# SCH_New-Device-Whole-Board_2024-05-06.net
KiCad netlist of a schematic drawn in EasyEDA
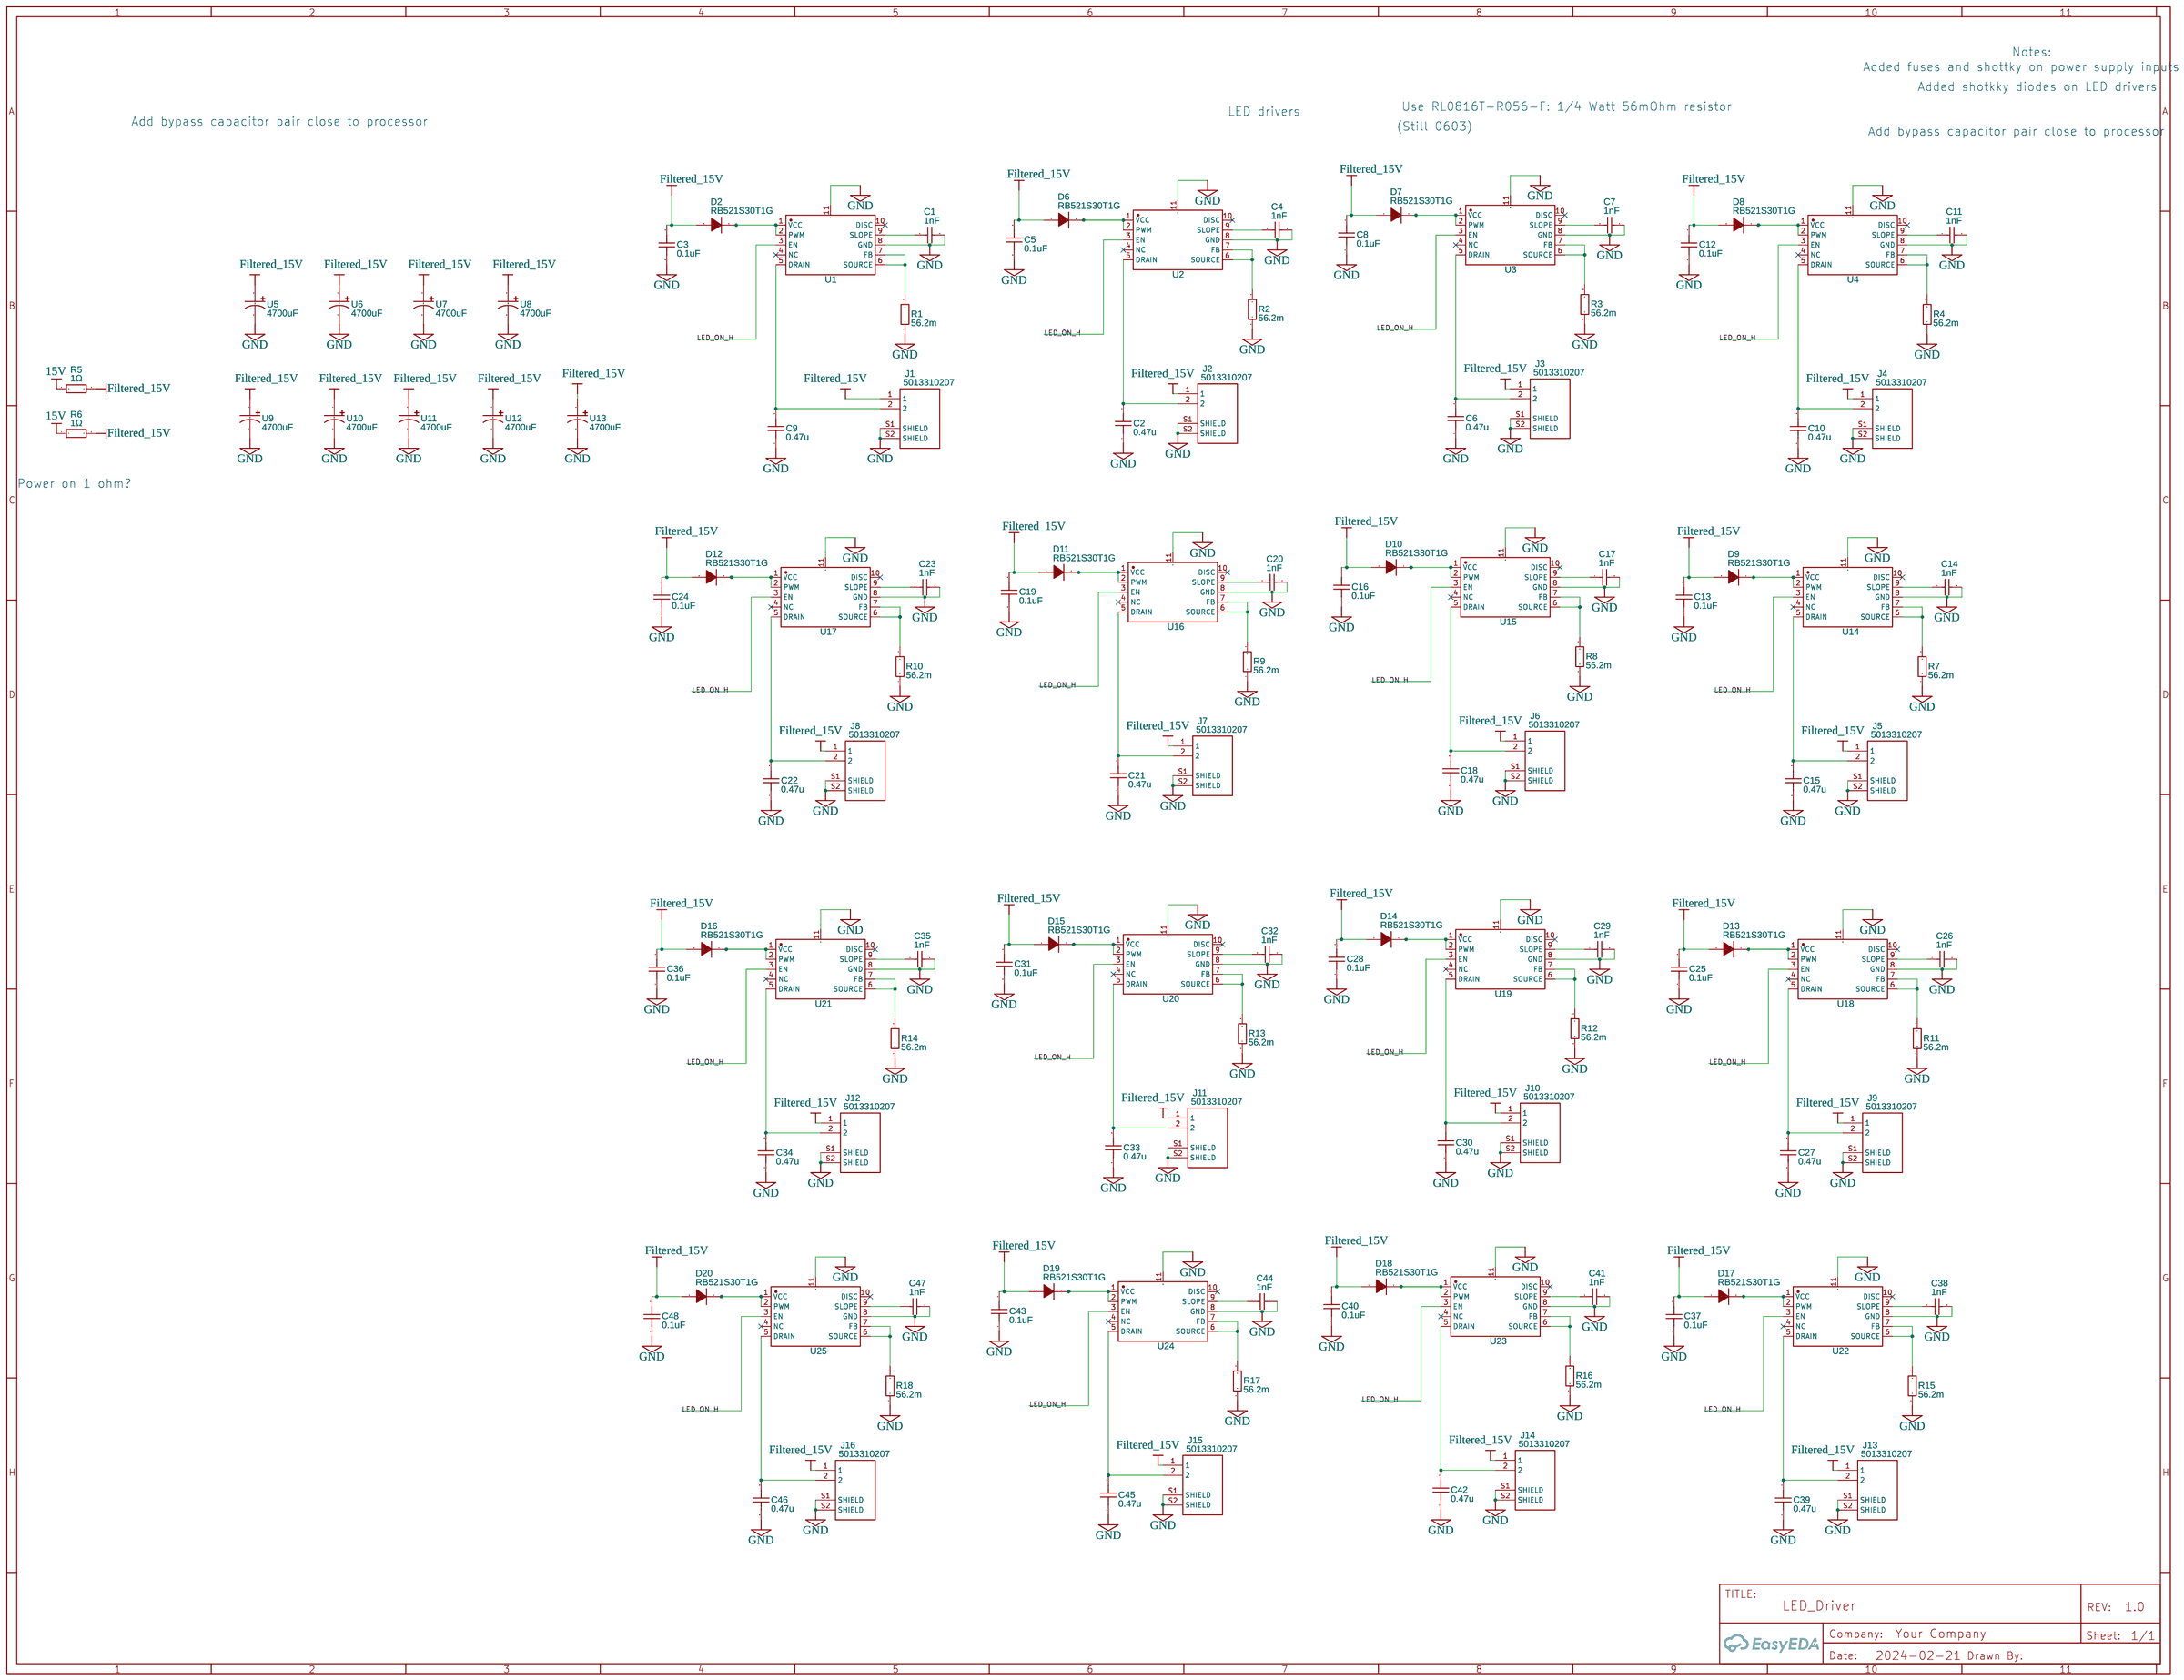
[diagram p0: LED_Driver copy copy]
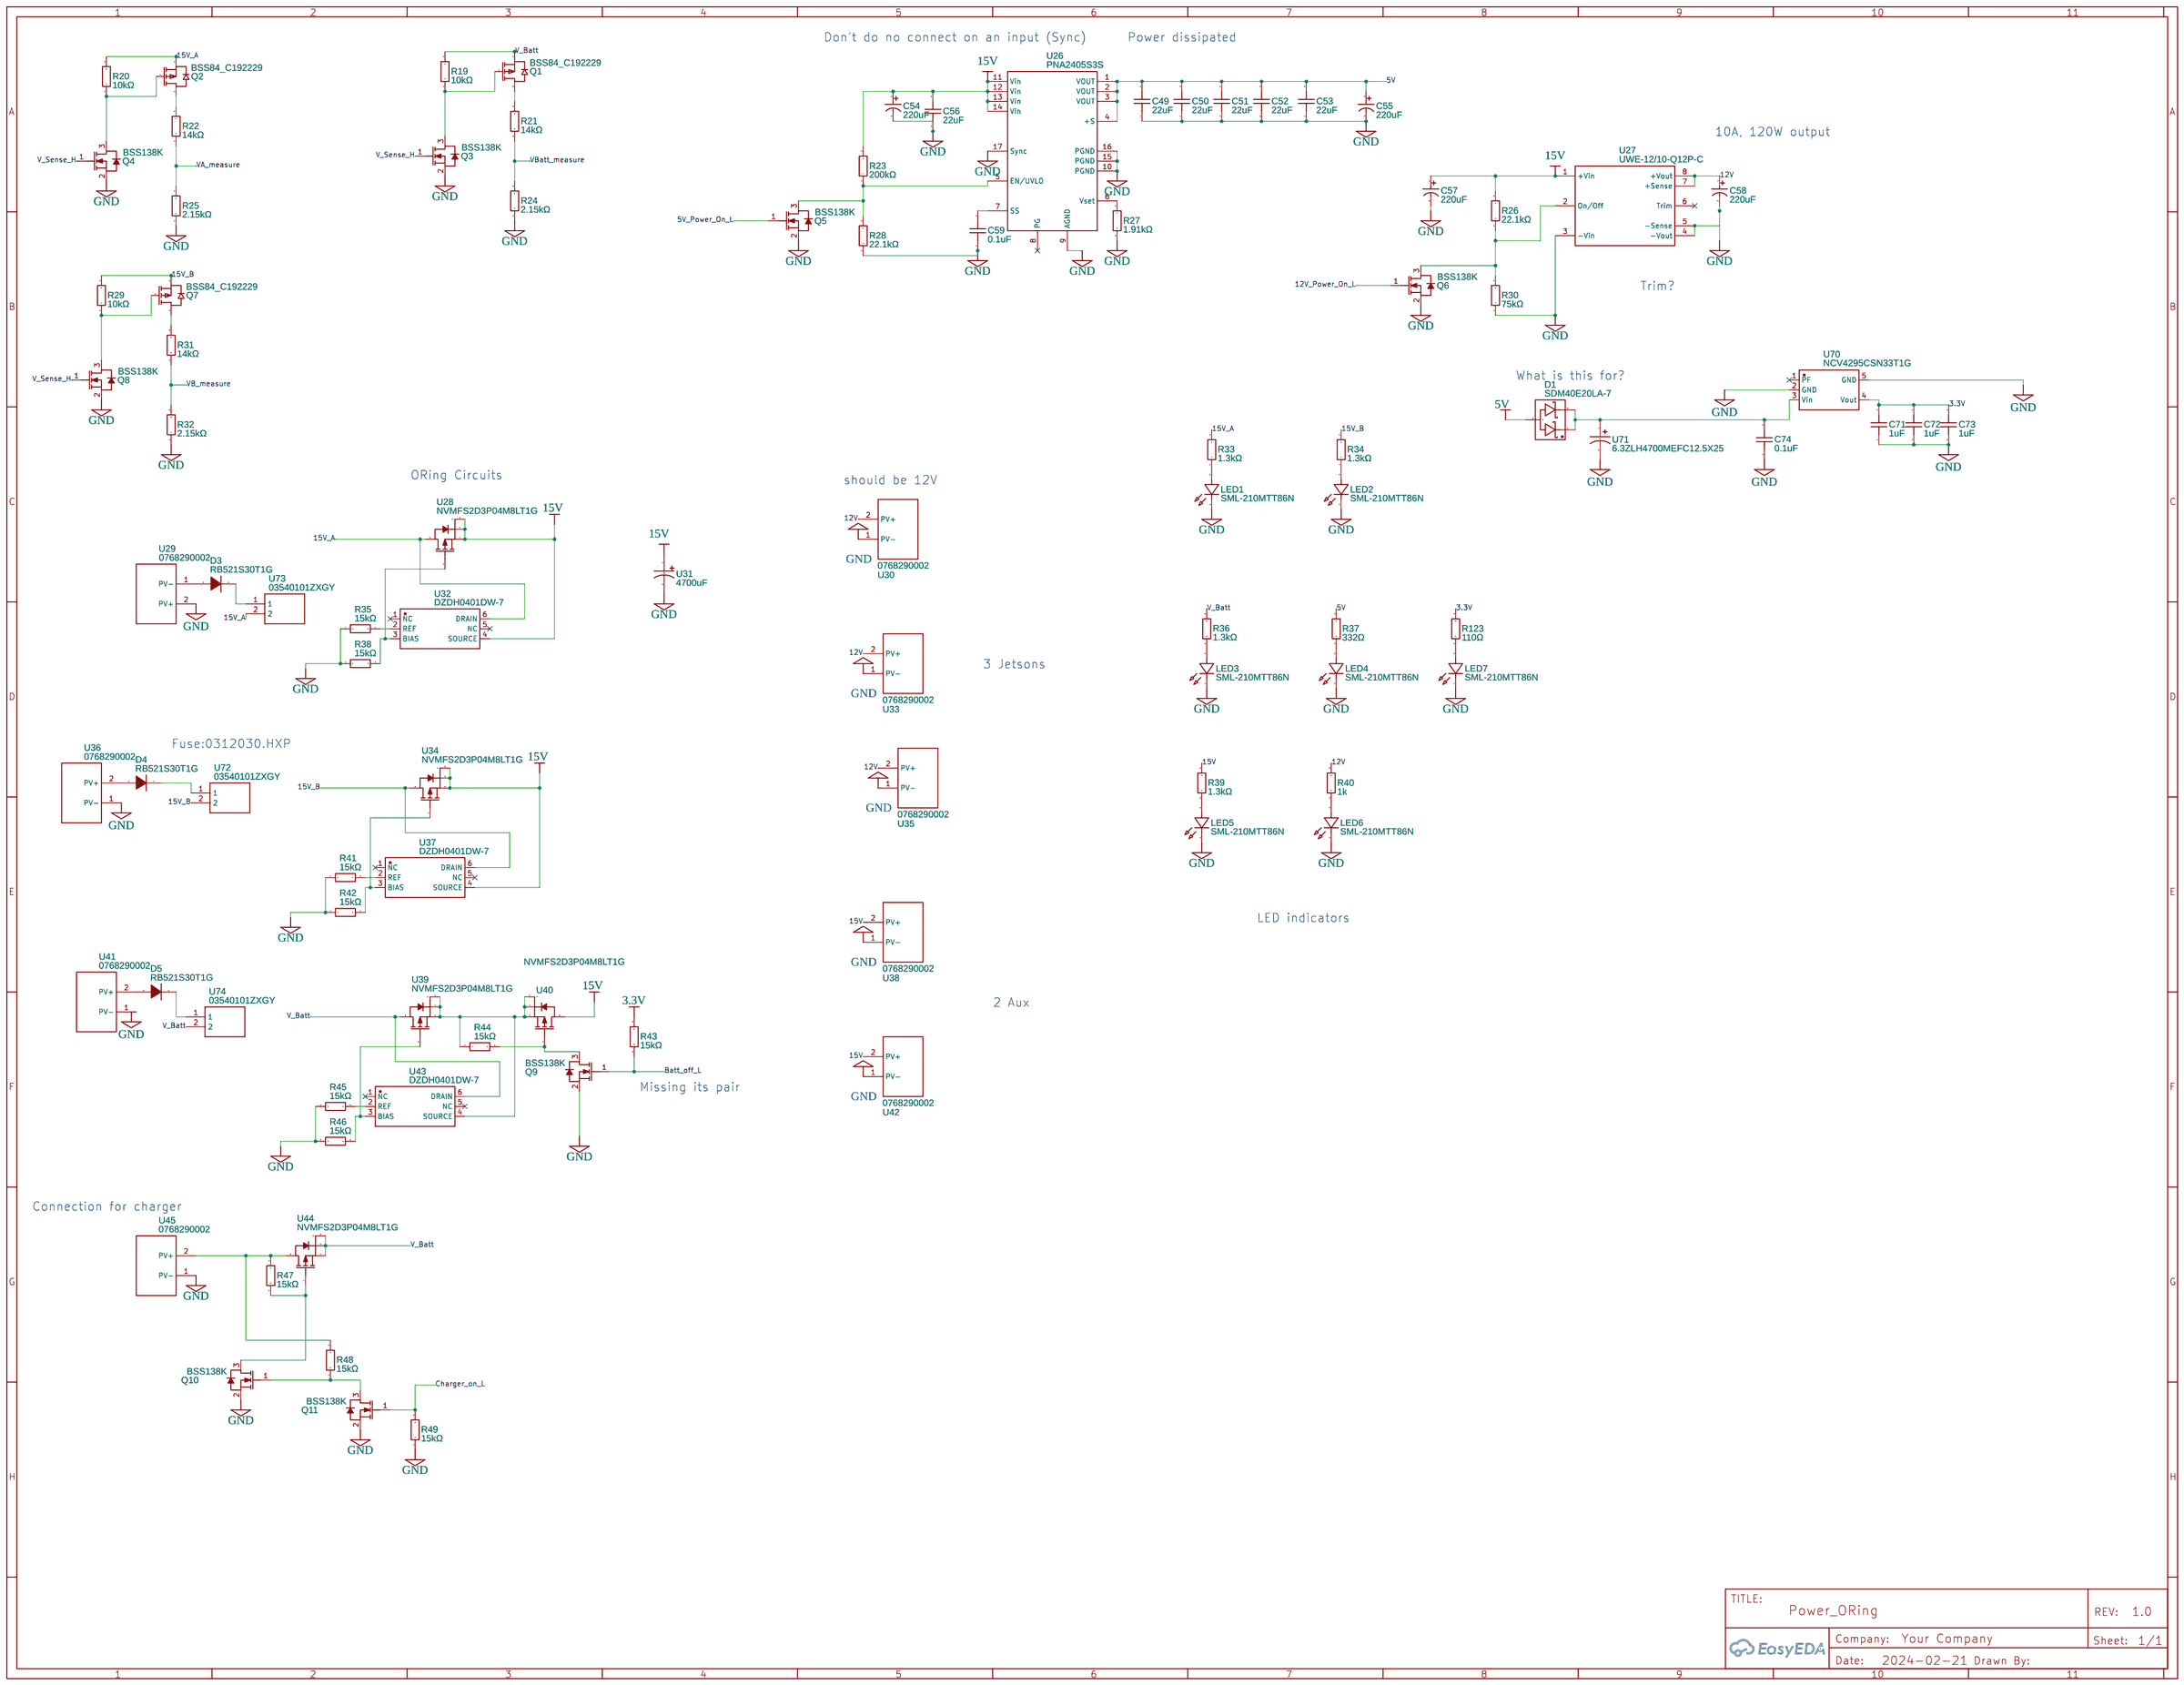
[diagram p1: Power_ORing copy copy]
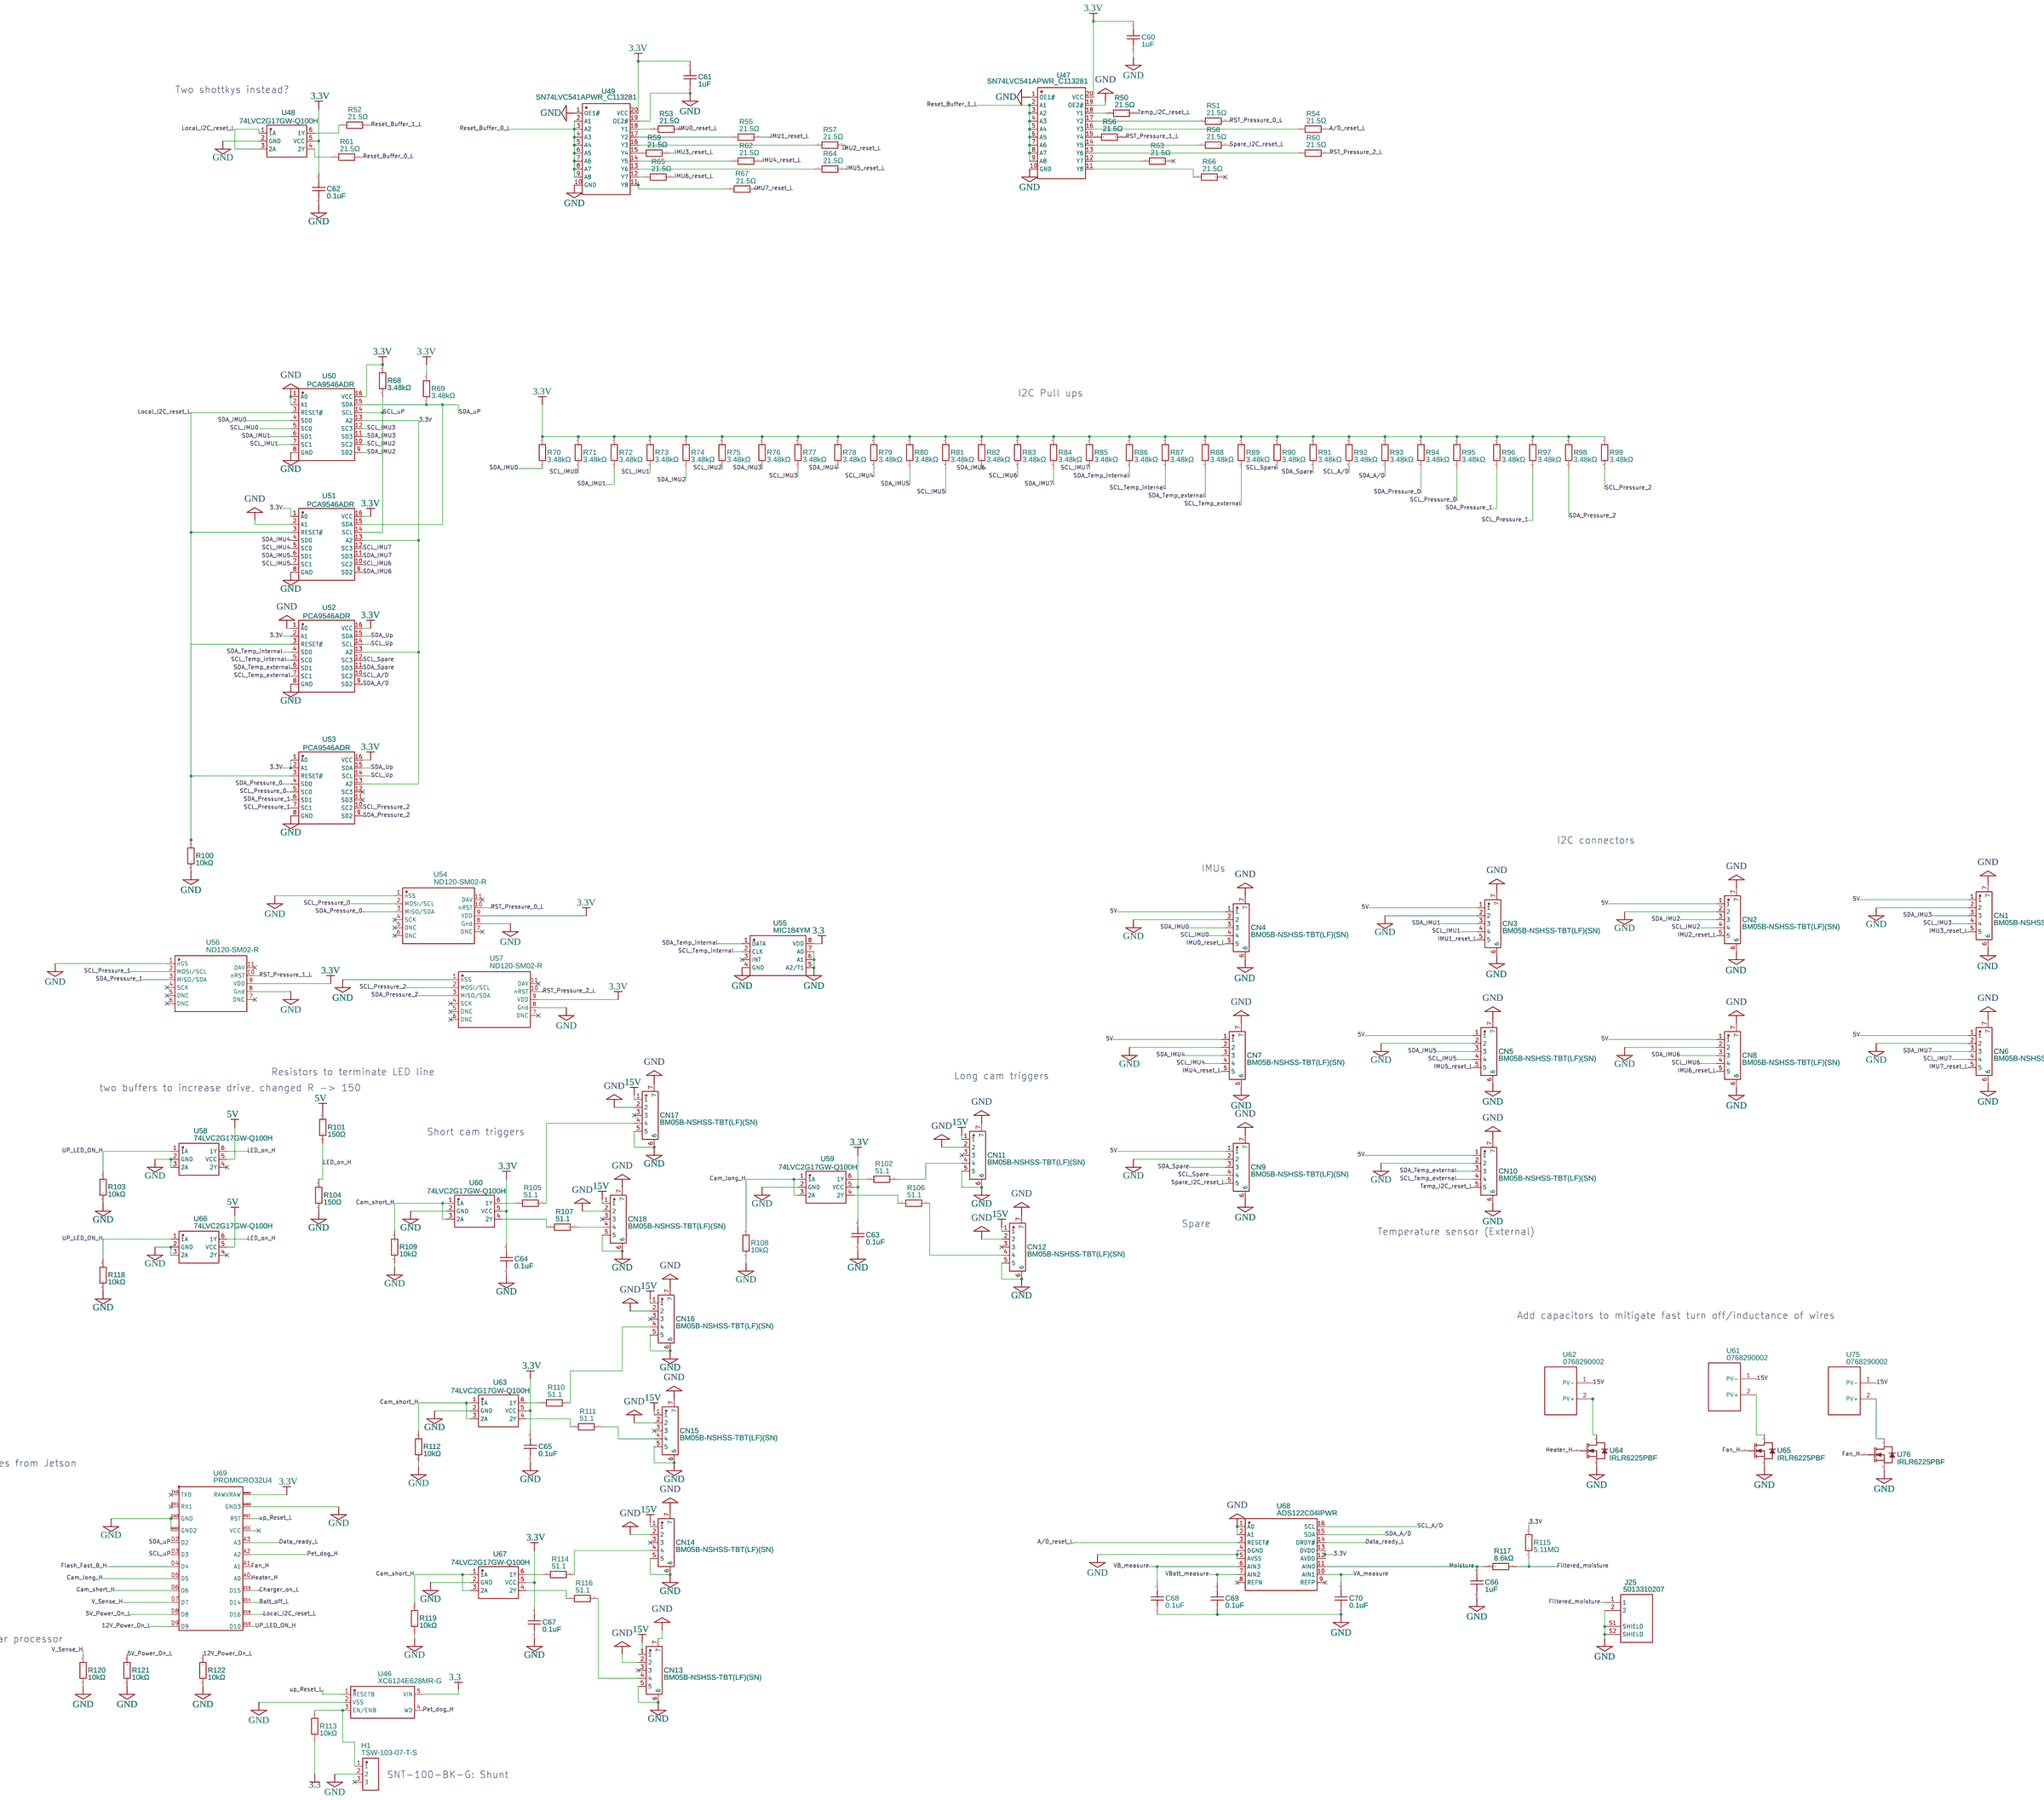
[diagram p2: Control copy copy]

(export (version "E")
  (design (tool "Eeschema 10.0.6"))
  (components
    (comp (ref "C1")
      (value "1nF")
      (fields
        (field (name "Manufacturer Part") "CC0603KRX7R9BB102")
        (field (name "Manufacturer") "YAGEO(国巨)")
      )
      (libsource (lib "") (part "CC0603KRX7R9BB102"))
    )
    (comp (ref "C2")
      (value "0.47u")
      (fields (field (name "Manufacturer Part") "0603CG0R1C500NT") (field (name "Manufacturer") "FH(风华)"))
      (libsource (lib "") (part "0603CG0R1C500NT"))
    )
    (comp (ref "C3")
      (value "0.1uF")
      (fields (field (name "Manufacturer Part") "0603CG0R1C500NT") (field (name "Manufacturer") "FH(风华)"))
      (libsource (lib "") (part "0603CG0R1C500NT"))
    )
    (comp (ref "C4")
      (value "1nF")
      (fields
        (field (name "Manufacturer Part") "CC0603KRX7R9BB102")
        (field (name "Manufacturer") "YAGEO(国巨)")
      )
      (libsource (lib "") (part "CC0603KRX7R9BB102"))
    )
    (comp (ref "C5")
      (value "0.1uF")
      (fields (field (name "Manufacturer Part") "0603CG0R1C500NT") (field (name "Manufacturer") "FH(风华)"))
      (libsource (lib "") (part "0603CG0R1C500NT"))
    )
    (comp (ref "C6")
      (value "0.47u")
      (fields (field (name "Manufacturer Part") "0603CG0R1C500NT") (field (name "Manufacturer") "FH(风华)"))
      (libsource (lib "") (part "0603CG0R1C500NT"))
    )
    (comp (ref "C7")
      (value "1nF")
      (fields
        (field (name "Manufacturer Part") "CC0603KRX7R9BB102")
        (field (name "Manufacturer") "YAGEO(国巨)")
      )
      (libsource (lib "") (part "CC0603KRX7R9BB102"))
    )
    (comp (ref "C8")
      (value "0.1uF")
      (fields (field (name "Manufacturer Part") "0603CG0R1C500NT") (field (name "Manufacturer") "FH(风华)"))
      (libsource (lib "") (part "0603CG0R1C500NT"))
    )
    (comp (ref "C9")
      (value "0.47u")
      (fields (field (name "Manufacturer Part") "0603CG0R1C500NT") (field (name "Manufacturer") "FH(风华)"))
      (libsource (lib "") (part "0603CG0R1C500NT"))
    )
    (comp (ref "C10")
      (value "0.47u")
      (fields (field (name "Manufacturer Part") "0603CG0R1C500NT") (field (name "Manufacturer") "FH(风华)"))
      (libsource (lib "") (part "0603CG0R1C500NT"))
    )
    (comp (ref "C11")
      (value "1nF")
      (fields
        (field (name "Manufacturer Part") "CC0603KRX7R9BB102")
        (field (name "Manufacturer") "YAGEO(国巨)")
      )
      (libsource (lib "") (part "CC0603KRX7R9BB102"))
    )
    (comp (ref "C12")
      (value "0.1uF")
      (fields (field (name "Manufacturer Part") "0603CG0R1C500NT") (field (name "Manufacturer") "FH(风华)"))
      (libsource (lib "") (part "0603CG0R1C500NT"))
    )
    (comp (ref "C13")
      (value "0.1uF")
      (fields (field (name "Manufacturer Part") "0603CG0R1C500NT") (field (name "Manufacturer") "FH(风华)"))
      (libsource (lib "") (part "0603CG0R1C500NT"))
    )
    (comp (ref "C14")
      (value "1nF")
      (fields
        (field (name "Manufacturer Part") "CC0603KRX7R9BB102")
        (field (name "Manufacturer") "YAGEO(国巨)")
      )
      (libsource (lib "") (part "CC0603KRX7R9BB102"))
    )
    (comp (ref "C15")
      (value "0.47u")
      (fields (field (name "Manufacturer Part") "0603CG0R1C500NT") (field (name "Manufacturer") "FH(风华)"))
      (libsource (lib "") (part "0603CG0R1C500NT"))
    )
    (comp (ref "C16")
      (value "0.1uF")
      (fields (field (name "Manufacturer Part") "0603CG0R1C500NT") (field (name "Manufacturer") "FH(风华)"))
      (libsource (lib "") (part "0603CG0R1C500NT"))
    )
    (comp (ref "C17")
      (value "1nF")
      (fields
        (field (name "Manufacturer Part") "CC0603KRX7R9BB102")
        (field (name "Manufacturer") "YAGEO(国巨)")
      )
      (libsource (lib "") (part "CC0603KRX7R9BB102"))
    )
    (comp (ref "C18")
      (value "0.47u")
      (fields (field (name "Manufacturer Part") "0603CG0R1C500NT") (field (name "Manufacturer") "FH(风华)"))
      (libsource (lib "") (part "0603CG0R1C500NT"))
    )
    (comp (ref "C19")
      (value "0.1uF")
      (fields (field (name "Manufacturer Part") "0603CG0R1C500NT") (field (name "Manufacturer") "FH(风华)"))
      (libsource (lib "") (part "0603CG0R1C500NT"))
    )
    (comp (ref "C20")
      (value "1nF")
      (fields
        (field (name "Manufacturer Part") "CC0603KRX7R9BB102")
        (field (name "Manufacturer") "YAGEO(国巨)")
      )
      (libsource (lib "") (part "CC0603KRX7R9BB102"))
    )
    (comp (ref "C21")
      (value "0.47u")
      (fields (field (name "Manufacturer Part") "0603CG0R1C500NT") (field (name "Manufacturer") "FH(风华)"))
      (libsource (lib "") (part "0603CG0R1C500NT"))
    )
    (comp (ref "C22")
      (value "0.47u")
      (fields (field (name "Manufacturer Part") "0603CG0R1C500NT") (field (name "Manufacturer") "FH(风华)"))
      (libsource (lib "") (part "0603CG0R1C500NT"))
    )
    (comp (ref "C23")
      (value "1nF")
      (fields
        (field (name "Manufacturer Part") "CC0603KRX7R9BB102")
        (field (name "Manufacturer") "YAGEO(国巨)")
      )
      (libsource (lib "") (part "CC0603KRX7R9BB102"))
    )
    (comp (ref "C24")
      (value "0.1uF")
      (fields (field (name "Manufacturer Part") "0603CG0R1C500NT") (field (name "Manufacturer") "FH(风华)"))
      (libsource (lib "") (part "0603CG0R1C500NT"))
    )
    (comp (ref "C25")
      (value "0.1uF")
      (fields (field (name "Manufacturer Part") "0603CG0R1C500NT") (field (name "Manufacturer") "FH(风华)"))
      (libsource (lib "") (part "0603CG0R1C500NT"))
    )
    (comp (ref "C26")
      (value "1nF")
      (fields
        (field (name "Manufacturer Part") "CC0603KRX7R9BB102")
        (field (name "Manufacturer") "YAGEO(国巨)")
      )
      (libsource (lib "") (part "CC0603KRX7R9BB102"))
    )
    (comp (ref "C27")
      (value "0.47u")
      (fields (field (name "Manufacturer Part") "0603CG0R1C500NT") (field (name "Manufacturer") "FH(风华)"))
      (libsource (lib "") (part "0603CG0R1C500NT"))
    )
    (comp (ref "C28")
      (value "0.1uF")
      (fields (field (name "Manufacturer Part") "0603CG0R1C500NT") (field (name "Manufacturer") "FH(风华)"))
      (libsource (lib "") (part "0603CG0R1C500NT"))
    )
    (comp (ref "C29")
      (value "1nF")
      (fields
        (field (name "Manufacturer Part") "CC0603KRX7R9BB102")
        (field (name "Manufacturer") "YAGEO(国巨)")
      )
      (libsource (lib "") (part "CC0603KRX7R9BB102"))
    )
    (comp (ref "C30")
      (value "0.47u")
      (fields (field (name "Manufacturer Part") "0603CG0R1C500NT") (field (name "Manufacturer") "FH(风华)"))
      (libsource (lib "") (part "0603CG0R1C500NT"))
    )
    (comp (ref "C31")
      (value "0.1uF")
      (fields (field (name "Manufacturer Part") "0603CG0R1C500NT") (field (name "Manufacturer") "FH(风华)"))
      (libsource (lib "") (part "0603CG0R1C500NT"))
    )
    (comp (ref "C32")
      (value "1nF")
      (fields
        (field (name "Manufacturer Part") "CC0603KRX7R9BB102")
        (field (name "Manufacturer") "YAGEO(国巨)")
      )
      (libsource (lib "") (part "CC0603KRX7R9BB102"))
    )
    (comp (ref "C33")
      (value "0.47u")
      (fields (field (name "Manufacturer Part") "0603CG0R1C500NT") (field (name "Manufacturer") "FH(风华)"))
      (libsource (lib "") (part "0603CG0R1C500NT"))
    )
    (comp (ref "C34")
      (value "0.47u")
      (fields (field (name "Manufacturer Part") "0603CG0R1C500NT") (field (name "Manufacturer") "FH(风华)"))
      (libsource (lib "") (part "0603CG0R1C500NT"))
    )
    (comp (ref "C35")
      (value "1nF")
      (fields
        (field (name "Manufacturer Part") "CC0603KRX7R9BB102")
        (field (name "Manufacturer") "YAGEO(国巨)")
      )
      (libsource (lib "") (part "CC0603KRX7R9BB102"))
    )
    (comp (ref "C36")
      (value "0.1uF")
      (fields (field (name "Manufacturer Part") "0603CG0R1C500NT") (field (name "Manufacturer") "FH(风华)"))
      (libsource (lib "") (part "0603CG0R1C500NT"))
    )
    (comp (ref "C37")
      (value "0.1uF")
      (fields (field (name "Manufacturer Part") "0603CG0R1C500NT") (field (name "Manufacturer") "FH(风华)"))
      (libsource (lib "") (part "0603CG0R1C500NT"))
    )
    (comp (ref "C38")
      (value "1nF")
      (fields
        (field (name "Manufacturer Part") "CC0603KRX7R9BB102")
        (field (name "Manufacturer") "YAGEO(国巨)")
      )
      (libsource (lib "") (part "CC0603KRX7R9BB102"))
    )
    (comp (ref "C39")
      (value "0.47u")
      (fields (field (name "Manufacturer Part") "0603CG0R1C500NT") (field (name "Manufacturer") "FH(风华)"))
      (libsource (lib "") (part "0603CG0R1C500NT"))
    )
    (comp (ref "C40")
      (value "0.1uF")
      (fields (field (name "Manufacturer Part") "0603CG0R1C500NT") (field (name "Manufacturer") "FH(风华)"))
      (libsource (lib "") (part "0603CG0R1C500NT"))
    )
    (comp (ref "C41")
      (value "1nF")
      (fields
        (field (name "Manufacturer Part") "CC0603KRX7R9BB102")
        (field (name "Manufacturer") "YAGEO(国巨)")
      )
      (libsource (lib "") (part "CC0603KRX7R9BB102"))
    )
    (comp (ref "C42")
      (value "0.47u")
      (fields (field (name "Manufacturer Part") "0603CG0R1C500NT") (field (name "Manufacturer") "FH(风华)"))
      (libsource (lib "") (part "0603CG0R1C500NT"))
    )
    (comp (ref "C43")
      (value "0.1uF")
      (fields (field (name "Manufacturer Part") "0603CG0R1C500NT") (field (name "Manufacturer") "FH(风华)"))
      (libsource (lib "") (part "0603CG0R1C500NT"))
    )
    (comp (ref "C44")
      (value "1nF")
      (fields
        (field (name "Manufacturer Part") "CC0603KRX7R9BB102")
        (field (name "Manufacturer") "YAGEO(国巨)")
      )
      (libsource (lib "") (part "CC0603KRX7R9BB102"))
    )
    (comp (ref "C45")
      (value "0.47u")
      (fields (field (name "Manufacturer Part") "0603CG0R1C500NT") (field (name "Manufacturer") "FH(风华)"))
      (libsource (lib "") (part "0603CG0R1C500NT"))
    )
    (comp (ref "C46")
      (value "0.47u")
      (fields (field (name "Manufacturer Part") "0603CG0R1C500NT") (field (name "Manufacturer") "FH(风华)"))
      (libsource (lib "") (part "0603CG0R1C500NT"))
    )
    (comp (ref "C47")
      (value "1nF")
      (fields
        (field (name "Manufacturer Part") "CC0603KRX7R9BB102")
        (field (name "Manufacturer") "YAGEO(国巨)")
      )
      (libsource (lib "") (part "CC0603KRX7R9BB102"))
    )
    (comp (ref "C48")
      (value "0.1uF")
      (fields (field (name "Manufacturer Part") "0603CG0R1C500NT") (field (name "Manufacturer") "FH(风华)"))
      (libsource (lib "") (part "0603CG0R1C500NT"))
    )
    (comp (ref "D2")
      (value "RB521S30T1G")
      (fields (field (name "Manufacturer") "onsemi(安森美)"))
      (libsource (lib "") (part "RB521S30T1G"))
    )
    (comp (ref "D6")
      (value "RB521S30T1G")
      (fields (field (name "Manufacturer") "onsemi(安森美)"))
      (libsource (lib "") (part "RB521S30T1G"))
    )
    (comp (ref "D7")
      (value "RB521S30T1G")
      (fields (field (name "Manufacturer") "onsemi(安森美)"))
      (libsource (lib "") (part "RB521S30T1G"))
    )
    (comp (ref "D8")
      (value "RB521S30T1G")
      (fields (field (name "Manufacturer") "onsemi(安森美)"))
      (libsource (lib "") (part "RB521S30T1G"))
    )
    (comp (ref "D9")
      (value "RB521S30T1G")
      (fields (field (name "Manufacturer") "onsemi(安森美)"))
      (libsource (lib "") (part "RB521S30T1G"))
    )
    (comp (ref "D10")
      (value "RB521S30T1G")
      (fields (field (name "Manufacturer") "onsemi(安森美)"))
      (libsource (lib "") (part "RB521S30T1G"))
    )
    (comp (ref "D11")
      (value "RB521S30T1G")
      (fields (field (name "Manufacturer") "onsemi(安森美)"))
      (libsource (lib "") (part "RB521S30T1G"))
    )
    (comp (ref "D12")
      (value "RB521S30T1G")
      (fields (field (name "Manufacturer") "onsemi(安森美)"))
      (libsource (lib "") (part "RB521S30T1G"))
    )
    (comp (ref "D13")
      (value "RB521S30T1G")
      (fields (field (name "Manufacturer") "onsemi(安森美)"))
      (libsource (lib "") (part "RB521S30T1G"))
    )
    (comp (ref "D14")
      (value "RB521S30T1G")
      (fields (field (name "Manufacturer") "onsemi(安森美)"))
      (libsource (lib "") (part "RB521S30T1G"))
    )
    (comp (ref "D15")
      (value "RB521S30T1G")
      (fields (field (name "Manufacturer") "onsemi(安森美)"))
      (libsource (lib "") (part "RB521S30T1G"))
    )
    (comp (ref "D16")
      (value "RB521S30T1G")
      (fields (field (name "Manufacturer") "onsemi(安森美)"))
      (libsource (lib "") (part "RB521S30T1G"))
    )
    (comp (ref "D17")
      (value "RB521S30T1G")
      (fields (field (name "Manufacturer") "onsemi(安森美)"))
      (libsource (lib "") (part "RB521S30T1G"))
    )
    (comp (ref "D18")
      (value "RB521S30T1G")
      (fields (field (name "Manufacturer") "onsemi(安森美)"))
      (libsource (lib "") (part "RB521S30T1G"))
    )
    (comp (ref "D19")
      (value "RB521S30T1G")
      (fields (field (name "Manufacturer") "onsemi(安森美)"))
      (libsource (lib "") (part "RB521S30T1G"))
    )
    (comp (ref "D20")
      (value "RB521S30T1G")
      (fields (field (name "Manufacturer") "onsemi(安森美)"))
      (libsource (lib "") (part "RB521S30T1G"))
    )
    (comp (ref "J1")
      (value "5013310207")
      (fields (field (name "Manufacturer") "Molex"))
      (libsource (lib "") (part "5013310207"))
    )
    (comp (ref "J2")
      (value "5013310207")
      (fields (field (name "Manufacturer") "Molex"))
      (libsource (lib "") (part "5013310207"))
    )
    (comp (ref "J3")
      (value "5013310207")
      (fields (field (name "Manufacturer") "Molex"))
      (libsource (lib "") (part "5013310207"))
    )
    (comp (ref "J4")
      (value "5013310207")
      (fields (field (name "Manufacturer") "Molex"))
      (libsource (lib "") (part "5013310207"))
    )
    (comp (ref "J5")
      (value "5013310207")
      (fields (field (name "Manufacturer") "Molex"))
      (libsource (lib "") (part "5013310207"))
    )
    (comp (ref "J6")
      (value "5013310207")
      (fields (field (name "Manufacturer") "Molex"))
      (libsource (lib "") (part "5013310207"))
    )
    (comp (ref "J7")
      (value "5013310207")
      (fields (field (name "Manufacturer") "Molex"))
      (libsource (lib "") (part "5013310207"))
    )
    (comp (ref "J8")
      (value "5013310207")
      (fields (field (name "Manufacturer") "Molex"))
      (libsource (lib "") (part "5013310207"))
    )
    (comp (ref "J9")
      (value "5013310207")
      (fields (field (name "Manufacturer") "Molex"))
      (libsource (lib "") (part "5013310207"))
    )
    (comp (ref "J10")
      (value "5013310207")
      (fields (field (name "Manufacturer") "Molex"))
      (libsource (lib "") (part "5013310207"))
    )
    (comp (ref "J11")
      (value "5013310207")
      (fields (field (name "Manufacturer") "Molex"))
      (libsource (lib "") (part "5013310207"))
    )
    (comp (ref "J12")
      (value "5013310207")
      (fields (field (name "Manufacturer") "Molex"))
      (libsource (lib "") (part "5013310207"))
    )
    (comp (ref "J13")
      (value "5013310207")
      (fields (field (name "Manufacturer") "Molex"))
      (libsource (lib "") (part "5013310207"))
    )
    (comp (ref "J14")
      (value "5013310207")
      (fields (field (name "Manufacturer") "Molex"))
      (libsource (lib "") (part "5013310207"))
    )
    (comp (ref "J15")
      (value "5013310207")
      (fields (field (name "Manufacturer") "Molex"))
      (libsource (lib "") (part "5013310207"))
    )
    (comp (ref "J16")
      (value "5013310207")
      (fields (field (name "Manufacturer") "Molex"))
      (libsource (lib "") (part "5013310207"))
    )
    (comp (ref "R1")
      (value "56.2m")
      (fields
        (field (name "Manufacturer Part") "0603WAJ0101T5E")
        (field (name "Manufacturer") "UNI-ROYAL(厚声)")
      )
      (libsource (lib "") (part "0603WAJ0101T5E"))
    )
    (comp (ref "R2")
      (value "56.2m")
      (fields
        (field (name "Manufacturer Part") "0603WAJ0101T5E")
        (field (name "Manufacturer") "UNI-ROYAL(厚声)")
      )
      (libsource (lib "") (part "0603WAJ0101T5E"))
    )
    (comp (ref "R3")
      (value "56.2m")
      (fields
        (field (name "Manufacturer Part") "0603WAJ0101T5E")
        (field (name "Manufacturer") "UNI-ROYAL(厚声)")
      )
      (libsource (lib "") (part "0603WAJ0101T5E"))
    )
    (comp (ref "R4")
      (value "56.2m")
      (fields
        (field (name "Manufacturer Part") "0603WAJ0101T5E")
        (field (name "Manufacturer") "UNI-ROYAL(厚声)")
      )
      (libsource (lib "") (part "0603WAJ0101T5E"))
    )
    (comp (ref "R5")
      (value "1Ω")
      (fields
        (field (name "Manufacturer Part") "25121WF100KT4E")
        (field (name "Manufacturer") "UNI-ROYAL(厚声)")
      )
      (libsource (lib "") (part "25121WF100KT4E"))
    )
    (comp (ref "R6")
      (value "1Ω")
      (fields
        (field (name "Manufacturer Part") "25121WF100KT4E")
        (field (name "Manufacturer") "UNI-ROYAL(厚声)")
      )
      (libsource (lib "") (part "25121WF100KT4E"))
    )
    (comp (ref "R7")
      (value "56.2m")
      (fields
        (field (name "Manufacturer Part") "0603WAJ0101T5E")
        (field (name "Manufacturer") "UNI-ROYAL(厚声)")
      )
      (libsource (lib "") (part "0603WAJ0101T5E"))
    )
    (comp (ref "R8")
      (value "56.2m")
      (fields
        (field (name "Manufacturer Part") "0603WAJ0101T5E")
        (field (name "Manufacturer") "UNI-ROYAL(厚声)")
      )
      (libsource (lib "") (part "0603WAJ0101T5E"))
    )
    (comp (ref "R9")
      (value "56.2m")
      (fields
        (field (name "Manufacturer Part") "0603WAJ0101T5E")
        (field (name "Manufacturer") "UNI-ROYAL(厚声)")
      )
      (libsource (lib "") (part "0603WAJ0101T5E"))
    )
    (comp (ref "R10")
      (value "56.2m")
      (fields
        (field (name "Manufacturer Part") "0603WAJ0101T5E")
        (field (name "Manufacturer") "UNI-ROYAL(厚声)")
      )
      (libsource (lib "") (part "0603WAJ0101T5E"))
    )
    (comp (ref "R11")
      (value "56.2m")
      (fields
        (field (name "Manufacturer Part") "0603WAJ0101T5E")
        (field (name "Manufacturer") "UNI-ROYAL(厚声)")
      )
      (libsource (lib "") (part "0603WAJ0101T5E"))
    )
    (comp (ref "R12")
      (value "56.2m")
      (fields
        (field (name "Manufacturer Part") "0603WAJ0101T5E")
        (field (name "Manufacturer") "UNI-ROYAL(厚声)")
      )
      (libsource (lib "") (part "0603WAJ0101T5E"))
    )
    (comp (ref "R13")
      (value "56.2m")
      (fields
        (field (name "Manufacturer Part") "0603WAJ0101T5E")
        (field (name "Manufacturer") "UNI-ROYAL(厚声)")
      )
      (libsource (lib "") (part "0603WAJ0101T5E"))
    )
    (comp (ref "R14")
      (value "56.2m")
      (fields
        (field (name "Manufacturer Part") "0603WAJ0101T5E")
        (field (name "Manufacturer") "UNI-ROYAL(厚声)")
      )
      (libsource (lib "") (part "0603WAJ0101T5E"))
    )
    (comp (ref "R15")
      (value "56.2m")
      (fields
        (field (name "Manufacturer Part") "0603WAJ0101T5E")
        (field (name "Manufacturer") "UNI-ROYAL(厚声)")
      )
      (libsource (lib "") (part "0603WAJ0101T5E"))
    )
    (comp (ref "R16")
      (value "56.2m")
      (fields
        (field (name "Manufacturer Part") "0603WAJ0101T5E")
        (field (name "Manufacturer") "UNI-ROYAL(厚声)")
      )
      (libsource (lib "") (part "0603WAJ0101T5E"))
    )
    (comp (ref "R17")
      (value "56.2m")
      (fields
        (field (name "Manufacturer Part") "0603WAJ0101T5E")
        (field (name "Manufacturer") "UNI-ROYAL(厚声)")
      )
      (libsource (lib "") (part "0603WAJ0101T5E"))
    )
    (comp (ref "R18")
      (value "56.2m")
      (fields
        (field (name "Manufacturer Part") "0603WAJ0101T5E")
        (field (name "Manufacturer") "UNI-ROYAL(厚声)")
      )
      (libsource (lib "") (part "0603WAJ0101T5E"))
    )
    (comp (ref "U1")
      (value "-")
      (fields (field (name "Manufacturer Part") "STCS2ASPR") (field (name "Manufacturer") "ST(意法半导体)"))
      (libsource (lib "") (part "STCS2ASPR"))
    )
    (comp (ref "U2")
      (value "-")
      (fields (field (name "Manufacturer Part") "STCS2ASPR") (field (name "Manufacturer") "ST(意法半导体)"))
      (libsource (lib "") (part "STCS2ASPR"))
    )
    (comp (ref "U3")
      (value "-")
      (fields (field (name "Manufacturer Part") "STCS2ASPR") (field (name "Manufacturer") "ST(意法半导体)"))
      (libsource (lib "") (part "STCS2ASPR"))
    )
    (comp (ref "U4")
      (value "-")
      (fields (field (name "Manufacturer Part") "STCS2ASPR") (field (name "Manufacturer") "ST(意法半导体)"))
      (libsource (lib "") (part "STCS2ASPR"))
    )
    (comp (ref "U5")
      (value "4700uF")
      (fields (field (name "Manufacturer Part") "B41858C7478M000") (field (name "Manufacturer") "TDK"))
      (libsource (lib "") (part "B41858C7478M000_1"))
    )
    (comp (ref "U6")
      (value "4700uF")
      (fields (field (name "Manufacturer Part") "B41858C7478M000") (field (name "Manufacturer") "TDK"))
      (libsource (lib "") (part "B41858C7478M000"))
    )
    (comp (ref "U7")
      (value "4700uF")
      (fields (field (name "Manufacturer Part") "B41858C7478M000") (field (name "Manufacturer") "TDK"))
      (libsource (lib "") (part "B41858C7478M000"))
    )
    (comp (ref "U8")
      (value "4700uF")
      (fields (field (name "Manufacturer Part") "B41858C7478M000") (field (name "Manufacturer") "TDK"))
      (libsource (lib "") (part "B41858C7478M000"))
    )
    (comp (ref "U9")
      (value "4700uF")
      (fields (field (name "Manufacturer Part") "B41858C7478M000") (field (name "Manufacturer") "TDK"))
      (libsource (lib "") (part "B41858C7478M000_1"))
    )
    (comp (ref "U10")
      (value "4700uF")
      (fields (field (name "Manufacturer Part") "B41858C7478M000") (field (name "Manufacturer") "TDK"))
      (libsource (lib "") (part "B41858C7478M000"))
    )
    (comp (ref "U11")
      (value "4700uF")
      (fields (field (name "Manufacturer Part") "B41858C7478M000") (field (name "Manufacturer") "TDK"))
      (libsource (lib "") (part "B41858C7478M000"))
    )
    (comp (ref "U12")
      (value "4700uF")
      (fields (field (name "Manufacturer Part") "B41858C7478M000") (field (name "Manufacturer") "TDK"))
      (libsource (lib "") (part "B41858C7478M000"))
    )
    (comp (ref "U13")
      (value "4700uF")
      (fields (field (name "Manufacturer Part") "B41858C7478M000") (field (name "Manufacturer") "TDK"))
      (libsource (lib "") (part "B41858C7478M000"))
    )
    (comp (ref "U14")
      (value "-")
      (fields (field (name "Manufacturer Part") "STCS2ASPR") (field (name "Manufacturer") "ST(意法半导体)"))
      (libsource (lib "") (part "STCS2ASPR"))
    )
    (comp (ref "U15")
      (value "-")
      (fields (field (name "Manufacturer Part") "STCS2ASPR") (field (name "Manufacturer") "ST(意法半导体)"))
      (libsource (lib "") (part "STCS2ASPR"))
    )
    (comp (ref "U16")
      (value "-")
      (fields (field (name "Manufacturer Part") "STCS2ASPR") (field (name "Manufacturer") "ST(意法半导体)"))
      (libsource (lib "") (part "STCS2ASPR"))
    )
    (comp (ref "U17")
      (value "-")
      (fields (field (name "Manufacturer Part") "STCS2ASPR") (field (name "Manufacturer") "ST(意法半导体)"))
      (libsource (lib "") (part "STCS2ASPR"))
    )
    (comp (ref "U18")
      (value "-")
      (fields (field (name "Manufacturer Part") "STCS2ASPR") (field (name "Manufacturer") "ST(意法半导体)"))
      (libsource (lib "") (part "STCS2ASPR"))
    )
    (comp (ref "U19")
      (value "-")
      (fields (field (name "Manufacturer Part") "STCS2ASPR") (field (name "Manufacturer") "ST(意法半导体)"))
      (libsource (lib "") (part "STCS2ASPR"))
    )
    (comp (ref "U20")
      (value "-")
      (fields (field (name "Manufacturer Part") "STCS2ASPR") (field (name "Manufacturer") "ST(意法半导体)"))
      (libsource (lib "") (part "STCS2ASPR"))
    )
    (comp (ref "U21")
      (value "-")
      (fields (field (name "Manufacturer Part") "STCS2ASPR") (field (name "Manufacturer") "ST(意法半导体)"))
      (libsource (lib "") (part "STCS2ASPR"))
    )
    (comp (ref "U22")
      (value "-")
      (fields (field (name "Manufacturer Part") "STCS2ASPR") (field (name "Manufacturer") "ST(意法半导体)"))
      (libsource (lib "") (part "STCS2ASPR"))
    )
    (comp (ref "U23")
      (value "-")
      (fields (field (name "Manufacturer Part") "STCS2ASPR") (field (name "Manufacturer") "ST(意法半导体)"))
      (libsource (lib "") (part "STCS2ASPR"))
    )
    (comp (ref "U24")
      (value "-")
      (fields (field (name "Manufacturer Part") "STCS2ASPR") (field (name "Manufacturer") "ST(意法半导体)"))
      (libsource (lib "") (part "STCS2ASPR"))
    )
    (comp (ref "U25")
      (value "-")
      (fields (field (name "Manufacturer Part") "STCS2ASPR") (field (name "Manufacturer") "ST(意法半导体)"))
      (libsource (lib "") (part "STCS2ASPR"))
    )
    (comp (ref "C49")
      (value "22uF")
      (fields
        (field (name "Manufacturer Part") "CL32B226KAJNNNE")
        (field (name "Manufacturer") "SAMSUNG(三星)")
      )
      (libsource (lib "") (part "CL32B226KAJNNNE"))
    )
    (comp (ref "C50")
      (value "22uF")
      (fields
        (field (name "Manufacturer Part") "CL32B226KAJNNNE")
        (field (name "Manufacturer") "SAMSUNG(三星)")
      )
      (libsource (lib "") (part "CL32B226KAJNNNE"))
    )
    (comp (ref "C51")
      (value "22uF")
      (fields
        (field (name "Manufacturer Part") "CL32B226KAJNNNE")
        (field (name "Manufacturer") "SAMSUNG(三星)")
      )
      (libsource (lib "") (part "CL32B226KAJNNNE"))
    )
    (comp (ref "C52")
      (value "22uF")
      (fields
        (field (name "Manufacturer Part") "CL32B226KAJNNNE")
        (field (name "Manufacturer") "SAMSUNG(三星)")
      )
      (libsource (lib "") (part "CL32B226KAJNNNE"))
    )
    (comp (ref "C53")
      (value "22uF")
      (fields
        (field (name "Manufacturer Part") "CL32B226KAJNNNE")
        (field (name "Manufacturer") "SAMSUNG(三星)")
      )
      (libsource (lib "") (part "CL32B226KAJNNNE"))
    )
    (comp (ref "C54")
      (value "220uF")
      (fields
        (field (name "Manufacturer Part") "25YXJ220M6.3X11")
        (field (name "Manufacturer") "rubycon(红宝石)")
      )
      (libsource (lib "") (part "25YXJ220M6.3X11"))
    )
    (comp (ref "C55")
      (value "220uF")
      (fields
        (field (name "Manufacturer Part") "25YXJ220M6.3X11")
        (field (name "Manufacturer") "rubycon(红宝石)")
      )
      (libsource (lib "") (part "25YXJ220M6.3X11"))
    )
    (comp (ref "C56")
      (value "22uF")
      (fields
        (field (name "Manufacturer Part") "CL32B226KAJNNNE")
        (field (name "Manufacturer") "SAMSUNG(三星)")
      )
      (libsource (lib "") (part "CL32B226KAJNNNE"))
    )
    (comp (ref "C57")
      (value "220uF")
      (fields
        (field (name "Manufacturer Part") "25YXJ220M6.3X11")
        (field (name "Manufacturer") "rubycon(红宝石)")
      )
      (libsource (lib "") (part "25YXJ220M6.3X11"))
    )
    (comp (ref "C58")
      (value "220uF")
      (fields
        (field (name "Manufacturer Part") "25YXJ220M6.3X11")
        (field (name "Manufacturer") "rubycon(红宝石)")
      )
      (libsource (lib "") (part "25YXJ220M6.3X11"))
    )
    (comp (ref "C59")
      (value "0.1uF")
      (fields (field (name "Manufacturer Part") "0603CG0R1C500NT") (field (name "Manufacturer") "FH(风华)"))
      (libsource (lib "") (part "0603CG0R1C500NT"))
    )
    (comp (ref "C71")
      (value "1uF")
      (fields (field (name "Manufacturer Part") "0603CG0R1C500NT") (field (name "Manufacturer") "FH(风华)"))
      (libsource (lib "") (part "0603CG0R1C500NT"))
    )
    (comp (ref "C72")
      (value "1uF")
      (fields (field (name "Manufacturer Part") "0603CG0R1C500NT") (field (name "Manufacturer") "FH(风华)"))
      (libsource (lib "") (part "0603CG0R1C500NT"))
    )
    (comp (ref "C73")
      (value "1uF")
      (fields (field (name "Manufacturer Part") "0603CG0R1C500NT") (field (name "Manufacturer") "FH(风华)"))
      (libsource (lib "") (part "0603CG0R1C500NT"))
    )
    (comp (ref "C74")
      (value "0.1uF")
      (fields (field (name "Manufacturer Part") "0603CG0R1C500NT") (field (name "Manufacturer") "FH(风华)"))
      (libsource (lib "") (part "0603CG0R1C500NT"))
    )
    (comp (ref "D1")
      (value "SDM40E20LA-7")
      (fields (field (name "Manufacturer") "DIODES(美台)"))
      (libsource (lib "") (part "SDM40E20LA-7"))
    )
    (comp (ref "D3")
      (value "RB521S30T1G")
      (fields (field (name "Manufacturer") "onsemi(安森美)"))
      (libsource (lib "") (part "RB521S30T1G"))
    )
    (comp (ref "D4")
      (value "RB521S30T1G")
      (fields (field (name "Manufacturer") "onsemi(安森美)"))
      (libsource (lib "") (part "RB521S30T1G"))
    )
    (comp (ref "D5")
      (value "RB521S30T1G")
      (fields (field (name "Manufacturer") "onsemi(安森美)"))
      (libsource (lib "") (part "RB521S30T1G"))
    )
    (comp (ref "LED1")
      (value "SML-210MTT86N")
      (fields (field (name "Manufacturer") "ROHM(罗姆)"))
      (libsource (lib "") (part "SML-210MTT86N"))
    )
    (comp (ref "LED2")
      (value "SML-210MTT86N")
      (fields (field (name "Manufacturer") "ROHM(罗姆)"))
      (libsource (lib "") (part "SML-210MTT86N"))
    )
    (comp (ref "LED3")
      (value "SML-210MTT86N")
      (fields (field (name "Manufacturer") "ROHM(罗姆)"))
      (libsource (lib "") (part "SML-210MTT86N"))
    )
    (comp (ref "LED4")
      (value "SML-210MTT86N")
      (fields (field (name "Manufacturer") "ROHM(罗姆)"))
      (libsource (lib "") (part "SML-210MTT86N"))
    )
    (comp (ref "LED5")
      (value "SML-210MTT86N")
      (fields (field (name "Manufacturer") "ROHM(罗姆)"))
      (libsource (lib "") (part "SML-210MTT86N"))
    )
    (comp (ref "LED6")
      (value "SML-210MTT86N")
      (fields (field (name "Manufacturer") "ROHM(罗姆)"))
      (libsource (lib "") (part "SML-210MTT86N"))
    )
    (comp (ref "LED7")
      (value "SML-210MTT86N")
      (fields (field (name "Manufacturer") "ROHM(罗姆)"))
      (libsource (lib "") (part "SML-210MTT86N"))
    )
    (comp (ref "Q1")
      (value "BSS84_C192229")
      (fields (field (name "Manufacturer Part") "BSS84") (field (name "Manufacturer") "FMS(美丽微)"))
      (libsource (lib "") (part "BSS84_C192229"))
    )
    (comp (ref "Q2")
      (value "BSS84_C192229")
      (fields (field (name "Manufacturer Part") "BSS84") (field (name "Manufacturer") "FMS(美丽微)"))
      (libsource (lib "") (part "BSS84_C192229"))
    )
    (comp (ref "Q3")
      (value "BSS138K")
      (fields (field (name "Manufacturer") "onsemi(安森美)"))
      (libsource (lib "") (part "BSS138K"))
    )
    (comp (ref "Q4")
      (value "BSS138K")
      (fields (field (name "Manufacturer") "onsemi(安森美)"))
      (libsource (lib "") (part "BSS138K"))
    )
    (comp (ref "Q5")
      (value "BSS138K")
      (fields (field (name "Manufacturer") "onsemi(安森美)"))
      (libsource (lib "") (part "BSS138K"))
    )
    (comp (ref "Q6")
      (value "BSS138K")
      (fields (field (name "Manufacturer") "onsemi(安森美)"))
      (libsource (lib "") (part "BSS138K"))
    )
    (comp (ref "Q7")
      (value "BSS84_C192229")
      (fields (field (name "Manufacturer Part") "BSS84") (field (name "Manufacturer") "FMS(美丽微)"))
      (libsource (lib "") (part "BSS84_C192229"))
    )
    (comp (ref "Q8")
      (value "BSS138K")
      (fields (field (name "Manufacturer") "onsemi(安森美)"))
      (libsource (lib "") (part "BSS138K"))
    )
    (comp (ref "Q9")
      (value "BSS138K")
      (fields (field (name "Manufacturer") "onsemi(安森美)"))
      (libsource (lib "") (part "BSS138K_1"))
    )
    (comp (ref "Q10")
      (value "BSS138K")
      (fields (field (name "Manufacturer") "onsemi(安森美)"))
      (libsource (lib "") (part "BSS138K_1"))
    )
    (comp (ref "Q11")
      (value "BSS138K")
      (fields (field (name "Manufacturer") "onsemi(安森美)"))
      (libsource (lib "") (part "BSS138K_1"))
    )
    (comp (ref "R19")
      (value "10kΩ")
      (fields (field (name "Manufacturer Part") "RC0402JR-070RL") (field (name "Manufacturer") "YAGEO(国巨)"))
      (libsource (lib "") (part "RC0402JR-070RL"))
    )
    (comp (ref "R20")
      (value "10kΩ")
      (fields (field (name "Manufacturer Part") "RC0402JR-070RL") (field (name "Manufacturer") "YAGEO(国巨)"))
      (libsource (lib "") (part "RC0402JR-070RL"))
    )
    (comp (ref "R21")
      (value "14kΩ")
      (fields (field (name "Manufacturer Part") "RC0402JR-070RL") (field (name "Manufacturer") "YAGEO(国巨)"))
      (libsource (lib "") (part "RC0402JR-070RL"))
    )
    (comp (ref "R22")
      (value "14kΩ")
      (fields (field (name "Manufacturer Part") "RC0402JR-070RL") (field (name "Manufacturer") "YAGEO(国巨)"))
      (libsource (lib "") (part "RC0402JR-070RL"))
    )
    (comp (ref "R23")
      (value "200kΩ")
      (fields (field (name "Manufacturer Part") "RC0402JR-070RL") (field (name "Manufacturer") "YAGEO(国巨)"))
      (libsource (lib "") (part "RC0402JR-070RL"))
    )
    (comp (ref "R24")
      (value "2.15kΩ")
      (fields (field (name "Manufacturer Part") "RC0402JR-070RL") (field (name "Manufacturer") "YAGEO(国巨)"))
      (libsource (lib "") (part "RC0402JR-070RL"))
    )
    (comp (ref "R25")
      (value "2.15kΩ")
      (fields (field (name "Manufacturer Part") "RC0402JR-070RL") (field (name "Manufacturer") "YAGEO(国巨)"))
      (libsource (lib "") (part "RC0402JR-070RL"))
    )
    (comp (ref "R26")
      (value "22.1kΩ")
      (fields (field (name "Manufacturer Part") "RC0402JR-070RL") (field (name "Manufacturer") "YAGEO(国巨)"))
      (libsource (lib "") (part "RC0402JR-070RL"))
    )
    (comp (ref "R27")
      (value "1.91kΩ")
      (fields (field (name "Manufacturer Part") "RC0402JR-070RL") (field (name "Manufacturer") "YAGEO(国巨)"))
      (libsource (lib "") (part "RC0402JR-070RL"))
    )
    (comp (ref "R28")
      (value "22.1kΩ")
      (fields (field (name "Manufacturer Part") "RC0402JR-070RL") (field (name "Manufacturer") "YAGEO(国巨)"))
      (libsource (lib "") (part "RC0402JR-070RL"))
    )
    (comp (ref "R29")
      (value "10kΩ")
      (fields (field (name "Manufacturer Part") "RC0402JR-070RL") (field (name "Manufacturer") "YAGEO(国巨)"))
      (libsource (lib "") (part "RC0402JR-070RL"))
    )
    (comp (ref "R30")
      (value "75kΩ")
      (fields (field (name "Manufacturer Part") "RC0402JR-070RL") (field (name "Manufacturer") "YAGEO(国巨)"))
      (libsource (lib "") (part "RC0402JR-070RL"))
    )
    (comp (ref "R31")
      (value "14kΩ")
      (fields (field (name "Manufacturer Part") "RC0402JR-070RL") (field (name "Manufacturer") "YAGEO(国巨)"))
      (libsource (lib "") (part "RC0402JR-070RL"))
    )
    (comp (ref "R32")
      (value "2.15kΩ")
      (fields (field (name "Manufacturer Part") "RC0402JR-070RL") (field (name "Manufacturer") "YAGEO(国巨)"))
      (libsource (lib "") (part "RC0402JR-070RL"))
    )
    (comp (ref "R33")
      (value "1.3kΩ")
      (fields (field (name "Manufacturer Part") "RK73H2ATTD1301F") (field (name "Manufacturer") "KOA"))
      (libsource (lib "") (part "RK73H2ATTD1301F"))
    )
    (comp (ref "R34")
      (value "1.3kΩ")
      (fields (field (name "Manufacturer Part") "RK73H2ATTD1301F") (field (name "Manufacturer") "KOA"))
      (libsource (lib "") (part "RK73H2ATTD1301F"))
    )
    (comp (ref "R35")
      (value "15kΩ")
      (fields
        (field (name "Manufacturer Part") "0603WAF1502T5E")
        (field (name "Manufacturer") "UNI-ROYAL(厚声)")
      )
      (libsource (lib "") (part "0603WAF1502T5E"))
    )
    (comp (ref "R36")
      (value "1.3kΩ")
      (fields (field (name "Manufacturer Part") "RK73H2ATTD1301F") (field (name "Manufacturer") "KOA"))
      (libsource (lib "") (part "RK73H2ATTD1301F"))
    )
    (comp (ref "R37")
      (value "332Ω")
      (fields (field (name "Manufacturer Part") "ARG03FTC3320") (field (name "Manufacturer") "Viking(光颉)"))
      (libsource (lib "") (part "ARG03FTC3320"))
    )
    (comp (ref "R38")
      (value "15kΩ")
      (fields
        (field (name "Manufacturer Part") "0603WAF1502T5E")
        (field (name "Manufacturer") "UNI-ROYAL(厚声)")
      )
      (libsource (lib "") (part "0603WAF1502T5E"))
    )
    (comp (ref "R39")
      (value "1.3kΩ")
      (fields (field (name "Manufacturer Part") "RK73H2ATTD1301F") (field (name "Manufacturer") "KOA"))
      (libsource (lib "") (part "RK73H2ATTD1301F"))
    )
    (comp (ref "R40")
      (value "1k")
      (fields (field (name "Manufacturer Part") "ARG03FTC3320") (field (name "Manufacturer") "Viking(光颉)"))
      (libsource (lib "") (part "ARG03FTC3320"))
    )
    (comp (ref "R41")
      (value "15kΩ")
      (fields
        (field (name "Manufacturer Part") "0603WAF1502T5E")
        (field (name "Manufacturer") "UNI-ROYAL(厚声)")
      )
      (libsource (lib "") (part "0603WAF1502T5E"))
    )
    (comp (ref "R42")
      (value "15kΩ")
      (fields
        (field (name "Manufacturer Part") "0603WAF1502T5E")
        (field (name "Manufacturer") "UNI-ROYAL(厚声)")
      )
      (libsource (lib "") (part "0603WAF1502T5E"))
    )
    (comp (ref "R43")
      (value "15kΩ")
      (fields
        (field (name "Manufacturer Part") "0603WAF1502T5E")
        (field (name "Manufacturer") "UNI-ROYAL(厚声)")
      )
      (libsource (lib "") (part "0603WAF1502T5E_1"))
    )
    (comp (ref "R44")
      (value "15kΩ")
      (fields
        (field (name "Manufacturer Part") "0603WAF1502T5E")
        (field (name "Manufacturer") "UNI-ROYAL(厚声)")
      )
      (libsource (lib "") (part "0603WAF1502T5E"))
    )
    (comp (ref "R45")
      (value "15kΩ")
      (fields
        (field (name "Manufacturer Part") "0603WAF1502T5E")
        (field (name "Manufacturer") "UNI-ROYAL(厚声)")
      )
      (libsource (lib "") (part "0603WAF1502T5E"))
    )
    (comp (ref "R46")
      (value "15kΩ")
      (fields
        (field (name "Manufacturer Part") "0603WAF1502T5E")
        (field (name "Manufacturer") "UNI-ROYAL(厚声)")
      )
      (libsource (lib "") (part "0603WAF1502T5E"))
    )
    (comp (ref "R47")
      (value "15kΩ")
      (fields
        (field (name "Manufacturer Part") "0603WAF1502T5E")
        (field (name "Manufacturer") "UNI-ROYAL(厚声)")
      )
      (libsource (lib "") (part "0603WAF1502T5E_2"))
    )
    (comp (ref "R48")
      (value "15kΩ")
      (fields
        (field (name "Manufacturer Part") "0603WAF1502T5E")
        (field (name "Manufacturer") "UNI-ROYAL(厚声)")
      )
      (libsource (lib "") (part "0603WAF1502T5E_1"))
    )
    (comp (ref "R49")
      (value "15kΩ")
      (fields
        (field (name "Manufacturer Part") "0603WAF1502T5E")
        (field (name "Manufacturer") "UNI-ROYAL(厚声)")
      )
      (libsource (lib "") (part "0603WAF1502T5E_1"))
    )
    (comp (ref "R123")
      (value "110Ω")
      (fields (field (name "Manufacturer Part") "ARG03FTC3320") (field (name "Manufacturer") "Viking(光颉)"))
      (libsource (lib "") (part "ARG03FTC3320"))
    )
    (comp (ref "U26")
      (value "PNA2405S3S")
      (fields (field (name "Manufacturer") "FLEX"))
      (libsource (lib "") (part "PNA2405S3S"))
    )
    (comp (ref "U27")
      (value "UWE-12/10-Q12P-C")
      (fields
        (field (name "Manufacturer Part") "UEI30-050-Q12P-C")
        (field (name "Manufacturer") "Murata Power Solutions")
      )
      (libsource (lib "") (part "UWE-12/10-Q12P-C"))
    )
    (comp (ref "U28")
      (value "NVMFS2D3P04M8LT1G")
      (fields (field (name "Manufacturer") "onsemi(安森美)"))
      (libsource (lib "") (part "NVMFS2D3P04M8LT1G"))
    )
    (comp (ref "U29") (value "0768290002") (libsource (lib "") (part "0768290002_2")))
    (comp (ref "U30") (value "0768290002") (libsource (lib "") (part "0768290002")))
    (comp (ref "U31")
      (value "4700uF")
      (fields (field (name "Manufacturer Part") "B41858C7478M000") (field (name "Manufacturer") "TDK"))
      (libsource (lib "") (part "B41858C7478M000"))
    )
    (comp (ref "U32")
      (value "DZDH0401DW-7")
      (fields (field (name "Manufacturer") "DIODES(美台)"))
      (libsource (lib "") (part "DZDH0401DW-7"))
    )
    (comp (ref "U33") (value "0768290002") (libsource (lib "") (part "0768290002")))
    (comp (ref "U34")
      (value "NVMFS2D3P04M8LT1G")
      (fields (field (name "Manufacturer") "onsemi(安森美)"))
      (libsource (lib "") (part "NVMFS2D3P04M8LT1G"))
    )
    (comp (ref "U35") (value "0768290002") (libsource (lib "") (part "0768290002")))
    (comp (ref "U36") (value "0768290002") (libsource (lib "") (part "0768290002_1")))
    (comp (ref "U37")
      (value "DZDH0401DW-7")
      (fields (field (name "Manufacturer") "DIODES(美台)"))
      (libsource (lib "") (part "DZDH0401DW-7"))
    )
    (comp (ref "U38") (value "0768290002") (libsource (lib "") (part "0768290002")))
    (comp (ref "U39")
      (value "NVMFS2D3P04M8LT1G")
      (fields (field (name "Manufacturer") "onsemi(安森美)"))
      (libsource (lib "") (part "NVMFS2D3P04M8LT1G"))
    )
    (comp (ref "U40")
      (value "NVMFS2D3P04M8LT1G")
      (fields (field (name "Manufacturer") "onsemi(安森美)"))
      (libsource (lib "") (part "NVMFS2D3P04M8LT1G_1"))
    )
    (comp (ref "U41") (value "0768290002") (libsource (lib "") (part "0768290002_1")))
    (comp (ref "U42") (value "0768290002") (libsource (lib "") (part "0768290002")))
    (comp (ref "U43")
      (value "DZDH0401DW-7")
      (fields (field (name "Manufacturer") "DIODES(美台)"))
      (libsource (lib "") (part "DZDH0401DW-7"))
    )
    (comp (ref "U44")
      (value "NVMFS2D3P04M8LT1G")
      (fields (field (name "Manufacturer") "onsemi(安森美)"))
      (libsource (lib "") (part "NVMFS2D3P04M8LT1G"))
    )
    (comp (ref "U45") (value "0768290002") (libsource (lib "") (part "0768290002_1")))
    (comp (ref "U70")
      (value "NCV4295CSN33T1G")
      (fields (field (name "Manufacturer") "onsemi(安森美)"))
      (libsource (lib "") (part "NCV4295CSN33T1G"))
    )
    (comp (ref "U71")
      (value "6.3ZLH4700MEFC12.5X25")
      (fields (field (name "Manufacturer") "rubycon(红宝石)"))
      (libsource (lib "") (part "6.3ZLH4700MEFC12.5X25"))
    )
    (comp (ref "U72") (value "03540101ZXGY") (libsource (lib "") (part "03540101ZXGY")))
    (comp (ref "U73") (value "03540101ZXGY") (libsource (lib "") (part "03540101ZXGY")))
    (comp (ref "U74") (value "03540101ZXGY") (libsource (lib "") (part "03540101ZXGY")))
    (comp (ref "C60")
      (value "1uF")
      (fields (field (name "Manufacturer Part") "0603CG0R1C500NT") (field (name "Manufacturer") "FH(风华)"))
      (libsource (lib "") (part "0603CG0R1C500NT_1"))
    )
    (comp (ref "C61")
      (value "1uF")
      (fields (field (name "Manufacturer Part") "0603CG0R1C500NT") (field (name "Manufacturer") "FH(风华)"))
      (libsource (lib "") (part "0603CG0R1C500NT"))
    )
    (comp (ref "C62")
      (value "0.1uF")
      (fields (field (name "Manufacturer Part") "0603CG0R1C500NT") (field (name "Manufacturer") "FH(风华)"))
      (libsource (lib "") (part "0603CG0R1C500NT"))
    )
    (comp (ref "C63")
      (value "0.1uF")
      (fields (field (name "Manufacturer Part") "0603CG0R1C500NT") (field (name "Manufacturer") "FH(风华)"))
      (libsource (lib "") (part "0603CG0R1C500NT"))
    )
    (comp (ref "C64")
      (value "0.1uF")
      (fields (field (name "Manufacturer Part") "0603CG0R1C500NT") (field (name "Manufacturer") "FH(风华)"))
      (libsource (lib "") (part "0603CG0R1C500NT"))
    )
    (comp (ref "C65")
      (value "0.1uF")
      (fields (field (name "Manufacturer Part") "0603CG0R1C500NT") (field (name "Manufacturer") "FH(风华)"))
      (libsource (lib "") (part "0603CG0R1C500NT"))
    )
    (comp (ref "C66")
      (value "1uF")
      (fields (field (name "Manufacturer Part") "0603CG0R1C500NT") (field (name "Manufacturer") "FH(风华)"))
      (libsource (lib "") (part "0603CG0R1C500NT"))
    )
    (comp (ref "C67")
      (value "0.1uF")
      (fields (field (name "Manufacturer Part") "0603CG0R1C500NT") (field (name "Manufacturer") "FH(风华)"))
      (libsource (lib "") (part "0603CG0R1C500NT"))
    )
    (comp (ref "C68")
      (value "0.1uF")
      (fields (field (name "Manufacturer Part") "0603CG0R1C500NT") (field (name "Manufacturer") "FH(风华)"))
      (libsource (lib "") (part "0603CG0R1C500NT"))
    )
    (comp (ref "C69")
      (value "0.1uF")
      (fields (field (name "Manufacturer Part") "0603CG0R1C500NT") (field (name "Manufacturer") "FH(风华)"))
      (libsource (lib "") (part "0603CG0R1C500NT"))
    )
    (comp (ref "C70")
      (value "0.1uF")
      (fields (field (name "Manufacturer Part") "0603CG0R1C500NT") (field (name "Manufacturer") "FH(风华)"))
      (libsource (lib "") (part "0603CG0R1C500NT"))
    )
    (comp (ref "CN1")
      (value "BM05B-NSHSS-TBT(LF)(SN)")
      (fields (field (name "Manufacturer") "JST"))
      (libsource (lib "") (part "BM05B-NSHSS-TBT(LF)(SN)"))
    )
    (comp (ref "CN2")
      (value "BM05B-NSHSS-TBT(LF)(SN)")
      (fields (field (name "Manufacturer") "JST"))
      (libsource (lib "") (part "BM05B-NSHSS-TBT(LF)(SN)"))
    )
    (comp (ref "CN3")
      (value "BM05B-NSHSS-TBT(LF)(SN)")
      (fields (field (name "Manufacturer") "JST"))
      (libsource (lib "") (part "BM05B-NSHSS-TBT(LF)(SN)"))
    )
    (comp (ref "CN4")
      (value "BM05B-NSHSS-TBT(LF)(SN)")
      (fields (field (name "Manufacturer") "JST"))
      (libsource (lib "") (part "BM05B-NSHSS-TBT(LF)(SN)"))
    )
    (comp (ref "CN5")
      (value "BM05B-NSHSS-TBT(LF)(SN)")
      (fields (field (name "Manufacturer") "JST"))
      (libsource (lib "") (part "BM05B-NSHSS-TBT(LF)(SN)"))
    )
    (comp (ref "CN6")
      (value "BM05B-NSHSS-TBT(LF)(SN)")
      (fields (field (name "Manufacturer") "JST"))
      (libsource (lib "") (part "BM05B-NSHSS-TBT(LF)(SN)"))
    )
    (comp (ref "CN7")
      (value "BM05B-NSHSS-TBT(LF)(SN)")
      (fields (field (name "Manufacturer") "JST"))
      (libsource (lib "") (part "BM05B-NSHSS-TBT(LF)(SN)"))
    )
    (comp (ref "CN8")
      (value "BM05B-NSHSS-TBT(LF)(SN)")
      (fields (field (name "Manufacturer") "JST"))
      (libsource (lib "") (part "BM05B-NSHSS-TBT(LF)(SN)"))
    )
    (comp (ref "CN9")
      (value "BM05B-NSHSS-TBT(LF)(SN)")
      (fields (field (name "Manufacturer") "JST"))
      (libsource (lib "") (part "BM05B-NSHSS-TBT(LF)(SN)"))
    )
    (comp (ref "CN10")
      (value "BM05B-NSHSS-TBT(LF)(SN)")
      (fields (field (name "Manufacturer") "JST"))
      (libsource (lib "") (part "BM05B-NSHSS-TBT(LF)(SN)"))
    )
    (comp (ref "CN11")
      (value "BM05B-NSHSS-TBT(LF)(SN)")
      (fields (field (name "Manufacturer") "JST"))
      (libsource (lib "") (part "BM05B-NSHSS-TBT(LF)(SN)"))
    )
    (comp (ref "CN12")
      (value "BM05B-NSHSS-TBT(LF)(SN)")
      (fields (field (name "Manufacturer") "JST"))
      (libsource (lib "") (part "BM05B-NSHSS-TBT(LF)(SN)"))
    )
    (comp (ref "CN13")
      (value "BM05B-NSHSS-TBT(LF)(SN)")
      (fields (field (name "Manufacturer") "JST"))
      (libsource (lib "") (part "BM05B-NSHSS-TBT(LF)(SN)"))
    )
    (comp (ref "CN14")
      (value "BM05B-NSHSS-TBT(LF)(SN)")
      (fields (field (name "Manufacturer") "JST"))
      (libsource (lib "") (part "BM05B-NSHSS-TBT(LF)(SN)"))
    )
    (comp (ref "CN15")
      (value "BM05B-NSHSS-TBT(LF)(SN)")
      (fields (field (name "Manufacturer") "JST"))
      (libsource (lib "") (part "BM05B-NSHSS-TBT(LF)(SN)"))
    )
    (comp (ref "CN16")
      (value "BM05B-NSHSS-TBT(LF)(SN)")
      (fields (field (name "Manufacturer") "JST"))
      (libsource (lib "") (part "BM05B-NSHSS-TBT(LF)(SN)"))
    )
    (comp (ref "CN17")
      (value "BM05B-NSHSS-TBT(LF)(SN)")
      (fields (field (name "Manufacturer") "JST"))
      (libsource (lib "") (part "BM05B-NSHSS-TBT(LF)(SN)"))
    )
    (comp (ref "CN18")
      (value "BM05B-NSHSS-TBT(LF)(SN)")
      (fields (field (name "Manufacturer") "JST"))
      (libsource (lib "") (part "BM05B-NSHSS-TBT(LF)(SN)"))
    )
    (comp (ref "H1")
      (value "TSW-103-07-T-S")
      (fields (field (name "Manufacturer") "SAMTEC"))
      (libsource (lib "") (part "TSW-103-07-T-S"))
    )
    (comp (ref "J25")
      (value "5013310207")
      (fields (field (name "Manufacturer") "Molex"))
      (libsource (lib "") (part "5013310207"))
    )
    (comp (ref "R50")
      (value "21.5Ω")
      (fields
        (field (name "Manufacturer Part") "0603WAF1002T5E")
        (field (name "Manufacturer") "UNI-ROYAL(厚声)")
      )
      (libsource (lib "") (part "0603WAF1002T5E_1"))
    )
    (comp (ref "R51")
      (value "21.5Ω")
      (fields
        (field (name "Manufacturer Part") "0603WAF1002T5E")
        (field (name "Manufacturer") "UNI-ROYAL(厚声)")
      )
      (libsource (lib "") (part "0603WAF1002T5E_1"))
    )
    (comp (ref "R52")
      (value "21.5Ω")
      (fields
        (field (name "Manufacturer Part") "0603WAF1002T5E")
        (field (name "Manufacturer") "UNI-ROYAL(厚声)")
      )
      (libsource (lib "") (part "0603WAF1002T5E_1"))
    )
    (comp (ref "R53")
      (value "21.5Ω")
      (fields
        (field (name "Manufacturer Part") "0603WAF1002T5E")
        (field (name "Manufacturer") "UNI-ROYAL(厚声)")
      )
      (libsource (lib "") (part "0603WAF1002T5E_1"))
    )
    (comp (ref "R54")
      (value "21.5Ω")
      (fields
        (field (name "Manufacturer Part") "0603WAF1002T5E")
        (field (name "Manufacturer") "UNI-ROYAL(厚声)")
      )
      (libsource (lib "") (part "0603WAF1002T5E_1"))
    )
    (comp (ref "R55")
      (value "21.5Ω")
      (fields
        (field (name "Manufacturer Part") "0603WAF1002T5E")
        (field (name "Manufacturer") "UNI-ROYAL(厚声)")
      )
      (libsource (lib "") (part "0603WAF1002T5E_1"))
    )
    (comp (ref "R56")
      (value "21.5Ω")
      (fields
        (field (name "Manufacturer Part") "0603WAF1002T5E")
        (field (name "Manufacturer") "UNI-ROYAL(厚声)")
      )
      (libsource (lib "") (part "0603WAF1002T5E_1"))
    )
    (comp (ref "R57")
      (value "21.5Ω")
      (fields
        (field (name "Manufacturer Part") "0603WAF1002T5E")
        (field (name "Manufacturer") "UNI-ROYAL(厚声)")
      )
      (libsource (lib "") (part "0603WAF1002T5E_1"))
    )
    (comp (ref "R58")
      (value "21.5Ω")
      (fields
        (field (name "Manufacturer Part") "0603WAF1002T5E")
        (field (name "Manufacturer") "UNI-ROYAL(厚声)")
      )
      (libsource (lib "") (part "0603WAF1002T5E_1"))
    )
    (comp (ref "R59")
      (value "21.5Ω")
      (fields
        (field (name "Manufacturer Part") "0603WAF1002T5E")
        (field (name "Manufacturer") "UNI-ROYAL(厚声)")
      )
      (libsource (lib "") (part "0603WAF1002T5E_1"))
    )
    (comp (ref "R60")
      (value "21.5Ω")
      (fields
        (field (name "Manufacturer Part") "0603WAF1002T5E")
        (field (name "Manufacturer") "UNI-ROYAL(厚声)")
      )
      (libsource (lib "") (part "0603WAF1002T5E_1"))
    )
    (comp (ref "R61")
      (value "21.5Ω")
      (fields
        (field (name "Manufacturer Part") "0603WAF1002T5E")
        (field (name "Manufacturer") "UNI-ROYAL(厚声)")
      )
      (libsource (lib "") (part "0603WAF1002T5E_1"))
    )
    (comp (ref "R62")
      (value "21.5Ω")
      (fields
        (field (name "Manufacturer Part") "0603WAF1002T5E")
        (field (name "Manufacturer") "UNI-ROYAL(厚声)")
      )
      (libsource (lib "") (part "0603WAF1002T5E_1"))
    )
    (comp (ref "R63")
      (value "21.5Ω")
      (fields
        (field (name "Manufacturer Part") "0603WAF1002T5E")
        (field (name "Manufacturer") "UNI-ROYAL(厚声)")
      )
      (libsource (lib "") (part "0603WAF1002T5E_1"))
    )
    (comp (ref "R64")
      (value "21.5Ω")
      (fields
        (field (name "Manufacturer Part") "0603WAF1002T5E")
        (field (name "Manufacturer") "UNI-ROYAL(厚声)")
      )
      (libsource (lib "") (part "0603WAF1002T5E_1"))
    )
    (comp (ref "R65")
      (value "21.5Ω")
      (fields
        (field (name "Manufacturer Part") "0603WAF1002T5E")
        (field (name "Manufacturer") "UNI-ROYAL(厚声)")
      )
      (libsource (lib "") (part "0603WAF1002T5E_1"))
    )
    (comp (ref "R66")
      (value "21.5Ω")
      (fields
        (field (name "Manufacturer Part") "0603WAF1002T5E")
        (field (name "Manufacturer") "UNI-ROYAL(厚声)")
      )
      (libsource (lib "") (part "0603WAF1002T5E_1"))
    )
    (comp (ref "R67")
      (value "21.5Ω")
      (fields
        (field (name "Manufacturer Part") "0603WAF1002T5E")
        (field (name "Manufacturer") "UNI-ROYAL(厚声)")
      )
      (libsource (lib "") (part "0603WAF1002T5E_1"))
    )
    (comp (ref "R68")
      (value "3.48kΩ")
      (fields
        (field (name "Manufacturer Part") "0603WAF1500T5E")
        (field (name "Manufacturer") "UNI-ROYAL(厚声)")
      )
      (libsource (lib "") (part "0603WAF1500T5E"))
    )
    (comp (ref "R69")
      (value "3.48kΩ")
      (fields
        (field (name "Manufacturer Part") "0603WAF1500T5E")
        (field (name "Manufacturer") "UNI-ROYAL(厚声)")
      )
      (libsource (lib "") (part "0603WAF1500T5E"))
    )
    (comp (ref "R70")
      (value "3.48kΩ")
      (fields
        (field (name "Manufacturer Part") "0603WAF1500T5E")
        (field (name "Manufacturer") "UNI-ROYAL(厚声)")
      )
      (libsource (lib "") (part "0603WAF1500T5E"))
    )
    (comp (ref "R71")
      (value "3.48kΩ")
      (fields
        (field (name "Manufacturer Part") "0603WAF1500T5E")
        (field (name "Manufacturer") "UNI-ROYAL(厚声)")
      )
      (libsource (lib "") (part "0603WAF1500T5E"))
    )
    (comp (ref "R72")
      (value "3.48kΩ")
      (fields
        (field (name "Manufacturer Part") "0603WAF1500T5E")
        (field (name "Manufacturer") "UNI-ROYAL(厚声)")
      )
      (libsource (lib "") (part "0603WAF1500T5E"))
    )
    (comp (ref "R73")
      (value "3.48kΩ")
      (fields
        (field (name "Manufacturer Part") "0603WAF1500T5E")
        (field (name "Manufacturer") "UNI-ROYAL(厚声)")
      )
      (libsource (lib "") (part "0603WAF1500T5E"))
    )
    (comp (ref "R74")
      (value "3.48kΩ")
      (fields
        (field (name "Manufacturer Part") "0603WAF1500T5E")
        (field (name "Manufacturer") "UNI-ROYAL(厚声)")
      )
      (libsource (lib "") (part "0603WAF1500T5E"))
    )
    (comp (ref "R75")
      (value "3.48kΩ")
      (fields
        (field (name "Manufacturer Part") "0603WAF1500T5E")
        (field (name "Manufacturer") "UNI-ROYAL(厚声)")
      )
      (libsource (lib "") (part "0603WAF1500T5E"))
    )
    (comp (ref "R76")
      (value "3.48kΩ")
      (fields
        (field (name "Manufacturer Part") "0603WAF1500T5E")
        (field (name "Manufacturer") "UNI-ROYAL(厚声)")
      )
      (libsource (lib "") (part "0603WAF1500T5E"))
    )
    (comp (ref "R77")
      (value "3.48kΩ")
      (fields
        (field (name "Manufacturer Part") "0603WAF1500T5E")
        (field (name "Manufacturer") "UNI-ROYAL(厚声)")
      )
      (libsource (lib "") (part "0603WAF1500T5E"))
    )
    (comp (ref "R78")
      (value "3.48kΩ")
      (fields
        (field (name "Manufacturer Part") "0603WAF1500T5E")
        (field (name "Manufacturer") "UNI-ROYAL(厚声)")
      )
      (libsource (lib "") (part "0603WAF1500T5E"))
    )
    (comp (ref "R79")
      (value "3.48kΩ")
      (fields
        (field (name "Manufacturer Part") "0603WAF1500T5E")
        (field (name "Manufacturer") "UNI-ROYAL(厚声)")
      )
      (libsource (lib "") (part "0603WAF1500T5E"))
    )
    (comp (ref "R80")
      (value "3.48kΩ")
      (fields
        (field (name "Manufacturer Part") "0603WAF1500T5E")
        (field (name "Manufacturer") "UNI-ROYAL(厚声)")
      )
      (libsource (lib "") (part "0603WAF1500T5E"))
    )
    (comp (ref "R81")
      (value "3.48kΩ")
      (fields
        (field (name "Manufacturer Part") "0603WAF1500T5E")
        (field (name "Manufacturer") "UNI-ROYAL(厚声)")
      )
      (libsource (lib "") (part "0603WAF1500T5E"))
    )
    (comp (ref "R82")
      (value "3.48kΩ")
      (fields
        (field (name "Manufacturer Part") "0603WAF1500T5E")
        (field (name "Manufacturer") "UNI-ROYAL(厚声)")
      )
      (libsource (lib "") (part "0603WAF1500T5E"))
    )
    (comp (ref "R83")
      (value "3.48kΩ")
      (fields
        (field (name "Manufacturer Part") "0603WAF1500T5E")
        (field (name "Manufacturer") "UNI-ROYAL(厚声)")
      )
      (libsource (lib "") (part "0603WAF1500T5E"))
    )
    (comp (ref "R84")
      (value "3.48kΩ")
      (fields
        (field (name "Manufacturer Part") "0603WAF1500T5E")
        (field (name "Manufacturer") "UNI-ROYAL(厚声)")
      )
      (libsource (lib "") (part "0603WAF1500T5E"))
    )
    (comp (ref "R85")
      (value "3.48kΩ")
      (fields
        (field (name "Manufacturer Part") "0603WAF1500T5E")
        (field (name "Manufacturer") "UNI-ROYAL(厚声)")
      )
      (libsource (lib "") (part "0603WAF1500T5E"))
    )
    (comp (ref "R86")
      (value "3.48kΩ")
      (fields
        (field (name "Manufacturer Part") "0603WAF1500T5E")
        (field (name "Manufacturer") "UNI-ROYAL(厚声)")
      )
      (libsource (lib "") (part "0603WAF1500T5E"))
    )
    (comp (ref "R87")
      (value "3.48kΩ")
      (fields
        (field (name "Manufacturer Part") "0603WAF1500T5E")
        (field (name "Manufacturer") "UNI-ROYAL(厚声)")
      )
      (libsource (lib "") (part "0603WAF1500T5E"))
    )
    (comp (ref "R88")
      (value "3.48kΩ")
      (fields
        (field (name "Manufacturer Part") "0603WAF1500T5E")
        (field (name "Manufacturer") "UNI-ROYAL(厚声)")
      )
      (libsource (lib "") (part "0603WAF1500T5E"))
    )
    (comp (ref "R89")
      (value "3.48kΩ")
      (fields
        (field (name "Manufacturer Part") "0603WAF1500T5E")
        (field (name "Manufacturer") "UNI-ROYAL(厚声)")
      )
      (libsource (lib "") (part "0603WAF1500T5E"))
    )
    (comp (ref "R90")
      (value "3.48kΩ")
      (fields
        (field (name "Manufacturer Part") "0603WAF1500T5E")
        (field (name "Manufacturer") "UNI-ROYAL(厚声)")
      )
      (libsource (lib "") (part "0603WAF1500T5E"))
    )
    (comp (ref "R91")
      (value "3.48kΩ")
      (fields
        (field (name "Manufacturer Part") "0603WAF1500T5E")
        (field (name "Manufacturer") "UNI-ROYAL(厚声)")
      )
      (libsource (lib "") (part "0603WAF1500T5E"))
    )
    (comp (ref "R92")
      (value "3.48kΩ")
      (fields
        (field (name "Manufacturer Part") "0603WAF1500T5E")
        (field (name "Manufacturer") "UNI-ROYAL(厚声)")
      )
      (libsource (lib "") (part "0603WAF1500T5E"))
    )
    (comp (ref "R93")
      (value "3.48kΩ")
      (fields
        (field (name "Manufacturer Part") "0603WAF1500T5E")
        (field (name "Manufacturer") "UNI-ROYAL(厚声)")
      )
      (libsource (lib "") (part "0603WAF1500T5E"))
    )
    (comp (ref "R94")
      (value "3.48kΩ")
      (fields
        (field (name "Manufacturer Part") "0603WAF1500T5E")
        (field (name "Manufacturer") "UNI-ROYAL(厚声)")
      )
      (libsource (lib "") (part "0603WAF1500T5E"))
    )
    (comp (ref "R95")
      (value "3.48kΩ")
      (fields
        (field (name "Manufacturer Part") "0603WAF1500T5E")
        (field (name "Manufacturer") "UNI-ROYAL(厚声)")
      )
      (libsource (lib "") (part "0603WAF1500T5E"))
    )
    (comp (ref "R96")
      (value "3.48kΩ")
      (fields
        (field (name "Manufacturer Part") "0603WAF1500T5E")
        (field (name "Manufacturer") "UNI-ROYAL(厚声)")
      )
      (libsource (lib "") (part "0603WAF1500T5E"))
    )
    (comp (ref "R97")
      (value "3.48kΩ")
      (fields
        (field (name "Manufacturer Part") "0603WAF1500T5E")
        (field (name "Manufacturer") "UNI-ROYAL(厚声)")
      )
      (libsource (lib "") (part "0603WAF1500T5E"))
    )
    (comp (ref "R98")
      (value "3.48kΩ")
      (fields
        (field (name "Manufacturer Part") "0603WAF1500T5E")
        (field (name "Manufacturer") "UNI-ROYAL(厚声)")
      )
      (libsource (lib "") (part "0603WAF1500T5E"))
    )
    (comp (ref "R99")
      (value "3.48kΩ")
      (fields
        (field (name "Manufacturer Part") "0603WAF1500T5E")
        (field (name "Manufacturer") "UNI-ROYAL(厚声)")
      )
      (libsource (lib "") (part "0603WAF1500T5E"))
    )
    (comp (ref "R100")
      (value "10kΩ")
      (fields
        (field (name "Manufacturer Part") "0603WAF1500T5E")
        (field (name "Manufacturer") "UNI-ROYAL(厚声)")
      )
      (libsource (lib "") (part "0603WAF1500T5E"))
    )
    (comp (ref "R101")
      (value "150Ω")
      (fields
        (field (name "Manufacturer Part") "0603WAF1500T5E")
        (field (name "Manufacturer") "UNI-ROYAL(厚声)")
      )
      (libsource (lib "") (part "0603WAF1500T5E"))
    )
    (comp (ref "R102")
      (value "51.1")
      (fields
        (field (name "Manufacturer Part") "0603WAF1002T5E")
        (field (name "Manufacturer") "UNI-ROYAL(厚声)")
      )
      (libsource (lib "") (part "0603WAF1002T5E_1"))
    )
    (comp (ref "R103")
      (value "10kΩ")
      (fields
        (field (name "Manufacturer Part") "0603WAF1002T5E")
        (field (name "Manufacturer") "UNI-ROYAL(厚声)")
      )
      (libsource (lib "") (part "0603WAF1002T5E"))
    )
    (comp (ref "R104")
      (value "150Ω")
      (fields
        (field (name "Manufacturer Part") "0603WAF1500T5E")
        (field (name "Manufacturer") "UNI-ROYAL(厚声)")
      )
      (libsource (lib "") (part "0603WAF1500T5E"))
    )
    (comp (ref "R105")
      (value "51.1")
      (fields
        (field (name "Manufacturer Part") "0603WAF1002T5E")
        (field (name "Manufacturer") "UNI-ROYAL(厚声)")
      )
      (libsource (lib "") (part "0603WAF1002T5E_1"))
    )
    (comp (ref "R106")
      (value "51.1")
      (fields
        (field (name "Manufacturer Part") "0603WAF1002T5E")
        (field (name "Manufacturer") "UNI-ROYAL(厚声)")
      )
      (libsource (lib "") (part "0603WAF1002T5E_1"))
    )
    (comp (ref "R107")
      (value "51.1")
      (fields
        (field (name "Manufacturer Part") "0603WAF1002T5E")
        (field (name "Manufacturer") "UNI-ROYAL(厚声)")
      )
      (libsource (lib "") (part "0603WAF1002T5E_1"))
    )
    (comp (ref "R108")
      (value "10kΩ")
      (fields
        (field (name "Manufacturer Part") "0603WAF1002T5E")
        (field (name "Manufacturer") "UNI-ROYAL(厚声)")
      )
      (libsource (lib "") (part "0603WAF1002T5E"))
    )
    (comp (ref "R109")
      (value "10kΩ")
      (fields
        (field (name "Manufacturer Part") "0603WAF1002T5E")
        (field (name "Manufacturer") "UNI-ROYAL(厚声)")
      )
      (libsource (lib "") (part "0603WAF1002T5E"))
    )
    (comp (ref "R110")
      (value "51.1")
      (fields
        (field (name "Manufacturer Part") "0603WAF1002T5E")
        (field (name "Manufacturer") "UNI-ROYAL(厚声)")
      )
      (libsource (lib "") (part "0603WAF1002T5E_1"))
    )
    (comp (ref "R111")
      (value "51.1")
      (fields
        (field (name "Manufacturer Part") "0603WAF1002T5E")
        (field (name "Manufacturer") "UNI-ROYAL(厚声)")
      )
      (libsource (lib "") (part "0603WAF1002T5E_1"))
    )
    (comp (ref "R112")
      (value "10kΩ")
      (fields
        (field (name "Manufacturer Part") "0603WAF1002T5E")
        (field (name "Manufacturer") "UNI-ROYAL(厚声)")
      )
      (libsource (lib "") (part "0603WAF1002T5E"))
    )
    (comp (ref "R113")
      (value "10kΩ")
      (fields (field (name "Manufacturer Part") "RC0402JR-070RL") (field (name "Manufacturer") "YAGEO(国巨)"))
      (libsource (lib "") (part "RC0402JR-070RL"))
    )
    (comp (ref "R114")
      (value "51.1")
      (fields
        (field (name "Manufacturer Part") "0603WAF1002T5E")
        (field (name "Manufacturer") "UNI-ROYAL(厚声)")
      )
      (libsource (lib "") (part "0603WAF1002T5E_1"))
    )
    (comp (ref "R115")
      (value "5.11MΩ")
      (fields
        (field (name "Manufacturer Part") "0603WAF1500T5E")
        (field (name "Manufacturer") "UNI-ROYAL(厚声)")
      )
      (libsource (lib "") (part "0603WAF1500T5E_1"))
    )
    (comp (ref "R116")
      (value "51.1")
      (fields
        (field (name "Manufacturer Part") "0603WAF1002T5E")
        (field (name "Manufacturer") "UNI-ROYAL(厚声)")
      )
      (libsource (lib "") (part "0603WAF1002T5E_1"))
    )
    (comp (ref "R117")
      (value "8.6kΩ")
      (fields
        (field (name "Manufacturer Part") "0603WAF1500T5E")
        (field (name "Manufacturer") "UNI-ROYAL(厚声)")
      )
      (libsource (lib "") (part "0603WAF1500T5E_2"))
    )
    (comp (ref "R118")
      (value "10kΩ")
      (fields
        (field (name "Manufacturer Part") "0603WAF1002T5E")
        (field (name "Manufacturer") "UNI-ROYAL(厚声)")
      )
      (libsource (lib "") (part "0603WAF1002T5E"))
    )
    (comp (ref "R119")
      (value "10kΩ")
      (fields
        (field (name "Manufacturer Part") "0603WAF1002T5E")
        (field (name "Manufacturer") "UNI-ROYAL(厚声)")
      )
      (libsource (lib "") (part "0603WAF1002T5E"))
    )
    (comp (ref "R120")
      (value "10kΩ")
      (fields (field (name "Manufacturer Part") "RC0402JR-070RL") (field (name "Manufacturer") "YAGEO(国巨)"))
      (libsource (lib "") (part "RC0402JR-070RL"))
    )
    (comp (ref "R121")
      (value "10kΩ")
      (fields (field (name "Manufacturer Part") "RC0402JR-070RL") (field (name "Manufacturer") "YAGEO(国巨)"))
      (libsource (lib "") (part "RC0402JR-070RL"))
    )
    (comp (ref "R122")
      (value "10kΩ")
      (fields (field (name "Manufacturer Part") "RC0402JR-070RL") (field (name "Manufacturer") "YAGEO(国巨)"))
      (libsource (lib "") (part "RC0402JR-070RL"))
    )
    (comp (ref "U46")
      (value "XC6124E628MR-G")
      (fields (field (name "Manufacturer") "TOREX(特瑞仕)"))
      (libsource (lib "") (part "XC6124E628MR-G"))
    )
    (comp (ref "U47")
      (value "SN74LVC541APWR_C113281")
      (fields (field (name "Manufacturer Part") "SN74LVC541APWR") (field (name "Manufacturer") "TI(德州仪器)"))
      (libsource (lib "") (part "SN74LVC541APWR_C113281"))
    )
    (comp (ref "U48")
      (value "74LVC2G17GW-Q100H")
      (fields (field (name "Manufacturer") "Nexperia(安世)"))
      (libsource (lib "") (part "74LVC2G17GW-Q100H"))
    )
    (comp (ref "U49")
      (value "SN74LVC541APWR_C113281")
      (fields (field (name "Manufacturer Part") "SN74LVC541APWR") (field (name "Manufacturer") "TI(德州仪器)"))
      (libsource (lib "") (part "SN74LVC541APWR_C113281"))
    )
    (comp (ref "U50")
      (value "PCA9546ADR")
      (fields (field (name "Manufacturer") "TI(德州仪器)"))
      (libsource (lib "") (part "PCA9546ADR"))
    )
    (comp (ref "U51")
      (value "PCA9546ADR")
      (fields (field (name "Manufacturer") "TI(德州仪器)"))
      (libsource (lib "") (part "PCA9546ADR"))
    )
    (comp (ref "U52")
      (value "PCA9546ADR")
      (fields (field (name "Manufacturer") "TI(德州仪器)"))
      (libsource (lib "") (part "PCA9546ADR"))
    )
    (comp (ref "U53")
      (value "PCA9546ADR")
      (fields (field (name "Manufacturer") "TI(德州仪器)"))
      (libsource (lib "") (part "PCA9546ADR"))
    )
    (comp (ref "U54") (value "ND120-SM02-R") (libsource (lib "") (part "ND120-SM02-R")))
    (comp (ref "U55")
      (value "MIC184YM")
      (fields (field (name "Manufacturer") "MICROCHIP(美国微芯)"))
      (libsource (lib "") (part "MIC184YM"))
    )
    (comp (ref "U56") (value "ND120-SM02-R") (libsource (lib "") (part "ND120-SM02-R")))
    (comp (ref "U57") (value "ND120-SM02-R") (libsource (lib "") (part "ND120-SM02-R")))
    (comp (ref "U58")
      (value "74LVC2G17GW-Q100H")
      (fields (field (name "Manufacturer") "Nexperia(安世)"))
      (libsource (lib "") (part "74LVC2G17GW-Q100H"))
    )
    (comp (ref "U59")
      (value "74LVC2G17GW-Q100H")
      (fields (field (name "Manufacturer") "Nexperia(安世)"))
      (libsource (lib "") (part "74LVC2G17GW-Q100H"))
    )
    (comp (ref "U60")
      (value "74LVC2G17GW-Q100H")
      (fields (field (name "Manufacturer") "Nexperia(安世)"))
      (libsource (lib "") (part "74LVC2G17GW-Q100H"))
    )
    (comp (ref "U61") (value "0768290002") (libsource (lib "") (part "0768290002")))
    (comp (ref "U62") (value "0768290002") (libsource (lib "") (part "0768290002")))
    (comp (ref "U63")
      (value "74LVC2G17GW-Q100H")
      (fields (field (name "Manufacturer") "Nexperia(安世)"))
      (libsource (lib "") (part "74LVC2G17GW-Q100H"))
    )
    (comp (ref "U64")
      (value "IRLR6225PBF")
      (fields (field (name "Manufacturer") "Infineon(英飞凌)"))
      (libsource (lib "") (part "IRLR6225PBF"))
    )
    (comp (ref "U65")
      (value "IRLR6225PBF")
      (fields (field (name "Manufacturer") "Infineon(英飞凌)"))
      (libsource (lib "") (part "IRLR6225PBF"))
    )
    (comp (ref "U66")
      (value "74LVC2G17GW-Q100H")
      (fields (field (name "Manufacturer") "Nexperia(安世)"))
      (libsource (lib "") (part "74LVC2G17GW-Q100H"))
    )
    (comp (ref "U67")
      (value "74LVC2G17GW-Q100H")
      (fields (field (name "Manufacturer") "Nexperia(安世)"))
      (libsource (lib "") (part "74LVC2G17GW-Q100H"))
    )
    (comp (ref "U68")
      (value "ADS122C04IPWR")
      (fields (field (name "Manufacturer") "TI(德州仪器)"))
      (libsource (lib "") (part "ADS122C04IPWR"))
    )
    (comp (ref "U69") (value "PROMICRO32U4") (libsource (lib "") (part "PROMICRO32U4")))
    (comp (ref "U75") (value "0768290002") (libsource (lib "") (part "0768290002")))
    (comp (ref "U76")
      (value "IRLR6225PBF")
      (fields (field (name "Manufacturer") "Infineon(英飞凌)"))
      (libsource (lib "") (part "IRLR6225PBF"))
    )
  )
  (nets
    (net (code "1") (name "3.3") (class "Default")
      (node (ref "R113") (pin "1") (pinfunction "1_1") (pintype "input"))
      (node (ref "U46") (pin "5") (pinfunction "VIN_5") (pintype "unspecified"))
      (node (ref "U55") (pin "8") (pinfunction "VDD_8") (pintype "unspecified"))
    )
    (net (code "2") (name "3.3V") (class "Default")
      (node (ref "C60") (pin "1") (pinfunction "1_1") (pintype "unspecified"))
      (node (ref "C61") (pin "2") (pinfunction "2_2") (pintype "unspecified"))
      (node (ref "C62") (pin "2") (pinfunction "2_2") (pintype "unspecified"))
      (node (ref "C63") (pin "2") (pinfunction "2_2") (pintype "unspecified"))
      (node (ref "C64") (pin "2") (pinfunction "2_2") (pintype "unspecified"))
      (node (ref "C65") (pin "2") (pinfunction "2_2") (pintype "unspecified"))
      (node (ref "C67") (pin "2") (pinfunction "2_2") (pintype "unspecified"))
      (node (ref "C71") (pin "2") (pinfunction "2_2") (pintype "unspecified"))
      (node (ref "C72") (pin "2") (pinfunction "2_2") (pintype "unspecified"))
      (node (ref "C73") (pin "2") (pinfunction "2_2") (pintype "unspecified"))
      (node (ref "R115") (pin "1") (pinfunction "1_1") (pintype "input"))
      (node (ref "R123") (pin "2") (pinfunction "2_2") (pintype "unspecified"))
      (node (ref "R43") (pin "2") (pinfunction "2_2") (pintype "input"))
      (node (ref "R68") (pin "2") (pinfunction "2_2") (pintype "input"))
      (node (ref "R69") (pin "2") (pinfunction "2_2") (pintype "input"))
      (node (ref "R70") (pin "2") (pinfunction "2_2") (pintype "input"))
      (node (ref "R71") (pin "2") (pinfunction "2_2") (pintype "input"))
      (node (ref "R72") (pin "2") (pinfunction "2_2") (pintype "input"))
      (node (ref "R73") (pin "2") (pinfunction "2_2") (pintype "input"))
      (node (ref "R74") (pin "2") (pinfunction "2_2") (pintype "input"))
      (node (ref "R75") (pin "2") (pinfunction "2_2") (pintype "input"))
      (node (ref "R76") (pin "2") (pinfunction "2_2") (pintype "input"))
      (node (ref "R77") (pin "2") (pinfunction "2_2") (pintype "input"))
      (node (ref "R78") (pin "2") (pinfunction "2_2") (pintype "input"))
      (node (ref "R79") (pin "2") (pinfunction "2_2") (pintype "input"))
      (node (ref "R80") (pin "2") (pinfunction "2_2") (pintype "input"))
      (node (ref "R81") (pin "2") (pinfunction "2_2") (pintype "input"))
      (node (ref "R82") (pin "2") (pinfunction "2_2") (pintype "input"))
      (node (ref "R83") (pin "2") (pinfunction "2_2") (pintype "input"))
      (node (ref "R84") (pin "2") (pinfunction "2_2") (pintype "input"))
      (node (ref "R85") (pin "2") (pinfunction "2_2") (pintype "input"))
      (node (ref "R86") (pin "2") (pinfunction "2_2") (pintype "input"))
      (node (ref "R87") (pin "2") (pinfunction "2_2") (pintype "input"))
      (node (ref "R88") (pin "2") (pinfunction "2_2") (pintype "input"))
      (node (ref "R89") (pin "2") (pinfunction "2_2") (pintype "input"))
      (node (ref "R90") (pin "2") (pinfunction "2_2") (pintype "input"))
      (node (ref "R91") (pin "2") (pinfunction "2_2") (pintype "input"))
      (node (ref "R92") (pin "2") (pinfunction "2_2") (pintype "input"))
      (node (ref "R93") (pin "2") (pinfunction "2_2") (pintype "input"))
      (node (ref "R94") (pin "2") (pinfunction "2_2") (pintype "input"))
      (node (ref "R95") (pin "2") (pinfunction "2_2") (pintype "input"))
      (node (ref "R96") (pin "2") (pinfunction "2_2") (pintype "input"))
      (node (ref "R97") (pin "2") (pinfunction "2_2") (pintype "input"))
      (node (ref "R98") (pin "2") (pinfunction "2_2") (pintype "input"))
      (node (ref "R99") (pin "2") (pinfunction "2_2") (pintype "input"))
      (node (ref "U47") (pin "20") (pinfunction "VCC_20") (pintype "unspecified"))
      (node (ref "U48") (pin "5") (pinfunction "VCC_5") (pintype "unspecified"))
      (node (ref "U49") (pin "20") (pinfunction "VCC_20") (pintype "unspecified"))
      (node (ref "U50") (pin "13") (pinfunction "A2_13") (pintype "unspecified"))
      (node (ref "U50") (pin "16") (pinfunction "VCC_16") (pintype "unspecified"))
      (node (ref "U51") (pin "1") (pinfunction "A0_1") (pintype "unspecified"))
      (node (ref "U51") (pin "13") (pinfunction "A2_13") (pintype "unspecified"))
      (node (ref "U51") (pin "16") (pinfunction "VCC_16") (pintype "unspecified"))
      (node (ref "U52") (pin "13") (pinfunction "A2_13") (pintype "unspecified"))
      (node (ref "U52") (pin "16") (pinfunction "VCC_16") (pintype "unspecified"))
      (node (ref "U52") (pin "2") (pinfunction "A1_2") (pintype "unspecified"))
      (node (ref "U53") (pin "1") (pinfunction "A0_1") (pintype "unspecified"))
      (node (ref "U53") (pin "13") (pinfunction "A2_13") (pintype "unspecified"))
      (node (ref "U53") (pin "16") (pinfunction "VCC_16") (pintype "unspecified"))
      (node (ref "U53") (pin "2") (pinfunction "A1_2") (pintype "unspecified"))
      (node (ref "U54") (pin "9") (pinfunction "VDD_9") (pintype "unspecified"))
      (node (ref "U56") (pin "9") (pinfunction "VDD_9") (pintype "unspecified"))
      (node (ref "U57") (pin "9") (pinfunction "VDD_9") (pintype "unspecified"))
      (node (ref "U59") (pin "5") (pinfunction "VCC_5") (pintype "unspecified"))
      (node (ref "U60") (pin "5") (pinfunction "VCC_5") (pintype "unspecified"))
      (node (ref "U63") (pin "5") (pinfunction "VCC_5") (pintype "unspecified"))
      (node (ref "U67") (pin "5") (pinfunction "VCC_5") (pintype "unspecified"))
      (node (ref "U68") (pin "12") (pinfunction "AVDD_12") (pintype "unspecified"))
      (node (ref "U68") (pin "13") (pinfunction "DVDD_13") (pintype "unspecified"))
      (node (ref "U69") (pin "RAWVRAW") (pinfunction "RAWVRAW_RAWVRAW") (pintype "unspecified"))
      (node (ref "U70") (pin "4") (pinfunction "Vout_4") (pintype "unspecified"))
    )
    (net (code "3") (name "5V") (class "Default")
      (node (ref "C49") (pin "2") (pinfunction "2_2") (pintype "unspecified"))
      (node (ref "C50") (pin "2") (pinfunction "2_2") (pintype "unspecified"))
      (node (ref "C51") (pin "2") (pinfunction "2_2") (pintype "unspecified"))
      (node (ref "C52") (pin "2") (pinfunction "2_2") (pintype "unspecified"))
      (node (ref "C53") (pin "2") (pinfunction "2_2") (pintype "unspecified"))
      (node (ref "C55") (pin "1") (pinfunction "1_1") (pintype "input"))
      (node (ref "CN1") (pin "1") (pinfunction "1_1") (pintype "unspecified"))
      (node (ref "CN10") (pin "1") (pinfunction "1_1") (pintype "unspecified"))
      (node (ref "CN2") (pin "1") (pinfunction "1_1") (pintype "unspecified"))
      (node (ref "CN3") (pin "1") (pinfunction "1_1") (pintype "unspecified"))
      (node (ref "CN4") (pin "1") (pinfunction "1_1") (pintype "unspecified"))
      (node (ref "CN5") (pin "1") (pinfunction "1_1") (pintype "unspecified"))
      (node (ref "CN6") (pin "1") (pinfunction "1_1") (pintype "unspecified"))
      (node (ref "CN7") (pin "1") (pinfunction "1_1") (pintype "unspecified"))
      (node (ref "CN8") (pin "1") (pinfunction "1_1") (pintype "unspecified"))
      (node (ref "CN9") (pin "1") (pinfunction "1_1") (pintype "unspecified"))
      (node (ref "D1") (pin "3") (pinfunction "3_3") (pintype "unspecified"))
      (node (ref "R101") (pin "2") (pinfunction "2_2") (pintype "input"))
      (node (ref "R37") (pin "2") (pinfunction "2_2") (pintype "unspecified"))
      (node (ref "U26") (pin "1") (pinfunction "VOUT_1") (pintype "unspecified"))
      (node (ref "U26") (pin "2") (pinfunction "VOUT_2") (pintype "unspecified"))
      (node (ref "U26") (pin "3") (pinfunction "VOUT_3") (pintype "unspecified"))
      (node (ref "U26") (pin "4") (pinfunction "+S_4") (pintype "unspecified"))
      (node (ref "U58") (pin "5") (pinfunction "VCC_5") (pintype "unspecified"))
      (node (ref "U66") (pin "5") (pinfunction "VCC_5") (pintype "unspecified"))
    )
    (net (code "4") (name "5V_Power_On_L") (class "Default")
      (node (ref "Q5") (pin "1") (pinfunction "G_1") (pintype "unspecified"))
      (node (ref "R121") (pin "2") (pinfunction "2_2") (pintype "input"))
      (node (ref "U69") (pin "D8") (pinfunction "D8_D8") (pintype "unspecified"))
    )
    (net (code "5") (name "12V") (class "Default")
      (node (ref "C58") (pin "1") (pinfunction "1_1") (pintype "input"))
      (node (ref "R40") (pin "2") (pinfunction "2_2") (pintype "unspecified"))
      (node (ref "U27") (pin "7") (pinfunction "+Sense_7") (pintype "passive"))
      (node (ref "U27") (pin "8") (pinfunction "+Vout_8") (pintype "passive"))
      (node (ref "U30") (pin "2") (pinfunction "PV+_2") (pintype "unspecified"))
      (node (ref "U33") (pin "2") (pinfunction "PV+_2") (pintype "unspecified"))
      (node (ref "U35") (pin "2") (pinfunction "PV+_2") (pintype "unspecified"))
    )
    (net (code "6") (name "12V_Power_On_L") (class "Default")
      (node (ref "Q6") (pin "1") (pinfunction "G_1") (pintype "unspecified"))
      (node (ref "R122") (pin "2") (pinfunction "2_2") (pintype "input"))
      (node (ref "U69") (pin "D9") (pinfunction "D9_D9") (pintype "unspecified"))
    )
    (net (code "7") (name "15V") (class "Default")
      (node (ref "C54") (pin "1") (pinfunction "1_1") (pintype "input"))
      (node (ref "C56") (pin "2") (pinfunction "2_2") (pintype "unspecified"))
      (node (ref "C57") (pin "1") (pinfunction "1_1") (pintype "input"))
      (node (ref "CN11") (pin "1") (pinfunction "1_1") (pintype "unspecified"))
      (node (ref "CN12") (pin "1") (pinfunction "1_1") (pintype "unspecified"))
      (node (ref "CN13") (pin "1") (pinfunction "1_1") (pintype "unspecified"))
      (node (ref "CN14") (pin "1") (pinfunction "1_1") (pintype "unspecified"))
      (node (ref "CN15") (pin "1") (pinfunction "1_1") (pintype "unspecified"))
      (node (ref "CN16") (pin "1") (pinfunction "1_1") (pintype "unspecified"))
      (node (ref "CN17") (pin "1") (pinfunction "1_1") (pintype "unspecified"))
      (node (ref "CN18") (pin "1") (pinfunction "1_1") (pintype "unspecified"))
      (node (ref "R23") (pin "2") (pinfunction "2_2") (pintype "input"))
      (node (ref "R26") (pin "2") (pinfunction "2_2") (pintype "input"))
      (node (ref "R39") (pin "2") (pinfunction "2_2") (pintype "unspecified"))
      (node (ref "R5") (pin "1") (pinfunction "1_1") (pintype "input"))
      (node (ref "R6") (pin "1") (pinfunction "1_1") (pintype "input"))
      (node (ref "U26") (pin "11") (pinfunction "Vin_11") (pintype "unspecified"))
      (node (ref "U26") (pin "12") (pinfunction "Vin_12") (pintype "unspecified"))
      (node (ref "U26") (pin "13") (pinfunction "Vin_13") (pintype "unspecified"))
      (node (ref "U26") (pin "14") (pinfunction "Vin_14") (pintype "unspecified"))
      (node (ref "U27") (pin "1") (pinfunction "+Vin_1") (pintype "passive"))
      (node (ref "U28") (pin "1") (pinfunction "S_1") (pintype "unspecified"))
      (node (ref "U28") (pin "2") (pinfunction "S_2") (pintype "unspecified"))
      (node (ref "U28") (pin "3") (pinfunction "S_3") (pintype "unspecified"))
      (node (ref "U31") (pin "1") (pinfunction "1_1") (pintype "unspecified"))
      (node (ref "U32") (pin "4") (pinfunction "SOURCE_4") (pintype "unspecified"))
      (node (ref "U34") (pin "1") (pinfunction "S_1") (pintype "unspecified"))
      (node (ref "U34") (pin "2") (pinfunction "S_2") (pintype "unspecified"))
      (node (ref "U34") (pin "3") (pinfunction "S_3") (pintype "unspecified"))
      (node (ref "U37") (pin "4") (pinfunction "SOURCE_4") (pintype "unspecified"))
      (node (ref "U38") (pin "2") (pinfunction "PV+_2") (pintype "unspecified"))
      (node (ref "U40") (pin "5") (pinfunction "D_5") (pintype "unspecified"))
      (node (ref "U42") (pin "2") (pinfunction "PV+_2") (pintype "unspecified"))
      (node (ref "U61") (pin "1") (pinfunction "PV-_1") (pintype "unspecified"))
      (node (ref "U62") (pin "1") (pinfunction "PV-_1") (pintype "unspecified"))
      (node (ref "U75") (pin "1") (pinfunction "PV-_1") (pintype "unspecified"))
    )
    (net (code "8") (name "15V_A") (class "Default")
      (node (ref "Q2") (pin "2") (pinfunction "S_2") (pintype "unspecified"))
      (node (ref "R20") (pin "2") (pinfunction "2_2") (pintype "input"))
      (node (ref "R33") (pin "2") (pinfunction "2_2") (pintype "unspecified"))
      (node (ref "U28") (pin "5") (pinfunction "D_5") (pintype "unspecified"))
      (node (ref "U32") (pin "6") (pinfunction "DRAIN_6") (pintype "unspecified"))
      (node (ref "U73") (pin "2") (pinfunction "2_2") (pintype "bidirectional"))
    )
    (net (code "9") (name "15V_B") (class "Default")
      (node (ref "Q7") (pin "2") (pinfunction "S_2") (pintype "unspecified"))
      (node (ref "R29") (pin "2") (pinfunction "2_2") (pintype "input"))
      (node (ref "R34") (pin "2") (pinfunction "2_2") (pintype "unspecified"))
      (node (ref "U34") (pin "5") (pinfunction "D_5") (pintype "unspecified"))
      (node (ref "U37") (pin "6") (pinfunction "DRAIN_6") (pintype "unspecified"))
      (node (ref "U72") (pin "2") (pinfunction "2_2") (pintype "bidirectional"))
    )
    (net (code "10") (name "A{slash}D_reset_L") (class "Default")
      (node (ref "R54") (pin "2") (pinfunction "2_2") (pintype "input"))
      (node (ref "U68") (pin "3") (pinfunction "RESET#_3") (pintype "unspecified"))
    )
    (net (code "11") (name "Batt_off_L") (class "Default")
      (node (ref "Q9") (pin "1") (pinfunction "G_1") (pintype "unspecified"))
      (node (ref "R43") (pin "1") (pinfunction "1_1") (pintype "input"))
      (node (ref "U69") (pin "D14") (pinfunction "D14_D14") (pintype "unspecified"))
    )
    (net (code "12") (name "Cam_long_H") (class "Default")
      (node (ref "R108") (pin "1") (pinfunction "1_1") (pintype "input"))
      (node (ref "U59") (pin "1") (pinfunction "1A_1") (pintype "unspecified"))
      (node (ref "U59") (pin "3") (pinfunction "2A_3") (pintype "unspecified"))
      (node (ref "U69") (pin "D5") (pinfunction "D5_D5") (pintype "unspecified"))
    )
    (net (code "13") (name "Cam_short_H") (class "Default")
      (node (ref "R109") (pin "1") (pinfunction "1_1") (pintype "input"))
      (node (ref "R112") (pin "1") (pinfunction "1_1") (pintype "input"))
      (node (ref "R119") (pin "1") (pinfunction "1_1") (pintype "input"))
      (node (ref "U60") (pin "1") (pinfunction "1A_1") (pintype "unspecified"))
      (node (ref "U60") (pin "3") (pinfunction "2A_3") (pintype "unspecified"))
      (node (ref "U63") (pin "1") (pinfunction "1A_1") (pintype "unspecified"))
      (node (ref "U63") (pin "3") (pinfunction "2A_3") (pintype "unspecified"))
      (node (ref "U67") (pin "1") (pinfunction "1A_1") (pintype "unspecified"))
      (node (ref "U67") (pin "3") (pinfunction "2A_3") (pintype "unspecified"))
      (node (ref "U69") (pin "D6") (pinfunction "D6_D6") (pintype "unspecified"))
    )
    (net (code "14") (name "Charger_on_L") (class "Default")
      (node (ref "Q11") (pin "1") (pinfunction "G_1") (pintype "unspecified"))
      (node (ref "R49") (pin "2") (pinfunction "2_2") (pintype "input"))
      (node (ref "U69") (pin "D15") (pinfunction "D15_D15") (pintype "unspecified"))
    )
    (net (code "15") (name "Data_ready_L") (class "Default")
      (node (ref "U68") (pin "14") (pinfunction "DRDY#_14") (pintype "unspecified"))
      (node (ref "U69") (pin "A3") (pinfunction "A3_A3") (pintype "unspecified"))
    )
    (net (code "16") (name "Fan_H") (class "Default")
      (node (ref "U65") (pin "1") (pinfunction "G_1") (pintype "unspecified"))
      (node (ref "U69") (pin "A1") (pinfunction "A1_A1") (pintype "unspecified"))
      (node (ref "U76") (pin "1") (pinfunction "G_1") (pintype "unspecified"))
    )
    (net (code "17") (name "Filtered_15V") (class "Default")
      (node (ref "C12") (pin "2") (pinfunction "2_2") (pintype "unspecified"))
      (node (ref "C13") (pin "2") (pinfunction "2_2") (pintype "unspecified"))
      (node (ref "C16") (pin "2") (pinfunction "2_2") (pintype "unspecified"))
      (node (ref "C19") (pin "2") (pinfunction "2_2") (pintype "unspecified"))
      (node (ref "C24") (pin "2") (pinfunction "2_2") (pintype "unspecified"))
      (node (ref "C25") (pin "2") (pinfunction "2_2") (pintype "unspecified"))
      (node (ref "C28") (pin "2") (pinfunction "2_2") (pintype "unspecified"))
      (node (ref "C3") (pin "2") (pinfunction "2_2") (pintype "unspecified"))
      (node (ref "C31") (pin "2") (pinfunction "2_2") (pintype "unspecified"))
      (node (ref "C36") (pin "2") (pinfunction "2_2") (pintype "unspecified"))
      (node (ref "C37") (pin "2") (pinfunction "2_2") (pintype "unspecified"))
      (node (ref "C40") (pin "2") (pinfunction "2_2") (pintype "unspecified"))
      (node (ref "C43") (pin "2") (pinfunction "2_2") (pintype "unspecified"))
      (node (ref "C48") (pin "2") (pinfunction "2_2") (pintype "unspecified"))
      (node (ref "C5") (pin "2") (pinfunction "2_2") (pintype "unspecified"))
      (node (ref "C8") (pin "2") (pinfunction "2_2") (pintype "unspecified"))
      (node (ref "D10") (pin "2") (pinfunction "A_2") (pintype "unspecified"))
      (node (ref "D11") (pin "2") (pinfunction "A_2") (pintype "unspecified"))
      (node (ref "D12") (pin "2") (pinfunction "A_2") (pintype "unspecified"))
      (node (ref "D13") (pin "2") (pinfunction "A_2") (pintype "unspecified"))
      (node (ref "D14") (pin "2") (pinfunction "A_2") (pintype "unspecified"))
      (node (ref "D15") (pin "2") (pinfunction "A_2") (pintype "unspecified"))
      (node (ref "D16") (pin "2") (pinfunction "A_2") (pintype "unspecified"))
      (node (ref "D17") (pin "2") (pinfunction "A_2") (pintype "unspecified"))
      (node (ref "D18") (pin "2") (pinfunction "A_2") (pintype "unspecified"))
      (node (ref "D19") (pin "2") (pinfunction "A_2") (pintype "unspecified"))
      (node (ref "D2") (pin "2") (pinfunction "A_2") (pintype "unspecified"))
      (node (ref "D20") (pin "2") (pinfunction "A_2") (pintype "unspecified"))
      (node (ref "D6") (pin "2") (pinfunction "A_2") (pintype "unspecified"))
      (node (ref "D7") (pin "2") (pinfunction "A_2") (pintype "unspecified"))
      (node (ref "D8") (pin "2") (pinfunction "A_2") (pintype "unspecified"))
      (node (ref "D9") (pin "2") (pinfunction "A_2") (pintype "unspecified"))
      (node (ref "J1") (pin "1") (pinfunction "1_1") (pintype "unspecified"))
      (node (ref "J10") (pin "1") (pinfunction "1_1") (pintype "unspecified"))
      (node (ref "J11") (pin "1") (pinfunction "1_1") (pintype "unspecified"))
      (node (ref "J12") (pin "1") (pinfunction "1_1") (pintype "unspecified"))
      (node (ref "J13") (pin "1") (pinfunction "1_1") (pintype "unspecified"))
      (node (ref "J14") (pin "1") (pinfunction "1_1") (pintype "unspecified"))
      (node (ref "J15") (pin "1") (pinfunction "1_1") (pintype "unspecified"))
      (node (ref "J16") (pin "1") (pinfunction "1_1") (pintype "unspecified"))
      (node (ref "J2") (pin "1") (pinfunction "1_1") (pintype "unspecified"))
      (node (ref "J3") (pin "1") (pinfunction "1_1") (pintype "unspecified"))
      (node (ref "J4") (pin "1") (pinfunction "1_1") (pintype "unspecified"))
      (node (ref "J5") (pin "1") (pinfunction "1_1") (pintype "unspecified"))
      (node (ref "J6") (pin "1") (pinfunction "1_1") (pintype "unspecified"))
      (node (ref "J7") (pin "1") (pinfunction "1_1") (pintype "unspecified"))
      (node (ref "J8") (pin "1") (pinfunction "1_1") (pintype "unspecified"))
      (node (ref "J9") (pin "1") (pinfunction "1_1") (pintype "unspecified"))
      (node (ref "R5") (pin "2") (pinfunction "2_2") (pintype "input"))
      (node (ref "R6") (pin "2") (pinfunction "2_2") (pintype "input"))
      (node (ref "U10") (pin "1") (pinfunction "1_1") (pintype "unspecified"))
      (node (ref "U11") (pin "1") (pinfunction "1_1") (pintype "unspecified"))
      (node (ref "U12") (pin "1") (pinfunction "1_1") (pintype "unspecified"))
      (node (ref "U13") (pin "1") (pinfunction "1_1") (pintype "unspecified"))
      (node (ref "U5") (pin "1") (pinfunction "1_1") (pintype "unspecified"))
      (node (ref "U6") (pin "1") (pinfunction "1_1") (pintype "unspecified"))
      (node (ref "U7") (pin "1") (pinfunction "1_1") (pintype "unspecified"))
      (node (ref "U8") (pin "1") (pinfunction "1_1") (pintype "unspecified"))
      (node (ref "U9") (pin "1") (pinfunction "1_1") (pintype "unspecified"))
    )
    (net (code "18") (name "Filtered_moisture") (class "Default")
      (node (ref "J25") (pin "1") (pinfunction "1_1") (pintype "unspecified"))
      (node (ref "R115") (pin "2") (pinfunction "2_2") (pintype "input"))
      (node (ref "R117") (pin "1") (pinfunction "1_1") (pintype "input"))
    )
    (net (code "19") (name "Flash_Fast_B_H") (class "Default")
      (node (ref "U69") (pin "D4") (pinfunction "D4_D4") (pintype "unspecified"))
    )
    (net (code "20") (name "GND") (class "Default")
      (node (ref "C1") (pin "2") (pinfunction "2_2") (pintype "input"))
      (node (ref "C10") (pin "1") (pinfunction "1_1") (pintype "unspecified"))
      (node (ref "C11") (pin "2") (pinfunction "2_2") (pintype "input"))
      (node (ref "C12") (pin "1") (pinfunction "1_1") (pintype "unspecified"))
      (node (ref "C13") (pin "1") (pinfunction "1_1") (pintype "unspecified"))
      (node (ref "C14") (pin "2") (pinfunction "2_2") (pintype "input"))
      (node (ref "C15") (pin "1") (pinfunction "1_1") (pintype "unspecified"))
      (node (ref "C16") (pin "1") (pinfunction "1_1") (pintype "unspecified"))
      (node (ref "C17") (pin "2") (pinfunction "2_2") (pintype "input"))
      (node (ref "C18") (pin "1") (pinfunction "1_1") (pintype "unspecified"))
      (node (ref "C19") (pin "1") (pinfunction "1_1") (pintype "unspecified"))
      (node (ref "C2") (pin "1") (pinfunction "1_1") (pintype "unspecified"))
      (node (ref "C20") (pin "2") (pinfunction "2_2") (pintype "input"))
      (node (ref "C21") (pin "1") (pinfunction "1_1") (pintype "unspecified"))
      (node (ref "C22") (pin "1") (pinfunction "1_1") (pintype "unspecified"))
      (node (ref "C23") (pin "2") (pinfunction "2_2") (pintype "input"))
      (node (ref "C24") (pin "1") (pinfunction "1_1") (pintype "unspecified"))
      (node (ref "C25") (pin "1") (pinfunction "1_1") (pintype "unspecified"))
      (node (ref "C26") (pin "2") (pinfunction "2_2") (pintype "input"))
      (node (ref "C27") (pin "1") (pinfunction "1_1") (pintype "unspecified"))
      (node (ref "C28") (pin "1") (pinfunction "1_1") (pintype "unspecified"))
      (node (ref "C29") (pin "2") (pinfunction "2_2") (pintype "input"))
      (node (ref "C3") (pin "1") (pinfunction "1_1") (pintype "unspecified"))
      (node (ref "C30") (pin "1") (pinfunction "1_1") (pintype "unspecified"))
      (node (ref "C31") (pin "1") (pinfunction "1_1") (pintype "unspecified"))
      (node (ref "C32") (pin "2") (pinfunction "2_2") (pintype "input"))
      (node (ref "C33") (pin "1") (pinfunction "1_1") (pintype "unspecified"))
      (node (ref "C34") (pin "1") (pinfunction "1_1") (pintype "unspecified"))
      (node (ref "C35") (pin "2") (pinfunction "2_2") (pintype "input"))
      (node (ref "C36") (pin "1") (pinfunction "1_1") (pintype "unspecified"))
      (node (ref "C37") (pin "1") (pinfunction "1_1") (pintype "unspecified"))
      (node (ref "C38") (pin "2") (pinfunction "2_2") (pintype "input"))
      (node (ref "C39") (pin "1") (pinfunction "1_1") (pintype "unspecified"))
      (node (ref "C4") (pin "2") (pinfunction "2_2") (pintype "input"))
      (node (ref "C40") (pin "1") (pinfunction "1_1") (pintype "unspecified"))
      (node (ref "C41") (pin "2") (pinfunction "2_2") (pintype "input"))
      (node (ref "C42") (pin "1") (pinfunction "1_1") (pintype "unspecified"))
      (node (ref "C43") (pin "1") (pinfunction "1_1") (pintype "unspecified"))
      (node (ref "C44") (pin "2") (pinfunction "2_2") (pintype "input"))
      (node (ref "C45") (pin "1") (pinfunction "1_1") (pintype "unspecified"))
      (node (ref "C46") (pin "1") (pinfunction "1_1") (pintype "unspecified"))
      (node (ref "C47") (pin "2") (pinfunction "2_2") (pintype "input"))
      (node (ref "C48") (pin "1") (pinfunction "1_1") (pintype "unspecified"))
      (node (ref "C49") (pin "1") (pinfunction "1_1") (pintype "unspecified"))
      (node (ref "C5") (pin "1") (pinfunction "1_1") (pintype "unspecified"))
      (node (ref "C50") (pin "1") (pinfunction "1_1") (pintype "unspecified"))
      (node (ref "C51") (pin "1") (pinfunction "1_1") (pintype "unspecified"))
      (node (ref "C52") (pin "1") (pinfunction "1_1") (pintype "unspecified"))
      (node (ref "C53") (pin "1") (pinfunction "1_1") (pintype "unspecified"))
      (node (ref "C54") (pin "2") (pinfunction "2_2") (pintype "input"))
      (node (ref "C55") (pin "2") (pinfunction "2_2") (pintype "input"))
      (node (ref "C56") (pin "1") (pinfunction "1_1") (pintype "unspecified"))
      (node (ref "C57") (pin "2") (pinfunction "2_2") (pintype "input"))
      (node (ref "C58") (pin "2") (pinfunction "2_2") (pintype "input"))
      (node (ref "C59") (pin "1") (pinfunction "1_1") (pintype "unspecified"))
      (node (ref "C6") (pin "1") (pinfunction "1_1") (pintype "unspecified"))
      (node (ref "C60") (pin "2") (pinfunction "2_2") (pintype "unspecified"))
      (node (ref "C61") (pin "1") (pinfunction "1_1") (pintype "unspecified"))
      (node (ref "C62") (pin "1") (pinfunction "1_1") (pintype "unspecified"))
      (node (ref "C63") (pin "1") (pinfunction "1_1") (pintype "unspecified"))
      (node (ref "C64") (pin "1") (pinfunction "1_1") (pintype "unspecified"))
      (node (ref "C65") (pin "1") (pinfunction "1_1") (pintype "unspecified"))
      (node (ref "C66") (pin "1") (pinfunction "1_1") (pintype "unspecified"))
      (node (ref "C67") (pin "1") (pinfunction "1_1") (pintype "unspecified"))
      (node (ref "C68") (pin "1") (pinfunction "1_1") (pintype "unspecified"))
      (node (ref "C69") (pin "1") (pinfunction "1_1") (pintype "unspecified"))
      (node (ref "C7") (pin "2") (pinfunction "2_2") (pintype "input"))
      (node (ref "C70") (pin "1") (pinfunction "1_1") (pintype "unspecified"))
      (node (ref "C71") (pin "1") (pinfunction "1_1") (pintype "unspecified"))
      (node (ref "C72") (pin "1") (pinfunction "1_1") (pintype "unspecified"))
      (node (ref "C73") (pin "1") (pinfunction "1_1") (pintype "unspecified"))
      (node (ref "C74") (pin "1") (pinfunction "1_1") (pintype "unspecified"))
      (node (ref "C8") (pin "1") (pinfunction "1_1") (pintype "unspecified"))
      (node (ref "C9") (pin "1") (pinfunction "1_1") (pintype "unspecified"))
      (node (ref "CN1") (pin "2") (pinfunction "2_2") (pintype "unspecified"))
      (node (ref "CN1") (pin "6") (pinfunction "6_6") (pintype "unspecified"))
      (node (ref "CN1") (pin "7") (pinfunction "7_7") (pintype "unspecified"))
      (node (ref "CN10") (pin "2") (pinfunction "2_2") (pintype "unspecified"))
      (node (ref "CN10") (pin "6") (pinfunction "6_6") (pintype "unspecified"))
      (node (ref "CN10") (pin "7") (pinfunction "7_7") (pintype "unspecified"))
      (node (ref "CN11") (pin "2") (pinfunction "2_2") (pintype "unspecified"))
      (node (ref "CN11") (pin "5") (pinfunction "5_5") (pintype "unspecified"))
      (node (ref "CN11") (pin "6") (pinfunction "6_6") (pintype "unspecified"))
      (node (ref "CN11") (pin "7") (pinfunction "7_7") (pintype "unspecified"))
      (node (ref "CN12") (pin "2") (pinfunction "2_2") (pintype "unspecified"))
      (node (ref "CN12") (pin "5") (pinfunction "5_5") (pintype "unspecified"))
      (node (ref "CN12") (pin "6") (pinfunction "6_6") (pintype "unspecified"))
      (node (ref "CN12") (pin "7") (pinfunction "7_7") (pintype "unspecified"))
      (node (ref "CN13") (pin "2") (pinfunction "2_2") (pintype "unspecified"))
      (node (ref "CN13") (pin "5") (pinfunction "5_5") (pintype "unspecified"))
      (node (ref "CN13") (pin "6") (pinfunction "6_6") (pintype "unspecified"))
      (node (ref "CN13") (pin "7") (pinfunction "7_7") (pintype "unspecified"))
      (node (ref "CN14") (pin "2") (pinfunction "2_2") (pintype "unspecified"))
      (node (ref "CN14") (pin "5") (pinfunction "5_5") (pintype "unspecified"))
      (node (ref "CN14") (pin "6") (pinfunction "6_6") (pintype "unspecified"))
      (node (ref "CN14") (pin "7") (pinfunction "7_7") (pintype "unspecified"))
      (node (ref "CN15") (pin "2") (pinfunction "2_2") (pintype "unspecified"))
      (node (ref "CN15") (pin "5") (pinfunction "5_5") (pintype "unspecified"))
      (node (ref "CN15") (pin "6") (pinfunction "6_6") (pintype "unspecified"))
      (node (ref "CN15") (pin "7") (pinfunction "7_7") (pintype "unspecified"))
      (node (ref "CN16") (pin "2") (pinfunction "2_2") (pintype "unspecified"))
      (node (ref "CN16") (pin "5") (pinfunction "5_5") (pintype "unspecified"))
      (node (ref "CN16") (pin "6") (pinfunction "6_6") (pintype "unspecified"))
      (node (ref "CN16") (pin "7") (pinfunction "7_7") (pintype "unspecified"))
      (node (ref "CN17") (pin "2") (pinfunction "2_2") (pintype "unspecified"))
      (node (ref "CN17") (pin "5") (pinfunction "5_5") (pintype "unspecified"))
      (node (ref "CN17") (pin "6") (pinfunction "6_6") (pintype "unspecified"))
      (node (ref "CN17") (pin "7") (pinfunction "7_7") (pintype "unspecified"))
      (node (ref "CN18") (pin "2") (pinfunction "2_2") (pintype "unspecified"))
      (node (ref "CN18") (pin "5") (pinfunction "5_5") (pintype "unspecified"))
      (node (ref "CN18") (pin "6") (pinfunction "6_6") (pintype "unspecified"))
      (node (ref "CN18") (pin "7") (pinfunction "7_7") (pintype "unspecified"))
      (node (ref "CN2") (pin "2") (pinfunction "2_2") (pintype "unspecified"))
      (node (ref "CN2") (pin "6") (pinfunction "6_6") (pintype "unspecified"))
      (node (ref "CN2") (pin "7") (pinfunction "7_7") (pintype "unspecified"))
      (node (ref "CN3") (pin "2") (pinfunction "2_2") (pintype "unspecified"))
      (node (ref "CN3") (pin "6") (pinfunction "6_6") (pintype "unspecified"))
      (node (ref "CN3") (pin "7") (pinfunction "7_7") (pintype "unspecified"))
      (node (ref "CN4") (pin "2") (pinfunction "2_2") (pintype "unspecified"))
      (node (ref "CN4") (pin "6") (pinfunction "6_6") (pintype "unspecified"))
      (node (ref "CN4") (pin "7") (pinfunction "7_7") (pintype "unspecified"))
      (node (ref "CN5") (pin "2") (pinfunction "2_2") (pintype "unspecified"))
      (node (ref "CN5") (pin "6") (pinfunction "6_6") (pintype "unspecified"))
      (node (ref "CN5") (pin "7") (pinfunction "7_7") (pintype "unspecified"))
      (node (ref "CN6") (pin "2") (pinfunction "2_2") (pintype "unspecified"))
      (node (ref "CN6") (pin "6") (pinfunction "6_6") (pintype "unspecified"))
      (node (ref "CN6") (pin "7") (pinfunction "7_7") (pintype "unspecified"))
      (node (ref "CN7") (pin "2") (pinfunction "2_2") (pintype "unspecified"))
      (node (ref "CN7") (pin "6") (pinfunction "6_6") (pintype "unspecified"))
      (node (ref "CN7") (pin "7") (pinfunction "7_7") (pintype "unspecified"))
      (node (ref "CN8") (pin "2") (pinfunction "2_2") (pintype "unspecified"))
      (node (ref "CN8") (pin "6") (pinfunction "6_6") (pintype "unspecified"))
      (node (ref "CN8") (pin "7") (pinfunction "7_7") (pintype "unspecified"))
      (node (ref "CN9") (pin "2") (pinfunction "2_2") (pintype "unspecified"))
      (node (ref "CN9") (pin "6") (pinfunction "6_6") (pintype "unspecified"))
      (node (ref "CN9") (pin "7") (pinfunction "7_7") (pintype "unspecified"))
      (node (ref "H1") (pin "2") (pinfunction "2_2") (pintype "unspecified"))
      (node (ref "J1") (pin "S1") (pinfunction "SHIELD_S1") (pintype "unspecified"))
      (node (ref "J1") (pin "S2") (pinfunction "SHIELD_S2") (pintype "unspecified"))
      (node (ref "J10") (pin "S1") (pinfunction "SHIELD_S1") (pintype "unspecified"))
      (node (ref "J10") (pin "S2") (pinfunction "SHIELD_S2") (pintype "unspecified"))
      (node (ref "J11") (pin "S1") (pinfunction "SHIELD_S1") (pintype "unspecified"))
      (node (ref "J11") (pin "S2") (pinfunction "SHIELD_S2") (pintype "unspecified"))
      (node (ref "J12") (pin "S1") (pinfunction "SHIELD_S1") (pintype "unspecified"))
      (node (ref "J12") (pin "S2") (pinfunction "SHIELD_S2") (pintype "unspecified"))
      (node (ref "J13") (pin "S1") (pinfunction "SHIELD_S1") (pintype "unspecified"))
      (node (ref "J13") (pin "S2") (pinfunction "SHIELD_S2") (pintype "unspecified"))
      (node (ref "J14") (pin "S1") (pinfunction "SHIELD_S1") (pintype "unspecified"))
      (node (ref "J14") (pin "S2") (pinfunction "SHIELD_S2") (pintype "unspecified"))
      (node (ref "J15") (pin "S1") (pinfunction "SHIELD_S1") (pintype "unspecified"))
      (node (ref "J15") (pin "S2") (pinfunction "SHIELD_S2") (pintype "unspecified"))
      (node (ref "J16") (pin "S1") (pinfunction "SHIELD_S1") (pintype "unspecified"))
      (node (ref "J16") (pin "S2") (pinfunction "SHIELD_S2") (pintype "unspecified"))
      (node (ref "J2") (pin "S1") (pinfunction "SHIELD_S1") (pintype "unspecified"))
      (node (ref "J2") (pin "S2") (pinfunction "SHIELD_S2") (pintype "unspecified"))
      (node (ref "J25") (pin "2") (pinfunction "2_2") (pintype "unspecified"))
      (node (ref "J25") (pin "S1") (pinfunction "SHIELD_S1") (pintype "unspecified"))
      (node (ref "J25") (pin "S2") (pinfunction "SHIELD_S2") (pintype "unspecified"))
      (node (ref "J3") (pin "S1") (pinfunction "SHIELD_S1") (pintype "unspecified"))
      (node (ref "J3") (pin "S2") (pinfunction "SHIELD_S2") (pintype "unspecified"))
      (node (ref "J4") (pin "S1") (pinfunction "SHIELD_S1") (pintype "unspecified"))
      (node (ref "J4") (pin "S2") (pinfunction "SHIELD_S2") (pintype "unspecified"))
      (node (ref "J5") (pin "S1") (pinfunction "SHIELD_S1") (pintype "unspecified"))
      (node (ref "J5") (pin "S2") (pinfunction "SHIELD_S2") (pintype "unspecified"))
      (node (ref "J6") (pin "S1") (pinfunction "SHIELD_S1") (pintype "unspecified"))
      (node (ref "J6") (pin "S2") (pinfunction "SHIELD_S2") (pintype "unspecified"))
      (node (ref "J7") (pin "S1") (pinfunction "SHIELD_S1") (pintype "unspecified"))
      (node (ref "J7") (pin "S2") (pinfunction "SHIELD_S2") (pintype "unspecified"))
      (node (ref "J8") (pin "S1") (pinfunction "SHIELD_S1") (pintype "unspecified"))
      (node (ref "J8") (pin "S2") (pinfunction "SHIELD_S2") (pintype "unspecified"))
      (node (ref "J9") (pin "S1") (pinfunction "SHIELD_S1") (pintype "unspecified"))
      (node (ref "J9") (pin "S2") (pinfunction "SHIELD_S2") (pintype "unspecified"))
      (node (ref "LED1") (pin "1") (pinfunction "K_1") (pintype "unspecified"))
      (node (ref "LED2") (pin "1") (pinfunction "K_1") (pintype "unspecified"))
      (node (ref "LED3") (pin "1") (pinfunction "K_1") (pintype "unspecified"))
      (node (ref "LED4") (pin "1") (pinfunction "K_1") (pintype "unspecified"))
      (node (ref "LED5") (pin "1") (pinfunction "K_1") (pintype "unspecified"))
      (node (ref "LED6") (pin "1") (pinfunction "K_1") (pintype "unspecified"))
      (node (ref "LED7") (pin "1") (pinfunction "K_1") (pintype "unspecified"))
      (node (ref "Q10") (pin "2") (pinfunction "S_2") (pintype "unspecified"))
      (node (ref "Q11") (pin "2") (pinfunction "S_2") (pintype "unspecified"))
      (node (ref "Q3") (pin "2") (pinfunction "S_2") (pintype "unspecified"))
      (node (ref "Q4") (pin "2") (pinfunction "S_2") (pintype "unspecified"))
      (node (ref "Q5") (pin "2") (pinfunction "S_2") (pintype "unspecified"))
      (node (ref "Q6") (pin "2") (pinfunction "S_2") (pintype "unspecified"))
      (node (ref "Q8") (pin "2") (pinfunction "S_2") (pintype "unspecified"))
      (node (ref "Q9") (pin "2") (pinfunction "S_2") (pintype "unspecified"))
      (node (ref "R1") (pin "1") (pinfunction "1_1") (pintype "input"))
      (node (ref "R10") (pin "1") (pinfunction "1_1") (pintype "input"))
      (node (ref "R100") (pin "1") (pinfunction "1_1") (pintype "input"))
      (node (ref "R103") (pin "2") (pinfunction "2_2") (pintype "input"))
      (node (ref "R104") (pin "1") (pinfunction "1_1") (pintype "input"))
      (node (ref "R108") (pin "2") (pinfunction "2_2") (pintype "input"))
      (node (ref "R109") (pin "2") (pinfunction "2_2") (pintype "input"))
      (node (ref "R11") (pin "1") (pinfunction "1_1") (pintype "input"))
      (node (ref "R112") (pin "2") (pinfunction "2_2") (pintype "input"))
      (node (ref "R118") (pin "2") (pinfunction "2_2") (pintype "input"))
      (node (ref "R119") (pin "2") (pinfunction "2_2") (pintype "input"))
      (node (ref "R12") (pin "1") (pinfunction "1_1") (pintype "input"))
      (node (ref "R120") (pin "1") (pinfunction "1_1") (pintype "input"))
      (node (ref "R121") (pin "1") (pinfunction "1_1") (pintype "input"))
      (node (ref "R122") (pin "1") (pinfunction "1_1") (pintype "input"))
      (node (ref "R13") (pin "1") (pinfunction "1_1") (pintype "input"))
      (node (ref "R14") (pin "1") (pinfunction "1_1") (pintype "input"))
      (node (ref "R15") (pin "1") (pinfunction "1_1") (pintype "input"))
      (node (ref "R16") (pin "1") (pinfunction "1_1") (pintype "input"))
      (node (ref "R17") (pin "1") (pinfunction "1_1") (pintype "input"))
      (node (ref "R18") (pin "1") (pinfunction "1_1") (pintype "input"))
      (node (ref "R2") (pin "1") (pinfunction "1_1") (pintype "input"))
      (node (ref "R24") (pin "1") (pinfunction "1_1") (pintype "input"))
      (node (ref "R25") (pin "1") (pinfunction "1_1") (pintype "input"))
      (node (ref "R27") (pin "1") (pinfunction "1_1") (pintype "input"))
      (node (ref "R28") (pin "1") (pinfunction "1_1") (pintype "input"))
      (node (ref "R3") (pin "1") (pinfunction "1_1") (pintype "input"))
      (node (ref "R30") (pin "1") (pinfunction "1_1") (pintype "input"))
      (node (ref "R32") (pin "1") (pinfunction "1_1") (pintype "input"))
      (node (ref "R35") (pin "1") (pinfunction "1_1") (pintype "input"))
      (node (ref "R38") (pin "1") (pinfunction "1_1") (pintype "input"))
      (node (ref "R4") (pin "1") (pinfunction "1_1") (pintype "input"))
      (node (ref "R41") (pin "1") (pinfunction "1_1") (pintype "input"))
      (node (ref "R42") (pin "1") (pinfunction "1_1") (pintype "input"))
      (node (ref "R45") (pin "1") (pinfunction "1_1") (pintype "input"))
      (node (ref "R46") (pin "1") (pinfunction "1_1") (pintype "input"))
      (node (ref "R49") (pin "1") (pinfunction "1_1") (pintype "input"))
      (node (ref "R7") (pin "1") (pinfunction "1_1") (pintype "input"))
      (node (ref "R8") (pin "1") (pinfunction "1_1") (pintype "input"))
      (node (ref "R9") (pin "1") (pinfunction "1_1") (pintype "input"))
      (node (ref "U1") (pin "11") (pinfunction "PAD_11") (pintype "unspecified"))
      (node (ref "U1") (pin "8") (pinfunction "GND_8") (pintype "unspecified"))
      (node (ref "U10") (pin "2") (pinfunction "2_2") (pintype "unspecified"))
      (node (ref "U11") (pin "2") (pinfunction "2_2") (pintype "unspecified"))
      (node (ref "U12") (pin "2") (pinfunction "2_2") (pintype "unspecified"))
      (node (ref "U13") (pin "2") (pinfunction "2_2") (pintype "unspecified"))
      (node (ref "U14") (pin "11") (pinfunction "PAD_11") (pintype "unspecified"))
      (node (ref "U14") (pin "8") (pinfunction "GND_8") (pintype "unspecified"))
      (node (ref "U15") (pin "11") (pinfunction "PAD_11") (pintype "unspecified"))
      (node (ref "U15") (pin "8") (pinfunction "GND_8") (pintype "unspecified"))
      (node (ref "U16") (pin "11") (pinfunction "PAD_11") (pintype "unspecified"))
      (node (ref "U16") (pin "8") (pinfunction "GND_8") (pintype "unspecified"))
      (node (ref "U17") (pin "11") (pinfunction "PAD_11") (pintype "unspecified"))
      (node (ref "U17") (pin "8") (pinfunction "GND_8") (pintype "unspecified"))
      (node (ref "U18") (pin "11") (pinfunction "PAD_11") (pintype "unspecified"))
      (node (ref "U18") (pin "8") (pinfunction "GND_8") (pintype "unspecified"))
      (node (ref "U19") (pin "11") (pinfunction "PAD_11") (pintype "unspecified"))
      (node (ref "U19") (pin "8") (pinfunction "GND_8") (pintype "unspecified"))
      (node (ref "U2") (pin "11") (pinfunction "PAD_11") (pintype "unspecified"))
      (node (ref "U2") (pin "8") (pinfunction "GND_8") (pintype "unspecified"))
      (node (ref "U20") (pin "11") (pinfunction "PAD_11") (pintype "unspecified"))
      (node (ref "U20") (pin "8") (pinfunction "GND_8") (pintype "unspecified"))
      (node (ref "U21") (pin "11") (pinfunction "PAD_11") (pintype "unspecified"))
      (node (ref "U21") (pin "8") (pinfunction "GND_8") (pintype "unspecified"))
      (node (ref "U22") (pin "11") (pinfunction "PAD_11") (pintype "unspecified"))
      (node (ref "U22") (pin "8") (pinfunction "GND_8") (pintype "unspecified"))
      (node (ref "U23") (pin "11") (pinfunction "PAD_11") (pintype "unspecified"))
      (node (ref "U23") (pin "8") (pinfunction "GND_8") (pintype "unspecified"))
      (node (ref "U24") (pin "11") (pinfunction "PAD_11") (pintype "unspecified"))
      (node (ref "U24") (pin "8") (pinfunction "GND_8") (pintype "unspecified"))
      (node (ref "U25") (pin "11") (pinfunction "PAD_11") (pintype "unspecified"))
      (node (ref "U25") (pin "8") (pinfunction "GND_8") (pintype "unspecified"))
      (node (ref "U26") (pin "10") (pinfunction "PGND_10") (pintype "unspecified"))
      (node (ref "U26") (pin "15") (pinfunction "PGND_15") (pintype "unspecified"))
      (node (ref "U26") (pin "16") (pinfunction "PGND_16") (pintype "unspecified"))
      (node (ref "U26") (pin "17") (pinfunction "Sync_17") (pintype "unspecified"))
      (node (ref "U26") (pin "9") (pinfunction "AGND_9") (pintype "unspecified"))
      (node (ref "U27") (pin "3") (pinfunction "-Vin_3") (pintype "passive"))
      (node (ref "U27") (pin "4") (pinfunction "-Vout_4") (pintype "passive"))
      (node (ref "U27") (pin "5") (pinfunction "-Sense_5") (pintype "passive"))
      (node (ref "U29") (pin "2") (pinfunction "PV+_2") (pintype "unspecified"))
      (node (ref "U3") (pin "11") (pinfunction "PAD_11") (pintype "unspecified"))
      (node (ref "U3") (pin "8") (pinfunction "GND_8") (pintype "unspecified"))
      (node (ref "U30") (pin "1") (pinfunction "PV-_1") (pintype "unspecified"))
      (node (ref "U31") (pin "2") (pinfunction "2_2") (pintype "unspecified"))
      (node (ref "U33") (pin "1") (pinfunction "PV-_1") (pintype "unspecified"))
      (node (ref "U35") (pin "1") (pinfunction "PV-_1") (pintype "unspecified"))
      (node (ref "U36") (pin "1") (pinfunction "PV-_1") (pintype "unspecified"))
      (node (ref "U38") (pin "1") (pinfunction "PV-_1") (pintype "unspecified"))
      (node (ref "U4") (pin "11") (pinfunction "PAD_11") (pintype "unspecified"))
      (node (ref "U4") (pin "8") (pinfunction "GND_8") (pintype "unspecified"))
      (node (ref "U41") (pin "1") (pinfunction "PV-_1") (pintype "unspecified"))
      (node (ref "U42") (pin "1") (pinfunction "PV-_1") (pintype "unspecified"))
      (node (ref "U45") (pin "1") (pinfunction "PV-_1") (pintype "unspecified"))
      (node (ref "U46") (pin "2") (pinfunction "VSS_2") (pintype "unspecified"))
      (node (ref "U47") (pin "1") (pinfunction "OE1#_1") (pintype "unspecified"))
      (node (ref "U47") (pin "10") (pinfunction "GND_10") (pintype "unspecified"))
      (node (ref "U47") (pin "19") (pinfunction "OE2#_19") (pintype "unspecified"))
      (node (ref "U48") (pin "2") (pinfunction "GND_2") (pintype "unspecified"))
      (node (ref "U49") (pin "1") (pinfunction "OE1#_1") (pintype "unspecified"))
      (node (ref "U49") (pin "10") (pinfunction "GND_10") (pintype "unspecified"))
      (node (ref "U49") (pin "19") (pinfunction "OE2#_19") (pintype "unspecified"))
      (node (ref "U5") (pin "2") (pinfunction "2_2") (pintype "unspecified"))
      (node (ref "U50") (pin "1") (pinfunction "A0_1") (pintype "unspecified"))
      (node (ref "U50") (pin "2") (pinfunction "A1_2") (pintype "unspecified"))
      (node (ref "U50") (pin "8") (pinfunction "GND_8") (pintype "unspecified"))
      (node (ref "U51") (pin "2") (pinfunction "A1_2") (pintype "unspecified"))
      (node (ref "U51") (pin "8") (pinfunction "GND_8") (pintype "unspecified"))
      (node (ref "U52") (pin "1") (pinfunction "A0_1") (pintype "unspecified"))
      (node (ref "U52") (pin "8") (pinfunction "GND_8") (pintype "unspecified"))
      (node (ref "U53") (pin "8") (pinfunction "GND_8") (pintype "unspecified"))
      (node (ref "U54") (pin "1") (pinfunction "nSS_1") (pintype "unspecified"))
      (node (ref "U54") (pin "8") (pinfunction "Gnd_8") (pintype "unspecified"))
      (node (ref "U55") (pin "4") (pinfunction "GND_4") (pintype "unspecified"))
      (node (ref "U55") (pin "5") (pinfunction "A2/T1_5") (pintype "unspecified"))
      (node (ref "U55") (pin "6") (pinfunction "A1_6") (pintype "unspecified"))
      (node (ref "U55") (pin "7") (pinfunction "A0_7") (pintype "unspecified"))
      (node (ref "U56") (pin "1") (pinfunction "nSS_1") (pintype "unspecified"))
      (node (ref "U56") (pin "8") (pinfunction "Gnd_8") (pintype "unspecified"))
      (node (ref "U57") (pin "1") (pinfunction "nSS_1") (pintype "unspecified"))
      (node (ref "U57") (pin "8") (pinfunction "Gnd_8") (pintype "unspecified"))
      (node (ref "U58") (pin "2") (pinfunction "GND_2") (pintype "unspecified"))
      (node (ref "U58") (pin "3") (pinfunction "2A_3") (pintype "unspecified"))
      (node (ref "U59") (pin "2") (pinfunction "GND_2") (pintype "unspecified"))
      (node (ref "U6") (pin "2") (pinfunction "2_2") (pintype "unspecified"))
      (node (ref "U60") (pin "2") (pinfunction "GND_2") (pintype "unspecified"))
      (node (ref "U63") (pin "2") (pinfunction "GND_2") (pintype "unspecified"))
      (node (ref "U64") (pin "3") (pinfunction "S_3") (pintype "unspecified"))
      (node (ref "U65") (pin "3") (pinfunction "S_3") (pintype "unspecified"))
      (node (ref "U66") (pin "2") (pinfunction "GND_2") (pintype "unspecified"))
      (node (ref "U66") (pin "3") (pinfunction "2A_3") (pintype "unspecified"))
      (node (ref "U67") (pin "2") (pinfunction "GND_2") (pintype "unspecified"))
      (node (ref "U68") (pin "1") (pinfunction "A0_1") (pintype "unspecified"))
      (node (ref "U68") (pin "2") (pinfunction "A1_2") (pintype "unspecified"))
      (node (ref "U68") (pin "4") (pinfunction "DGND_4") (pintype "unspecified"))
      (node (ref "U68") (pin "5") (pinfunction "AVSS_5") (pintype "unspecified"))
      (node (ref "U69") (pin "GND") (pinfunction "GND_GND") (pintype "unspecified"))
      (node (ref "U69") (pin "GND2") (pinfunction "GND2_GND2") (pintype "unspecified"))
      (node (ref "U69") (pin "GND3") (pinfunction "GND3_GND3") (pintype "unspecified"))
      (node (ref "U7") (pin "2") (pinfunction "2_2") (pintype "unspecified"))
      (node (ref "U70") (pin "2") (pinfunction "GND_2") (pintype "unspecified"))
      (node (ref "U70") (pin "5") (pinfunction "GND_5") (pintype "unspecified"))
      (node (ref "U71") (pin "2") (pinfunction "2_2") (pintype "unspecified"))
      (node (ref "U76") (pin "3") (pinfunction "S_3") (pintype "unspecified"))
      (node (ref "U8") (pin "2") (pinfunction "2_2") (pintype "unspecified"))
      (node (ref "U9") (pin "2") (pinfunction "2_2") (pintype "unspecified"))
    )
    (net (code "21") (name "Heater_H") (class "Default")
      (node (ref "U64") (pin "1") (pinfunction "G_1") (pintype "unspecified"))
      (node (ref "U69") (pin "A0") (pinfunction "A0_A0") (pintype "unspecified"))
    )
    (net (code "22") (name "IMU0_reset_L") (class "Default")
      (node (ref "CN4") (pin "5") (pinfunction "5_5") (pintype "unspecified"))
      (node (ref "R53") (pin "2") (pinfunction "2_2") (pintype "input"))
    )
    (net (code "23") (name "IMU1_reset_L") (class "Default")
      (node (ref "CN3") (pin "5") (pinfunction "5_5") (pintype "unspecified"))
      (node (ref "R55") (pin "2") (pinfunction "2_2") (pintype "input"))
    )
    (net (code "24") (name "IMU2_reset_L") (class "Default")
      (node (ref "CN2") (pin "5") (pinfunction "5_5") (pintype "unspecified"))
      (node (ref "R57") (pin "2") (pinfunction "2_2") (pintype "input"))
    )
    (net (code "25") (name "IMU3_reset_L") (class "Default")
      (node (ref "CN1") (pin "5") (pinfunction "5_5") (pintype "unspecified"))
      (node (ref "R59") (pin "2") (pinfunction "2_2") (pintype "input"))
    )
    (net (code "26") (name "IMU4_reset_L") (class "Default")
      (node (ref "CN7") (pin "5") (pinfunction "5_5") (pintype "unspecified"))
      (node (ref "R62") (pin "2") (pinfunction "2_2") (pintype "input"))
    )
    (net (code "27") (name "IMU5_reset_L") (class "Default")
      (node (ref "CN5") (pin "5") (pinfunction "5_5") (pintype "unspecified"))
      (node (ref "R64") (pin "2") (pinfunction "2_2") (pintype "input"))
    )
    (net (code "28") (name "IMU6_reset_L") (class "Default")
      (node (ref "CN8") (pin "5") (pinfunction "5_5") (pintype "unspecified"))
      (node (ref "R65") (pin "2") (pinfunction "2_2") (pintype "input"))
    )
    (net (code "29") (name "IMU7_reset_L") (class "Default")
      (node (ref "CN6") (pin "5") (pinfunction "5_5") (pintype "unspecified"))
      (node (ref "R67") (pin "2") (pinfunction "2_2") (pintype "input"))
    )
    (net (code "30") (name "LED_ON_H") (class "Default")
      (node (ref "U1") (pin "3") (pinfunction "EN_3") (pintype "unspecified"))
      (node (ref "U14") (pin "3") (pinfunction "EN_3") (pintype "unspecified"))
      (node (ref "U15") (pin "3") (pinfunction "EN_3") (pintype "unspecified"))
      (node (ref "U16") (pin "3") (pinfunction "EN_3") (pintype "unspecified"))
      (node (ref "U17") (pin "3") (pinfunction "EN_3") (pintype "unspecified"))
      (node (ref "U18") (pin "3") (pinfunction "EN_3") (pintype "unspecified"))
      (node (ref "U19") (pin "3") (pinfunction "EN_3") (pintype "unspecified"))
      (node (ref "U2") (pin "3") (pinfunction "EN_3") (pintype "unspecified"))
      (node (ref "U20") (pin "3") (pinfunction "EN_3") (pintype "unspecified"))
      (node (ref "U21") (pin "3") (pinfunction "EN_3") (pintype "unspecified"))
      (node (ref "U22") (pin "3") (pinfunction "EN_3") (pintype "unspecified"))
      (node (ref "U23") (pin "3") (pinfunction "EN_3") (pintype "unspecified"))
      (node (ref "U24") (pin "3") (pinfunction "EN_3") (pintype "unspecified"))
      (node (ref "U25") (pin "3") (pinfunction "EN_3") (pintype "unspecified"))
      (node (ref "U3") (pin "3") (pinfunction "EN_3") (pintype "unspecified"))
      (node (ref "U4") (pin "3") (pinfunction "EN_3") (pintype "unspecified"))
    )
    (net (code "31") (name "LED_on_H") (class "Default")
      (node (ref "R101") (pin "1") (pinfunction "1_1") (pintype "input"))
      (node (ref "R104") (pin "2") (pinfunction "2_2") (pintype "input"))
      (node (ref "U58") (pin "6") (pinfunction "1Y_6") (pintype "unspecified"))
      (node (ref "U66") (pin "6") (pinfunction "1Y_6") (pintype "unspecified"))
    )
    (net (code "32") (name "Local_I2C_reset_L") (class "Default")
      (node (ref "R100") (pin "2") (pinfunction "2_2") (pintype "input"))
      (node (ref "U48") (pin "1") (pinfunction "1A_1") (pintype "unspecified"))
      (node (ref "U48") (pin "3") (pinfunction "2A_3") (pintype "unspecified"))
      (node (ref "U50") (pin "3") (pinfunction "RESET#_3") (pintype "unspecified"))
      (node (ref "U51") (pin "3") (pinfunction "RESET#_3") (pintype "unspecified"))
      (node (ref "U52") (pin "3") (pinfunction "RESET#_3") (pintype "unspecified"))
      (node (ref "U53") (pin "3") (pinfunction "RESET#_3") (pintype "unspecified"))
      (node (ref "U69") (pin "D16") (pinfunction "D16_D16") (pintype "unspecified"))
    )
    (net (code "33") (name "Moisture") (class "Default")
      (node (ref "C66") (pin "2") (pinfunction "2_2") (pintype "unspecified"))
      (node (ref "R117") (pin "2") (pinfunction "2_2") (pintype "input"))
      (node (ref "U68") (pin "11") (pinfunction "AIN0_11") (pintype "unspecified"))
    )
    (net (code "34") (name "Net-(CN11-Pad4)") (class "Default")
      (node (ref "CN11") (pin "4") (pinfunction "4_4") (pintype "unspecified"))
      (node (ref "R102") (pin "2") (pinfunction "2_2") (pintype "input"))
    )
    (net (code "35") (name "Net-(CN12-Pad4)") (class "Default")
      (node (ref "CN12") (pin "4") (pinfunction "4_4") (pintype "unspecified"))
      (node (ref "R106") (pin "2") (pinfunction "2_2") (pintype "input"))
    )
    (net (code "36") (name "Net-(CN13-Pad4)") (class "Default")
      (node (ref "CN13") (pin "4") (pinfunction "4_4") (pintype "unspecified"))
      (node (ref "R116") (pin "2") (pinfunction "2_2") (pintype "input"))
    )
    (net (code "37") (name "Net-(CN14-Pad4)") (class "Default")
      (node (ref "CN14") (pin "4") (pinfunction "4_4") (pintype "unspecified"))
      (node (ref "R114") (pin "2") (pinfunction "2_2") (pintype "input"))
    )
    (net (code "38") (name "Net-(CN15-Pad4)") (class "Default")
      (node (ref "CN15") (pin "4") (pinfunction "4_4") (pintype "unspecified"))
      (node (ref "R111") (pin "2") (pinfunction "2_2") (pintype "input"))
    )
    (net (code "39") (name "Net-(CN16-Pad4)") (class "Default")
      (node (ref "CN16") (pin "4") (pinfunction "4_4") (pintype "unspecified"))
      (node (ref "R110") (pin "2") (pinfunction "2_2") (pintype "input"))
    )
    (net (code "40") (name "Net-(CN17-Pad4)") (class "Default")
      (node (ref "CN17") (pin "4") (pinfunction "4_4") (pintype "unspecified"))
      (node (ref "R105") (pin "2") (pinfunction "2_2") (pintype "input"))
    )
    (net (code "41") (name "Net-(CN18-Pad4)") (class "Default")
      (node (ref "CN18") (pin "4") (pinfunction "4_4") (pintype "unspecified"))
      (node (ref "R107") (pin "2") (pinfunction "2_2") (pintype "input"))
    )
    (net (code "42") (name "Net-(D2-C)") (class "Default")
      (node (ref "D2") (pin "1") (pinfunction "C_1") (pintype "unspecified"))
      (node (ref "U1") (pin "1") (pinfunction "VCC_1") (pintype "unspecified"))
      (node (ref "U1") (pin "2") (pinfunction "PWM_2") (pintype "unspecified"))
    )
    (net (code "43") (name "Net-(D3-A)") (class "Default")
      (node (ref "D3") (pin "2") (pinfunction "A_2") (pintype "unspecified"))
      (node (ref "U29") (pin "1") (pinfunction "PV-_1") (pintype "unspecified"))
    )
    (net (code "44") (name "Net-(D3-C)") (class "Default")
      (node (ref "D3") (pin "1") (pinfunction "C_1") (pintype "unspecified"))
      (node (ref "U73") (pin "1") (pinfunction "1_1") (pintype "bidirectional"))
    )
    (net (code "45") (name "Net-(D4-A)") (class "Default")
      (node (ref "D4") (pin "2") (pinfunction "A_2") (pintype "unspecified"))
      (node (ref "U36") (pin "2") (pinfunction "PV+_2") (pintype "unspecified"))
    )
    (net (code "46") (name "Net-(D4-C)") (class "Default")
      (node (ref "D4") (pin "1") (pinfunction "C_1") (pintype "unspecified"))
      (node (ref "U72") (pin "1") (pinfunction "1_1") (pintype "bidirectional"))
    )
    (net (code "47") (name "Net-(D5-A)") (class "Default")
      (node (ref "D5") (pin "2") (pinfunction "A_2") (pintype "unspecified"))
      (node (ref "U41") (pin "2") (pinfunction "PV+_2") (pintype "unspecified"))
    )
    (net (code "48") (name "Net-(D5-C)") (class "Default")
      (node (ref "D5") (pin "1") (pinfunction "C_1") (pintype "unspecified"))
      (node (ref "U74") (pin "1") (pinfunction "1_1") (pintype "bidirectional"))
    )
    (net (code "49") (name "Net-(D6-C)") (class "Default")
      (node (ref "D6") (pin "1") (pinfunction "C_1") (pintype "unspecified"))
      (node (ref "U2") (pin "1") (pinfunction "VCC_1") (pintype "unspecified"))
      (node (ref "U2") (pin "2") (pinfunction "PWM_2") (pintype "unspecified"))
    )
    (net (code "50") (name "Net-(D7-C)") (class "Default")
      (node (ref "D7") (pin "1") (pinfunction "C_1") (pintype "unspecified"))
      (node (ref "U3") (pin "1") (pinfunction "VCC_1") (pintype "unspecified"))
      (node (ref "U3") (pin "2") (pinfunction "PWM_2") (pintype "unspecified"))
    )
    (net (code "51") (name "Net-(D8-C)") (class "Default")
      (node (ref "D8") (pin "1") (pinfunction "C_1") (pintype "unspecified"))
      (node (ref "U4") (pin "1") (pinfunction "VCC_1") (pintype "unspecified"))
      (node (ref "U4") (pin "2") (pinfunction "PWM_2") (pintype "unspecified"))
    )
    (net (code "52") (name "Net-(D9-C)") (class "Default")
      (node (ref "D9") (pin "1") (pinfunction "C_1") (pintype "unspecified"))
      (node (ref "U14") (pin "1") (pinfunction "VCC_1") (pintype "unspecified"))
      (node (ref "U14") (pin "2") (pinfunction "PWM_2") (pintype "unspecified"))
    )
    (net (code "53") (name "Net-(D10-C)") (class "Default")
      (node (ref "D10") (pin "1") (pinfunction "C_1") (pintype "unspecified"))
      (node (ref "U15") (pin "1") (pinfunction "VCC_1") (pintype "unspecified"))
      (node (ref "U15") (pin "2") (pinfunction "PWM_2") (pintype "unspecified"))
    )
    (net (code "54") (name "Net-(D11-C)") (class "Default")
      (node (ref "D11") (pin "1") (pinfunction "C_1") (pintype "unspecified"))
      (node (ref "U16") (pin "1") (pinfunction "VCC_1") (pintype "unspecified"))
      (node (ref "U16") (pin "2") (pinfunction "PWM_2") (pintype "unspecified"))
    )
    (net (code "55") (name "Net-(D12-C)") (class "Default")
      (node (ref "D12") (pin "1") (pinfunction "C_1") (pintype "unspecified"))
      (node (ref "U17") (pin "1") (pinfunction "VCC_1") (pintype "unspecified"))
      (node (ref "U17") (pin "2") (pinfunction "PWM_2") (pintype "unspecified"))
    )
    (net (code "56") (name "Net-(D13-C)") (class "Default")
      (node (ref "D13") (pin "1") (pinfunction "C_1") (pintype "unspecified"))
      (node (ref "U18") (pin "1") (pinfunction "VCC_1") (pintype "unspecified"))
      (node (ref "U18") (pin "2") (pinfunction "PWM_2") (pintype "unspecified"))
    )
    (net (code "57") (name "Net-(D14-C)") (class "Default")
      (node (ref "D14") (pin "1") (pinfunction "C_1") (pintype "unspecified"))
      (node (ref "U19") (pin "1") (pinfunction "VCC_1") (pintype "unspecified"))
      (node (ref "U19") (pin "2") (pinfunction "PWM_2") (pintype "unspecified"))
    )
    (net (code "58") (name "Net-(D15-C)") (class "Default")
      (node (ref "D15") (pin "1") (pinfunction "C_1") (pintype "unspecified"))
      (node (ref "U20") (pin "1") (pinfunction "VCC_1") (pintype "unspecified"))
      (node (ref "U20") (pin "2") (pinfunction "PWM_2") (pintype "unspecified"))
    )
    (net (code "59") (name "Net-(D16-C)") (class "Default")
      (node (ref "D16") (pin "1") (pinfunction "C_1") (pintype "unspecified"))
      (node (ref "U21") (pin "1") (pinfunction "VCC_1") (pintype "unspecified"))
      (node (ref "U21") (pin "2") (pinfunction "PWM_2") (pintype "unspecified"))
    )
    (net (code "60") (name "Net-(D17-C)") (class "Default")
      (node (ref "D17") (pin "1") (pinfunction "C_1") (pintype "unspecified"))
      (node (ref "U22") (pin "1") (pinfunction "VCC_1") (pintype "unspecified"))
      (node (ref "U22") (pin "2") (pinfunction "PWM_2") (pintype "unspecified"))
    )
    (net (code "61") (name "Net-(D18-C)") (class "Default")
      (node (ref "D18") (pin "1") (pinfunction "C_1") (pintype "unspecified"))
      (node (ref "U23") (pin "1") (pinfunction "VCC_1") (pintype "unspecified"))
      (node (ref "U23") (pin "2") (pinfunction "PWM_2") (pintype "unspecified"))
    )
    (net (code "62") (name "Net-(D19-C)") (class "Default")
      (node (ref "D19") (pin "1") (pinfunction "C_1") (pintype "unspecified"))
      (node (ref "U24") (pin "1") (pinfunction "VCC_1") (pintype "unspecified"))
      (node (ref "U24") (pin "2") (pinfunction "PWM_2") (pintype "unspecified"))
    )
    (net (code "63") (name "Net-(D20-C)") (class "Default")
      (node (ref "D20") (pin "1") (pinfunction "C_1") (pintype "unspecified"))
      (node (ref "U25") (pin "1") (pinfunction "VCC_1") (pintype "unspecified"))
      (node (ref "U25") (pin "2") (pinfunction "PWM_2") (pintype "unspecified"))
    )
    (net (code "64") (name "Net-(LED1-A)") (class "Default")
      (node (ref "LED1") (pin "2") (pinfunction "A_2") (pintype "unspecified"))
      (node (ref "R33") (pin "1") (pinfunction "1_1") (pintype "unspecified"))
    )
    (net (code "65") (name "Net-(LED2-A)") (class "Default")
      (node (ref "LED2") (pin "2") (pinfunction "A_2") (pintype "unspecified"))
      (node (ref "R34") (pin "1") (pinfunction "1_1") (pintype "unspecified"))
    )
    (net (code "66") (name "Net-(LED3-A)") (class "Default")
      (node (ref "LED3") (pin "2") (pinfunction "A_2") (pintype "unspecified"))
      (node (ref "R36") (pin "1") (pinfunction "1_1") (pintype "unspecified"))
    )
    (net (code "67") (name "Net-(LED4-A)") (class "Default")
      (node (ref "LED4") (pin "2") (pinfunction "A_2") (pintype "unspecified"))
      (node (ref "R37") (pin "1") (pinfunction "1_1") (pintype "unspecified"))
    )
    (net (code "68") (name "Net-(LED5-A)") (class "Default")
      (node (ref "LED5") (pin "2") (pinfunction "A_2") (pintype "unspecified"))
      (node (ref "R39") (pin "1") (pinfunction "1_1") (pintype "unspecified"))
    )
    (net (code "69") (name "Net-(LED6-A)") (class "Default")
      (node (ref "LED6") (pin "2") (pinfunction "A_2") (pintype "unspecified"))
      (node (ref "R40") (pin "1") (pinfunction "1_1") (pintype "unspecified"))
    )
    (net (code "70") (name "Net-(LED7-A)") (class "Default")
      (node (ref "LED7") (pin "2") (pinfunction "A_2") (pintype "unspecified"))
      (node (ref "R123") (pin "1") (pinfunction "1_1") (pintype "unspecified"))
    )
    (net (code "71") (name "Net-(Q1-D)") (class "Default")
      (node (ref "Q1") (pin "3") (pinfunction "D_3") (pintype "unspecified"))
      (node (ref "R21") (pin "2") (pinfunction "2_2") (pintype "input"))
    )
    (net (code "72") (name "Net-(Q1-G)") (class "Default")
      (node (ref "Q1") (pin "1") (pinfunction "G_1") (pintype "unspecified"))
      (node (ref "Q3") (pin "3") (pinfunction "D_3") (pintype "unspecified"))
      (node (ref "R19") (pin "1") (pinfunction "1_1") (pintype "input"))
    )
    (net (code "73") (name "Net-(Q2-D)") (class "Default")
      (node (ref "Q2") (pin "3") (pinfunction "D_3") (pintype "unspecified"))
      (node (ref "R22") (pin "2") (pinfunction "2_2") (pintype "input"))
    )
    (net (code "74") (name "Net-(Q2-G)") (class "Default")
      (node (ref "Q2") (pin "1") (pinfunction "G_1") (pintype "unspecified"))
      (node (ref "Q4") (pin "3") (pinfunction "D_3") (pintype "unspecified"))
      (node (ref "R20") (pin "1") (pinfunction "1_1") (pintype "input"))
    )
    (net (code "75") (name "Net-(Q5-D)") (class "Default")
      (node (ref "Q5") (pin "3") (pinfunction "D_3") (pintype "unspecified"))
      (node (ref "R23") (pin "1") (pinfunction "1_1") (pintype "input"))
      (node (ref "R28") (pin "2") (pinfunction "2_2") (pintype "input"))
      (node (ref "U26") (pin "5") (pinfunction "EN/UVLO_5") (pintype "unspecified"))
    )
    (net (code "76") (name "Net-(Q6-D)") (class "Default")
      (node (ref "Q6") (pin "3") (pinfunction "D_3") (pintype "unspecified"))
      (node (ref "R26") (pin "1") (pinfunction "1_1") (pintype "input"))
      (node (ref "R30") (pin "2") (pinfunction "2_2") (pintype "input"))
      (node (ref "U27") (pin "2") (pinfunction "On/Off_2") (pintype "input"))
    )
    (net (code "77") (name "Net-(Q7-D)") (class "Default")
      (node (ref "Q7") (pin "3") (pinfunction "D_3") (pintype "unspecified"))
      (node (ref "R31") (pin "2") (pinfunction "2_2") (pintype "input"))
    )
    (net (code "78") (name "Net-(Q7-G)") (class "Default")
      (node (ref "Q7") (pin "1") (pinfunction "G_1") (pintype "unspecified"))
      (node (ref "Q8") (pin "3") (pinfunction "D_3") (pintype "unspecified"))
      (node (ref "R29") (pin "1") (pinfunction "1_1") (pintype "input"))
    )
    (net (code "79") (name "Net-(Q9-D)") (class "Default")
      (node (ref "Q9") (pin "3") (pinfunction "D_3") (pintype "unspecified"))
      (node (ref "R44") (pin "2") (pinfunction "2_2") (pintype "input"))
      (node (ref "U40") (pin "4") (pinfunction "G_4") (pintype "unspecified"))
    )
    (net (code "80") (name "Net-(Q10-D)") (class "Default")
      (node (ref "Q10") (pin "3") (pinfunction "D_3") (pintype "unspecified"))
      (node (ref "R47") (pin "2") (pinfunction "2_2") (pintype "input"))
      (node (ref "U44") (pin "4") (pinfunction "G_4") (pintype "unspecified"))
    )
    (net (code "81") (name "Net-(Q10-G)") (class "Default")
      (node (ref "Q10") (pin "1") (pinfunction "G_1") (pintype "unspecified"))
      (node (ref "Q11") (pin "3") (pinfunction "D_3") (pintype "unspecified"))
      (node (ref "R48") (pin "1") (pinfunction "1_1") (pintype "input"))
    )
    (net (code "82") (name "Net-(U1-DRAIN)") (class "Default")
      (node (ref "C9") (pin "2") (pinfunction "2_2") (pintype "unspecified"))
      (node (ref "J1") (pin "2") (pinfunction "2_2") (pintype "unspecified"))
      (node (ref "U1") (pin "5") (pinfunction "DRAIN_5") (pintype "unspecified"))
    )
    (net (code "83") (name "Net-(U1-FB)") (class "Default")
      (node (ref "R1") (pin "2") (pinfunction "2_2") (pintype "input"))
      (node (ref "U1") (pin "6") (pinfunction "SOURCE_6") (pintype "unspecified"))
      (node (ref "U1") (pin "7") (pinfunction "FB_7") (pintype "unspecified"))
    )
    (net (code "84") (name "Net-(U1-SLOPE)") (class "Default")
      (node (ref "C1") (pin "1") (pinfunction "1_1") (pintype "input"))
      (node (ref "U1") (pin "9") (pinfunction "SLOPE_9") (pintype "unspecified"))
    )
    (net (code "85") (name "Net-(U2-DRAIN)") (class "Default")
      (node (ref "C2") (pin "2") (pinfunction "2_2") (pintype "unspecified"))
      (node (ref "J2") (pin "2") (pinfunction "2_2") (pintype "unspecified"))
      (node (ref "U2") (pin "5") (pinfunction "DRAIN_5") (pintype "unspecified"))
    )
    (net (code "86") (name "Net-(U2-FB)") (class "Default")
      (node (ref "R2") (pin "2") (pinfunction "2_2") (pintype "input"))
      (node (ref "U2") (pin "6") (pinfunction "SOURCE_6") (pintype "unspecified"))
      (node (ref "U2") (pin "7") (pinfunction "FB_7") (pintype "unspecified"))
    )
    (net (code "87") (name "Net-(U2-SLOPE)") (class "Default")
      (node (ref "C4") (pin "1") (pinfunction "1_1") (pintype "input"))
      (node (ref "U2") (pin "9") (pinfunction "SLOPE_9") (pintype "unspecified"))
    )
    (net (code "88") (name "Net-(U3-DRAIN)") (class "Default")
      (node (ref "C6") (pin "2") (pinfunction "2_2") (pintype "unspecified"))
      (node (ref "J3") (pin "2") (pinfunction "2_2") (pintype "unspecified"))
      (node (ref "U3") (pin "5") (pinfunction "DRAIN_5") (pintype "unspecified"))
    )
    (net (code "89") (name "Net-(U3-FB)") (class "Default")
      (node (ref "R3") (pin "2") (pinfunction "2_2") (pintype "input"))
      (node (ref "U3") (pin "6") (pinfunction "SOURCE_6") (pintype "unspecified"))
      (node (ref "U3") (pin "7") (pinfunction "FB_7") (pintype "unspecified"))
    )
    (net (code "90") (name "Net-(U3-SLOPE)") (class "Default")
      (node (ref "C7") (pin "1") (pinfunction "1_1") (pintype "input"))
      (node (ref "U3") (pin "9") (pinfunction "SLOPE_9") (pintype "unspecified"))
    )
    (net (code "91") (name "Net-(U4-DRAIN)") (class "Default")
      (node (ref "C10") (pin "2") (pinfunction "2_2") (pintype "unspecified"))
      (node (ref "J4") (pin "2") (pinfunction "2_2") (pintype "unspecified"))
      (node (ref "U4") (pin "5") (pinfunction "DRAIN_5") (pintype "unspecified"))
    )
    (net (code "92") (name "Net-(U4-FB)") (class "Default")
      (node (ref "R4") (pin "2") (pinfunction "2_2") (pintype "input"))
      (node (ref "U4") (pin "6") (pinfunction "SOURCE_6") (pintype "unspecified"))
      (node (ref "U4") (pin "7") (pinfunction "FB_7") (pintype "unspecified"))
    )
    (net (code "93") (name "Net-(U4-SLOPE)") (class "Default")
      (node (ref "C11") (pin "1") (pinfunction "1_1") (pintype "input"))
      (node (ref "U4") (pin "9") (pinfunction "SLOPE_9") (pintype "unspecified"))
    )
    (net (code "94") (name "Net-(U14-DRAIN)") (class "Default")
      (node (ref "C15") (pin "2") (pinfunction "2_2") (pintype "unspecified"))
      (node (ref "J5") (pin "2") (pinfunction "2_2") (pintype "unspecified"))
      (node (ref "U14") (pin "5") (pinfunction "DRAIN_5") (pintype "unspecified"))
    )
    (net (code "95") (name "Net-(U14-FB)") (class "Default")
      (node (ref "R7") (pin "2") (pinfunction "2_2") (pintype "input"))
      (node (ref "U14") (pin "6") (pinfunction "SOURCE_6") (pintype "unspecified"))
      (node (ref "U14") (pin "7") (pinfunction "FB_7") (pintype "unspecified"))
    )
    (net (code "96") (name "Net-(U14-SLOPE)") (class "Default")
      (node (ref "C14") (pin "1") (pinfunction "1_1") (pintype "input"))
      (node (ref "U14") (pin "9") (pinfunction "SLOPE_9") (pintype "unspecified"))
    )
    (net (code "97") (name "Net-(U15-DRAIN)") (class "Default")
      (node (ref "C18") (pin "2") (pinfunction "2_2") (pintype "unspecified"))
      (node (ref "J6") (pin "2") (pinfunction "2_2") (pintype "unspecified"))
      (node (ref "U15") (pin "5") (pinfunction "DRAIN_5") (pintype "unspecified"))
    )
    (net (code "98") (name "Net-(U15-FB)") (class "Default")
      (node (ref "R8") (pin "2") (pinfunction "2_2") (pintype "input"))
      (node (ref "U15") (pin "6") (pinfunction "SOURCE_6") (pintype "unspecified"))
      (node (ref "U15") (pin "7") (pinfunction "FB_7") (pintype "unspecified"))
    )
    (net (code "99") (name "Net-(U15-SLOPE)") (class "Default")
      (node (ref "C17") (pin "1") (pinfunction "1_1") (pintype "input"))
      (node (ref "U15") (pin "9") (pinfunction "SLOPE_9") (pintype "unspecified"))
    )
    (net (code "100") (name "Net-(U16-DRAIN)") (class "Default")
      (node (ref "C21") (pin "2") (pinfunction "2_2") (pintype "unspecified"))
      (node (ref "J7") (pin "2") (pinfunction "2_2") (pintype "unspecified"))
      (node (ref "U16") (pin "5") (pinfunction "DRAIN_5") (pintype "unspecified"))
    )
    (net (code "101") (name "Net-(U16-FB)") (class "Default")
      (node (ref "R9") (pin "2") (pinfunction "2_2") (pintype "input"))
      (node (ref "U16") (pin "6") (pinfunction "SOURCE_6") (pintype "unspecified"))
      (node (ref "U16") (pin "7") (pinfunction "FB_7") (pintype "unspecified"))
    )
    (net (code "102") (name "Net-(U16-SLOPE)") (class "Default")
      (node (ref "C20") (pin "1") (pinfunction "1_1") (pintype "input"))
      (node (ref "U16") (pin "9") (pinfunction "SLOPE_9") (pintype "unspecified"))
    )
    (net (code "103") (name "Net-(U17-DRAIN)") (class "Default")
      (node (ref "C22") (pin "2") (pinfunction "2_2") (pintype "unspecified"))
      (node (ref "J8") (pin "2") (pinfunction "2_2") (pintype "unspecified"))
      (node (ref "U17") (pin "5") (pinfunction "DRAIN_5") (pintype "unspecified"))
    )
    (net (code "104") (name "Net-(U17-FB)") (class "Default")
      (node (ref "R10") (pin "2") (pinfunction "2_2") (pintype "input"))
      (node (ref "U17") (pin "6") (pinfunction "SOURCE_6") (pintype "unspecified"))
      (node (ref "U17") (pin "7") (pinfunction "FB_7") (pintype "unspecified"))
    )
    (net (code "105") (name "Net-(U17-SLOPE)") (class "Default")
      (node (ref "C23") (pin "1") (pinfunction "1_1") (pintype "input"))
      (node (ref "U17") (pin "9") (pinfunction "SLOPE_9") (pintype "unspecified"))
    )
    (net (code "106") (name "Net-(U18-DRAIN)") (class "Default")
      (node (ref "C27") (pin "2") (pinfunction "2_2") (pintype "unspecified"))
      (node (ref "J9") (pin "2") (pinfunction "2_2") (pintype "unspecified"))
      (node (ref "U18") (pin "5") (pinfunction "DRAIN_5") (pintype "unspecified"))
    )
    (net (code "107") (name "Net-(U18-FB)") (class "Default")
      (node (ref "R11") (pin "2") (pinfunction "2_2") (pintype "input"))
      (node (ref "U18") (pin "6") (pinfunction "SOURCE_6") (pintype "unspecified"))
      (node (ref "U18") (pin "7") (pinfunction "FB_7") (pintype "unspecified"))
    )
    (net (code "108") (name "Net-(U18-SLOPE)") (class "Default")
      (node (ref "C26") (pin "1") (pinfunction "1_1") (pintype "input"))
      (node (ref "U18") (pin "9") (pinfunction "SLOPE_9") (pintype "unspecified"))
    )
    (net (code "109") (name "Net-(U19-DRAIN)") (class "Default")
      (node (ref "C30") (pin "2") (pinfunction "2_2") (pintype "unspecified"))
      (node (ref "J10") (pin "2") (pinfunction "2_2") (pintype "unspecified"))
      (node (ref "U19") (pin "5") (pinfunction "DRAIN_5") (pintype "unspecified"))
    )
    (net (code "110") (name "Net-(U19-FB)") (class "Default")
      (node (ref "R12") (pin "2") (pinfunction "2_2") (pintype "input"))
      (node (ref "U19") (pin "6") (pinfunction "SOURCE_6") (pintype "unspecified"))
      (node (ref "U19") (pin "7") (pinfunction "FB_7") (pintype "unspecified"))
    )
    (net (code "111") (name "Net-(U19-SLOPE)") (class "Default")
      (node (ref "C29") (pin "1") (pinfunction "1_1") (pintype "input"))
      (node (ref "U19") (pin "9") (pinfunction "SLOPE_9") (pintype "unspecified"))
    )
    (net (code "112") (name "Net-(U20-DRAIN)") (class "Default")
      (node (ref "C33") (pin "2") (pinfunction "2_2") (pintype "unspecified"))
      (node (ref "J11") (pin "2") (pinfunction "2_2") (pintype "unspecified"))
      (node (ref "U20") (pin "5") (pinfunction "DRAIN_5") (pintype "unspecified"))
    )
    (net (code "113") (name "Net-(U20-FB)") (class "Default")
      (node (ref "R13") (pin "2") (pinfunction "2_2") (pintype "input"))
      (node (ref "U20") (pin "6") (pinfunction "SOURCE_6") (pintype "unspecified"))
      (node (ref "U20") (pin "7") (pinfunction "FB_7") (pintype "unspecified"))
    )
    (net (code "114") (name "Net-(U20-SLOPE)") (class "Default")
      (node (ref "C32") (pin "1") (pinfunction "1_1") (pintype "input"))
      (node (ref "U20") (pin "9") (pinfunction "SLOPE_9") (pintype "unspecified"))
    )
    (net (code "115") (name "Net-(U21-DRAIN)") (class "Default")
      (node (ref "C34") (pin "2") (pinfunction "2_2") (pintype "unspecified"))
      (node (ref "J12") (pin "2") (pinfunction "2_2") (pintype "unspecified"))
      (node (ref "U21") (pin "5") (pinfunction "DRAIN_5") (pintype "unspecified"))
    )
    (net (code "116") (name "Net-(U21-FB)") (class "Default")
      (node (ref "R14") (pin "2") (pinfunction "2_2") (pintype "input"))
      (node (ref "U21") (pin "6") (pinfunction "SOURCE_6") (pintype "unspecified"))
      (node (ref "U21") (pin "7") (pinfunction "FB_7") (pintype "unspecified"))
    )
    (net (code "117") (name "Net-(U21-SLOPE)") (class "Default")
      (node (ref "C35") (pin "1") (pinfunction "1_1") (pintype "input"))
      (node (ref "U21") (pin "9") (pinfunction "SLOPE_9") (pintype "unspecified"))
    )
    (net (code "118") (name "Net-(U22-DRAIN)") (class "Default")
      (node (ref "C39") (pin "2") (pinfunction "2_2") (pintype "unspecified"))
      (node (ref "J13") (pin "2") (pinfunction "2_2") (pintype "unspecified"))
      (node (ref "U22") (pin "5") (pinfunction "DRAIN_5") (pintype "unspecified"))
    )
    (net (code "119") (name "Net-(U22-FB)") (class "Default")
      (node (ref "R15") (pin "2") (pinfunction "2_2") (pintype "input"))
      (node (ref "U22") (pin "6") (pinfunction "SOURCE_6") (pintype "unspecified"))
      (node (ref "U22") (pin "7") (pinfunction "FB_7") (pintype "unspecified"))
    )
    (net (code "120") (name "Net-(U22-SLOPE)") (class "Default")
      (node (ref "C38") (pin "1") (pinfunction "1_1") (pintype "input"))
      (node (ref "U22") (pin "9") (pinfunction "SLOPE_9") (pintype "unspecified"))
    )
    (net (code "121") (name "Net-(U23-DRAIN)") (class "Default")
      (node (ref "C42") (pin "2") (pinfunction "2_2") (pintype "unspecified"))
      (node (ref "J14") (pin "2") (pinfunction "2_2") (pintype "unspecified"))
      (node (ref "U23") (pin "5") (pinfunction "DRAIN_5") (pintype "unspecified"))
    )
    (net (code "122") (name "Net-(U23-FB)") (class "Default")
      (node (ref "R16") (pin "2") (pinfunction "2_2") (pintype "input"))
      (node (ref "U23") (pin "6") (pinfunction "SOURCE_6") (pintype "unspecified"))
      (node (ref "U23") (pin "7") (pinfunction "FB_7") (pintype "unspecified"))
    )
    (net (code "123") (name "Net-(U23-SLOPE)") (class "Default")
      (node (ref "C41") (pin "1") (pinfunction "1_1") (pintype "input"))
      (node (ref "U23") (pin "9") (pinfunction "SLOPE_9") (pintype "unspecified"))
    )
    (net (code "124") (name "Net-(U24-DRAIN)") (class "Default")
      (node (ref "C45") (pin "2") (pinfunction "2_2") (pintype "unspecified"))
      (node (ref "J15") (pin "2") (pinfunction "2_2") (pintype "unspecified"))
      (node (ref "U24") (pin "5") (pinfunction "DRAIN_5") (pintype "unspecified"))
    )
    (net (code "125") (name "Net-(U24-FB)") (class "Default")
      (node (ref "R17") (pin "2") (pinfunction "2_2") (pintype "input"))
      (node (ref "U24") (pin "6") (pinfunction "SOURCE_6") (pintype "unspecified"))
      (node (ref "U24") (pin "7") (pinfunction "FB_7") (pintype "unspecified"))
    )
    (net (code "126") (name "Net-(U24-SLOPE)") (class "Default")
      (node (ref "C44") (pin "1") (pinfunction "1_1") (pintype "input"))
      (node (ref "U24") (pin "9") (pinfunction "SLOPE_9") (pintype "unspecified"))
    )
    (net (code "127") (name "Net-(U25-DRAIN)") (class "Default")
      (node (ref "C46") (pin "2") (pinfunction "2_2") (pintype "unspecified"))
      (node (ref "J16") (pin "2") (pinfunction "2_2") (pintype "unspecified"))
      (node (ref "U25") (pin "5") (pinfunction "DRAIN_5") (pintype "unspecified"))
    )
    (net (code "128") (name "Net-(U25-FB)") (class "Default")
      (node (ref "R18") (pin "2") (pinfunction "2_2") (pintype "input"))
      (node (ref "U25") (pin "6") (pinfunction "SOURCE_6") (pintype "unspecified"))
      (node (ref "U25") (pin "7") (pinfunction "FB_7") (pintype "unspecified"))
    )
    (net (code "129") (name "Net-(U25-SLOPE)") (class "Default")
      (node (ref "C47") (pin "1") (pinfunction "1_1") (pintype "input"))
      (node (ref "U25") (pin "9") (pinfunction "SLOPE_9") (pintype "unspecified"))
    )
    (net (code "130") (name "Net-(U26-SS)") (class "Default")
      (node (ref "C59") (pin "2") (pinfunction "2_2") (pintype "unspecified"))
      (node (ref "U26") (pin "7") (pinfunction "SS_7") (pintype "unspecified"))
    )
    (net (code "131") (name "Net-(U26-Vset)") (class "Default")
      (node (ref "R27") (pin "2") (pinfunction "2_2") (pintype "input"))
      (node (ref "U26") (pin "6") (pinfunction "Vset_6") (pintype "unspecified"))
    )
    (net (code "132") (name "Net-(U28-G)") (class "Default")
      (node (ref "R38") (pin "2") (pinfunction "2_2") (pintype "input"))
      (node (ref "U28") (pin "4") (pinfunction "G_4") (pintype "unspecified"))
      (node (ref "U32") (pin "3") (pinfunction "BIAS_3") (pintype "unspecified"))
    )
    (net (code "133") (name "Net-(U32-REF)") (class "Default")
      (node (ref "R35") (pin "2") (pinfunction "2_2") (pintype "input"))
      (node (ref "U32") (pin "2") (pinfunction "REF_2") (pintype "unspecified"))
    )
    (net (code "134") (name "Net-(U34-G)") (class "Default")
      (node (ref "R42") (pin "2") (pinfunction "2_2") (pintype "input"))
      (node (ref "U34") (pin "4") (pinfunction "G_4") (pintype "unspecified"))
      (node (ref "U37") (pin "3") (pinfunction "BIAS_3") (pintype "unspecified"))
    )
    (net (code "135") (name "Net-(U37-REF)") (class "Default")
      (node (ref "R41") (pin "2") (pinfunction "2_2") (pintype "input"))
      (node (ref "U37") (pin "2") (pinfunction "REF_2") (pintype "unspecified"))
    )
    (net (code "136") (name "Net-(U39-G)") (class "Default")
      (node (ref "R46") (pin "2") (pinfunction "2_2") (pintype "input"))
      (node (ref "U39") (pin "4") (pinfunction "G_4") (pintype "unspecified"))
      (node (ref "U43") (pin "3") (pinfunction "BIAS_3") (pintype "unspecified"))
    )
    (net (code "137") (name "Net-(U43-REF)") (class "Default")
      (node (ref "R45") (pin "2") (pinfunction "2_2") (pintype "input"))
      (node (ref "U43") (pin "2") (pinfunction "REF_2") (pintype "unspecified"))
    )
    (net (code "138") (name "Net-(U43-SOURCE)") (class "Default")
      (node (ref "R44") (pin "1") (pinfunction "1_1") (pintype "input"))
      (node (ref "U39") (pin "1") (pinfunction "S_1") (pintype "unspecified"))
      (node (ref "U39") (pin "2") (pinfunction "S_2") (pintype "unspecified"))
      (node (ref "U39") (pin "3") (pinfunction "S_3") (pintype "unspecified"))
      (node (ref "U40") (pin "1") (pinfunction "S_1") (pintype "unspecified"))
      (node (ref "U40") (pin "2") (pinfunction "S_2") (pintype "unspecified"))
      (node (ref "U40") (pin "3") (pinfunction "S_3") (pintype "unspecified"))
      (node (ref "U43") (pin "4") (pinfunction "SOURCE_4") (pintype "unspecified"))
    )
    (net (code "139") (name "Net-(U44-D)") (class "Default")
      (node (ref "R47") (pin "1") (pinfunction "1_1") (pintype "input"))
      (node (ref "R48") (pin "2") (pinfunction "2_2") (pintype "input"))
      (node (ref "U44") (pin "5") (pinfunction "D_5") (pintype "unspecified"))
      (node (ref "U45") (pin "2") (pinfunction "PV+_2") (pintype "unspecified"))
    )
    (net (code "140") (name "Net-(U46-EN{slash}ENB)") (class "Default")
      (node (ref "H1") (pin "1") (pinfunction "1_1") (pintype "unspecified"))
      (node (ref "R113") (pin "2") (pinfunction "2_2") (pintype "input"))
      (node (ref "U46") (pin "3") (pinfunction "EN/ENB_3") (pintype "unspecified"))
    )
    (net (code "141") (name "Net-(U47-Y1)") (class "Default")
      (node (ref "R50") (pin "1") (pinfunction "1_1") (pintype "input"))
      (node (ref "U47") (pin "18") (pinfunction "Y1_18") (pintype "unspecified"))
    )
    (net (code "142") (name "Net-(U47-Y2)") (class "Default")
      (node (ref "R51") (pin "1") (pinfunction "1_1") (pintype "input"))
      (node (ref "U47") (pin "17") (pinfunction "Y2_17") (pintype "unspecified"))
    )
    (net (code "143") (name "Net-(U47-Y3)") (class "Default")
      (node (ref "R54") (pin "1") (pinfunction "1_1") (pintype "input"))
      (node (ref "U47") (pin "16") (pinfunction "Y3_16") (pintype "unspecified"))
    )
    (net (code "144") (name "Net-(U47-Y4)") (class "Default")
      (node (ref "R56") (pin "1") (pinfunction "1_1") (pintype "input"))
      (node (ref "U47") (pin "15") (pinfunction "Y4_15") (pintype "unspecified"))
    )
    (net (code "145") (name "Net-(U47-Y5)") (class "Default")
      (node (ref "R58") (pin "1") (pinfunction "1_1") (pintype "input"))
      (node (ref "U47") (pin "14") (pinfunction "Y5_14") (pintype "unspecified"))
    )
    (net (code "146") (name "Net-(U47-Y6)") (class "Default")
      (node (ref "R60") (pin "1") (pinfunction "1_1") (pintype "input"))
      (node (ref "U47") (pin "13") (pinfunction "Y6_13") (pintype "unspecified"))
    )
    (net (code "147") (name "Net-(U47-Y7)") (class "Default")
      (node (ref "R63") (pin "1") (pinfunction "1_1") (pintype "input"))
      (node (ref "U47") (pin "12") (pinfunction "Y7_12") (pintype "unspecified"))
    )
    (net (code "148") (name "Net-(U47-Y8)") (class "Default")
      (node (ref "R66") (pin "1") (pinfunction "1_1") (pintype "input"))
      (node (ref "U47") (pin "11") (pinfunction "Y8_11") (pintype "unspecified"))
    )
    (net (code "149") (name "Net-(U48-1Y)") (class "Default")
      (node (ref "R52") (pin "1") (pinfunction "1_1") (pintype "input"))
      (node (ref "U48") (pin "6") (pinfunction "1Y_6") (pintype "unspecified"))
    )
    (net (code "150") (name "Net-(U48-2Y)") (class "Default")
      (node (ref "R61") (pin "1") (pinfunction "1_1") (pintype "input"))
      (node (ref "U48") (pin "4") (pinfunction "2Y_4") (pintype "unspecified"))
    )
    (net (code "151") (name "Net-(U49-Y1)") (class "Default")
      (node (ref "R53") (pin "1") (pinfunction "1_1") (pintype "input"))
      (node (ref "U49") (pin "18") (pinfunction "Y1_18") (pintype "unspecified"))
    )
    (net (code "152") (name "Net-(U49-Y2)") (class "Default")
      (node (ref "R55") (pin "1") (pinfunction "1_1") (pintype "input"))
      (node (ref "U49") (pin "17") (pinfunction "Y2_17") (pintype "unspecified"))
    )
    (net (code "153") (name "Net-(U49-Y3)") (class "Default")
      (node (ref "R57") (pin "1") (pinfunction "1_1") (pintype "input"))
      (node (ref "U49") (pin "16") (pinfunction "Y3_16") (pintype "unspecified"))
    )
    (net (code "154") (name "Net-(U49-Y4)") (class "Default")
      (node (ref "R59") (pin "1") (pinfunction "1_1") (pintype "input"))
      (node (ref "U49") (pin "15") (pinfunction "Y4_15") (pintype "unspecified"))
    )
    (net (code "155") (name "Net-(U49-Y5)") (class "Default")
      (node (ref "R62") (pin "1") (pinfunction "1_1") (pintype "input"))
      (node (ref "U49") (pin "14") (pinfunction "Y5_14") (pintype "unspecified"))
    )
    (net (code "156") (name "Net-(U49-Y6)") (class "Default")
      (node (ref "R64") (pin "1") (pinfunction "1_1") (pintype "input"))
      (node (ref "U49") (pin "13") (pinfunction "Y6_13") (pintype "unspecified"))
    )
    (net (code "157") (name "Net-(U49-Y7)") (class "Default")
      (node (ref "R65") (pin "1") (pinfunction "1_1") (pintype "input"))
      (node (ref "U49") (pin "12") (pinfunction "Y7_12") (pintype "unspecified"))
    )
    (net (code "158") (name "Net-(U49-Y8)") (class "Default")
      (node (ref "R67") (pin "1") (pinfunction "1_1") (pintype "input"))
      (node (ref "U49") (pin "11") (pinfunction "Y8_11") (pintype "unspecified"))
    )
    (net (code "159") (name "Net-(U59-1Y)") (class "Default")
      (node (ref "R102") (pin "1") (pinfunction "1_1") (pintype "input"))
      (node (ref "U59") (pin "6") (pinfunction "1Y_6") (pintype "unspecified"))
    )
    (net (code "160") (name "Net-(U59-2Y)") (class "Default")
      (node (ref "R106") (pin "1") (pinfunction "1_1") (pintype "input"))
      (node (ref "U59") (pin "4") (pinfunction "2Y_4") (pintype "unspecified"))
    )
    (net (code "161") (name "Net-(U60-1Y)") (class "Default")
      (node (ref "R105") (pin "1") (pinfunction "1_1") (pintype "input"))
      (node (ref "U60") (pin "6") (pinfunction "1Y_6") (pintype "unspecified"))
    )
    (net (code "162") (name "Net-(U60-2Y)") (class "Default")
      (node (ref "R107") (pin "1") (pinfunction "1_1") (pintype "input"))
      (node (ref "U60") (pin "4") (pinfunction "2Y_4") (pintype "unspecified"))
    )
    (net (code "163") (name "Net-(U61-PV+)") (class "Default")
      (node (ref "U61") (pin "2") (pinfunction "PV+_2") (pintype "unspecified"))
      (node (ref "U65") (pin "2") (pinfunction "D_2") (pintype "unspecified"))
    )
    (net (code "164") (name "Net-(U62-PV+)") (class "Default")
      (node (ref "U62") (pin "2") (pinfunction "PV+_2") (pintype "unspecified"))
      (node (ref "U64") (pin "2") (pinfunction "D_2") (pintype "unspecified"))
    )
    (net (code "165") (name "Net-(U63-1Y)") (class "Default")
      (node (ref "R110") (pin "1") (pinfunction "1_1") (pintype "input"))
      (node (ref "U63") (pin "6") (pinfunction "1Y_6") (pintype "unspecified"))
    )
    (net (code "166") (name "Net-(U63-2Y)") (class "Default")
      (node (ref "R111") (pin "1") (pinfunction "1_1") (pintype "input"))
      (node (ref "U63") (pin "4") (pinfunction "2Y_4") (pintype "unspecified"))
    )
    (net (code "167") (name "Net-(U67-1Y)") (class "Default")
      (node (ref "R114") (pin "1") (pinfunction "1_1") (pintype "input"))
      (node (ref "U67") (pin "6") (pinfunction "1Y_6") (pintype "unspecified"))
    )
    (net (code "168") (name "Net-(U67-2Y)") (class "Default")
      (node (ref "R116") (pin "1") (pinfunction "1_1") (pintype "input"))
      (node (ref "U67") (pin "4") (pinfunction "2Y_4") (pintype "unspecified"))
    )
    (net (code "169") (name "Net-(U70-Vin)") (class "Default")
      (node (ref "C74") (pin "2") (pinfunction "2_2") (pintype "unspecified"))
      (node (ref "D1") (pin "1") (pinfunction "1_1") (pintype "unspecified"))
      (node (ref "D1") (pin "2") (pinfunction "2_2") (pintype "unspecified"))
      (node (ref "U70") (pin "3") (pinfunction "Vin_3") (pintype "unspecified"))
      (node (ref "U71") (pin "1") (pinfunction "1_1") (pintype "unspecified"))
    )
    (net (code "170") (name "Net-(U75-PV+)") (class "Default")
      (node (ref "U75") (pin "2") (pinfunction "PV+_2") (pintype "unspecified"))
      (node (ref "U76") (pin "2") (pinfunction "D_2") (pintype "unspecified"))
    )
    (net (code "171") (name "Pet_dog_H") (class "Default")
      (node (ref "U46") (pin "4") (pinfunction "WD_4") (pintype "unspecified"))
      (node (ref "U69") (pin "A2") (pinfunction "A2_A2") (pintype "unspecified"))
    )
    (net (code "172") (name "RST_Pressure_0_L") (class "Default")
      (node (ref "R51") (pin "2") (pinfunction "2_2") (pintype "input"))
      (node (ref "U54") (pin "10") (pinfunction "nRST_10") (pintype "unspecified"))
    )
    (net (code "173") (name "RST_Pressure_1_L") (class "Default")
      (node (ref "R56") (pin "2") (pinfunction "2_2") (pintype "input"))
      (node (ref "U56") (pin "10") (pinfunction "nRST_10") (pintype "unspecified"))
    )
    (net (code "174") (name "RST_Pressure_2_L") (class "Default")
      (node (ref "R60") (pin "2") (pinfunction "2_2") (pintype "input"))
      (node (ref "U57") (pin "10") (pinfunction "nRST_10") (pintype "unspecified"))
    )
    (net (code "175") (name "Reset_Buffer_0_L") (class "Default")
      (node (ref "R61") (pin "2") (pinfunction "2_2") (pintype "input"))
      (node (ref "U49") (pin "2") (pinfunction "A1_2") (pintype "unspecified"))
      (node (ref "U49") (pin "3") (pinfunction "A2_3") (pintype "unspecified"))
      (node (ref "U49") (pin "4") (pinfunction "A3_4") (pintype "unspecified"))
      (node (ref "U49") (pin "5") (pinfunction "A4_5") (pintype "unspecified"))
      (node (ref "U49") (pin "6") (pinfunction "A5_6") (pintype "unspecified"))
      (node (ref "U49") (pin "7") (pinfunction "A6_7") (pintype "unspecified"))
      (node (ref "U49") (pin "8") (pinfunction "A7_8") (pintype "unspecified"))
      (node (ref "U49") (pin "9") (pinfunction "A8_9") (pintype "unspecified"))
    )
    (net (code "176") (name "Reset_Buffer_1_L") (class "Default")
      (node (ref "R52") (pin "2") (pinfunction "2_2") (pintype "input"))
      (node (ref "U47") (pin "2") (pinfunction "A1_2") (pintype "unspecified"))
      (node (ref "U47") (pin "3") (pinfunction "A2_3") (pintype "unspecified"))
      (node (ref "U47") (pin "4") (pinfunction "A3_4") (pintype "unspecified"))
      (node (ref "U47") (pin "5") (pinfunction "A4_5") (pintype "unspecified"))
      (node (ref "U47") (pin "6") (pinfunction "A5_6") (pintype "unspecified"))
      (node (ref "U47") (pin "7") (pinfunction "A6_7") (pintype "unspecified"))
      (node (ref "U47") (pin "8") (pinfunction "A7_8") (pintype "unspecified"))
      (node (ref "U47") (pin "9") (pinfunction "A8_9") (pintype "unspecified"))
    )
    (net (code "177") (name "SCL_A{slash}D") (class "Default")
      (node (ref "R92") (pin "1") (pinfunction "1_1") (pintype "input"))
      (node (ref "U52") (pin "10") (pinfunction "SC2_10") (pintype "unspecified"))
      (node (ref "U68") (pin "16") (pinfunction "SCL_16") (pintype "unspecified"))
    )
    (net (code "178") (name "SCL_IMU0") (class "Default")
      (node (ref "CN4") (pin "4") (pinfunction "4_4") (pintype "unspecified"))
      (node (ref "R71") (pin "1") (pinfunction "1_1") (pintype "input"))
      (node (ref "U50") (pin "5") (pinfunction "SC0_5") (pintype "unspecified"))
    )
    (net (code "179") (name "SCL_IMU1") (class "Default")
      (node (ref "CN3") (pin "4") (pinfunction "4_4") (pintype "unspecified"))
      (node (ref "R73") (pin "1") (pinfunction "1_1") (pintype "input"))
      (node (ref "U50") (pin "7") (pinfunction "SC1_7") (pintype "unspecified"))
    )
    (net (code "180") (name "SCL_IMU2") (class "Default")
      (node (ref "CN2") (pin "4") (pinfunction "4_4") (pintype "unspecified"))
      (node (ref "R75") (pin "1") (pinfunction "1_1") (pintype "input"))
      (node (ref "U50") (pin "10") (pinfunction "SC2_10") (pintype "unspecified"))
    )
    (net (code "181") (name "SCL_IMU3") (class "Default")
      (node (ref "CN1") (pin "4") (pinfunction "4_4") (pintype "unspecified"))
      (node (ref "R77") (pin "1") (pinfunction "1_1") (pintype "input"))
      (node (ref "U50") (pin "12") (pinfunction "SC3_12") (pintype "unspecified"))
    )
    (net (code "182") (name "SCL_IMU4") (class "Default")
      (node (ref "CN7") (pin "4") (pinfunction "4_4") (pintype "unspecified"))
      (node (ref "R79") (pin "1") (pinfunction "1_1") (pintype "input"))
      (node (ref "U51") (pin "5") (pinfunction "SC0_5") (pintype "unspecified"))
    )
    (net (code "183") (name "SCL_IMU5") (class "Default")
      (node (ref "CN5") (pin "4") (pinfunction "4_4") (pintype "unspecified"))
      (node (ref "R81") (pin "1") (pinfunction "1_1") (pintype "input"))
      (node (ref "U51") (pin "7") (pinfunction "SC1_7") (pintype "unspecified"))
    )
    (net (code "184") (name "SCL_IMU6") (class "Default")
      (node (ref "CN8") (pin "4") (pinfunction "4_4") (pintype "unspecified"))
      (node (ref "R83") (pin "1") (pinfunction "1_1") (pintype "input"))
      (node (ref "U51") (pin "10") (pinfunction "SC2_10") (pintype "unspecified"))
    )
    (net (code "185") (name "SCL_IMU7") (class "Default")
      (node (ref "CN6") (pin "4") (pinfunction "4_4") (pintype "unspecified"))
      (node (ref "R85") (pin "1") (pinfunction "1_1") (pintype "input"))
      (node (ref "U51") (pin "12") (pinfunction "SC3_12") (pintype "unspecified"))
    )
    (net (code "186") (name "SCL_Pressure_0") (class "Default")
      (node (ref "R95") (pin "1") (pinfunction "1_1") (pintype "input"))
      (node (ref "U53") (pin "5") (pinfunction "SC0_5") (pintype "unspecified"))
      (node (ref "U54") (pin "2") (pinfunction "MOSI/SCL_2") (pintype "unspecified"))
    )
    (net (code "187") (name "SCL_Pressure_1") (class "Default")
      (node (ref "R97") (pin "1") (pinfunction "1_1") (pintype "input"))
      (node (ref "U53") (pin "7") (pinfunction "SC1_7") (pintype "unspecified"))
      (node (ref "U56") (pin "2") (pinfunction "MOSI/SCL_2") (pintype "unspecified"))
    )
    (net (code "188") (name "SCL_Pressure_2") (class "Default")
      (node (ref "R99") (pin "1") (pinfunction "1_1") (pintype "input"))
      (node (ref "U53") (pin "10") (pinfunction "SC2_10") (pintype "unspecified"))
      (node (ref "U57") (pin "2") (pinfunction "MOSI/SCL_2") (pintype "unspecified"))
    )
    (net (code "189") (name "SCL_Spare") (class "Default")
      (node (ref "CN9") (pin "4") (pinfunction "4_4") (pintype "unspecified"))
      (node (ref "R90") (pin "1") (pinfunction "1_1") (pintype "input"))
      (node (ref "U52") (pin "12") (pinfunction "SC3_12") (pintype "unspecified"))
    )
    (net (code "190") (name "SCL_Temp_external") (class "Default")
      (node (ref "CN10") (pin "4") (pinfunction "4_4") (pintype "unspecified"))
      (node (ref "R89") (pin "1") (pinfunction "1_1") (pintype "input"))
      (node (ref "U52") (pin "7") (pinfunction "SC1_7") (pintype "unspecified"))
    )
    (net (code "191") (name "SCL_Temp_internal") (class "Default")
      (node (ref "R87") (pin "1") (pinfunction "1_1") (pintype "input"))
      (node (ref "U52") (pin "5") (pinfunction "SC0_5") (pintype "unspecified"))
      (node (ref "U55") (pin "2") (pinfunction "CLK_2") (pintype "unspecified"))
    )
    (net (code "192") (name "SCL_Up") (class "Default")
      (node (ref "U52") (pin "14") (pinfunction "SCL_14") (pintype "unspecified"))
      (node (ref "U53") (pin "14") (pinfunction "SCL_14") (pintype "unspecified"))
    )
    (net (code "193") (name "SCL_uP") (class "Default")
      (node (ref "R68") (pin "1") (pinfunction "1_1") (pintype "input"))
      (node (ref "U50") (pin "14") (pinfunction "SCL_14") (pintype "unspecified"))
      (node (ref "U51") (pin "14") (pinfunction "SCL_14") (pintype "unspecified"))
      (node (ref "U69") (pin "D3") (pinfunction "D3_D3") (pintype "unspecified"))
    )
    (net (code "194") (name "SDA_A{slash}D") (class "Default")
      (node (ref "R93") (pin "1") (pinfunction "1_1") (pintype "input"))
      (node (ref "U52") (pin "9") (pinfunction "SD2_9") (pintype "unspecified"))
      (node (ref "U68") (pin "15") (pinfunction "SDA_15") (pintype "unspecified"))
    )
    (net (code "195") (name "SDA_IMU0") (class "Default")
      (node (ref "CN4") (pin "3") (pinfunction "3_3") (pintype "unspecified"))
      (node (ref "R70") (pin "1") (pinfunction "1_1") (pintype "input"))
      (node (ref "U50") (pin "4") (pinfunction "SD0_4") (pintype "unspecified"))
    )
    (net (code "196") (name "SDA_IMU1") (class "Default")
      (node (ref "CN3") (pin "3") (pinfunction "3_3") (pintype "unspecified"))
      (node (ref "R72") (pin "1") (pinfunction "1_1") (pintype "input"))
      (node (ref "U50") (pin "6") (pinfunction "SD1_6") (pintype "unspecified"))
    )
    (net (code "197") (name "SDA_IMU2") (class "Default")
      (node (ref "CN2") (pin "3") (pinfunction "3_3") (pintype "unspecified"))
      (node (ref "R74") (pin "1") (pinfunction "1_1") (pintype "input"))
      (node (ref "U50") (pin "9") (pinfunction "SD2_9") (pintype "unspecified"))
    )
    (net (code "198") (name "SDA_IMU3") (class "Default")
      (node (ref "CN1") (pin "3") (pinfunction "3_3") (pintype "unspecified"))
      (node (ref "R76") (pin "1") (pinfunction "1_1") (pintype "input"))
      (node (ref "U50") (pin "11") (pinfunction "SD3_11") (pintype "unspecified"))
    )
    (net (code "199") (name "SDA_IMU4") (class "Default")
      (node (ref "CN7") (pin "3") (pinfunction "3_3") (pintype "unspecified"))
      (node (ref "R78") (pin "1") (pinfunction "1_1") (pintype "input"))
      (node (ref "U51") (pin "4") (pinfunction "SD0_4") (pintype "unspecified"))
    )
    (net (code "200") (name "SDA_IMU5") (class "Default")
      (node (ref "CN5") (pin "3") (pinfunction "3_3") (pintype "unspecified"))
      (node (ref "R80") (pin "1") (pinfunction "1_1") (pintype "input"))
      (node (ref "U51") (pin "6") (pinfunction "SD1_6") (pintype "unspecified"))
    )
    (net (code "201") (name "SDA_IMU6") (class "Default")
      (node (ref "CN8") (pin "3") (pinfunction "3_3") (pintype "unspecified"))
      (node (ref "R82") (pin "1") (pinfunction "1_1") (pintype "input"))
      (node (ref "U51") (pin "9") (pinfunction "SD2_9") (pintype "unspecified"))
    )
    (net (code "202") (name "SDA_IMU7") (class "Default")
      (node (ref "CN6") (pin "3") (pinfunction "3_3") (pintype "unspecified"))
      (node (ref "R84") (pin "1") (pinfunction "1_1") (pintype "input"))
      (node (ref "U51") (pin "11") (pinfunction "SD3_11") (pintype "unspecified"))
    )
    (net (code "203") (name "SDA_Pressure_0") (class "Default")
      (node (ref "R94") (pin "1") (pinfunction "1_1") (pintype "input"))
      (node (ref "U53") (pin "4") (pinfunction "SD0_4") (pintype "unspecified"))
      (node (ref "U54") (pin "3") (pinfunction "MISO/SDA_3") (pintype "unspecified"))
    )
    (net (code "204") (name "SDA_Pressure_1") (class "Default")
      (node (ref "R96") (pin "1") (pinfunction "1_1") (pintype "input"))
      (node (ref "U53") (pin "6") (pinfunction "SD1_6") (pintype "unspecified"))
      (node (ref "U56") (pin "3") (pinfunction "MISO/SDA_3") (pintype "unspecified"))
    )
    (net (code "205") (name "SDA_Pressure_2") (class "Default")
      (node (ref "R98") (pin "1") (pinfunction "1_1") (pintype "input"))
      (node (ref "U53") (pin "9") (pinfunction "SD2_9") (pintype "unspecified"))
      (node (ref "U57") (pin "3") (pinfunction "MISO/SDA_3") (pintype "unspecified"))
    )
    (net (code "206") (name "SDA_Spare") (class "Default")
      (node (ref "CN9") (pin "3") (pinfunction "3_3") (pintype "unspecified"))
      (node (ref "R91") (pin "1") (pinfunction "1_1") (pintype "input"))
      (node (ref "U52") (pin "11") (pinfunction "SD3_11") (pintype "unspecified"))
    )
    (net (code "207") (name "SDA_Temp_external") (class "Default")
      (node (ref "CN10") (pin "3") (pinfunction "3_3") (pintype "unspecified"))
      (node (ref "R88") (pin "1") (pinfunction "1_1") (pintype "input"))
      (node (ref "U52") (pin "6") (pinfunction "SD1_6") (pintype "unspecified"))
    )
    (net (code "208") (name "SDA_Temp_internal") (class "Default")
      (node (ref "R86") (pin "1") (pinfunction "1_1") (pintype "input"))
      (node (ref "U52") (pin "4") (pinfunction "SD0_4") (pintype "unspecified"))
      (node (ref "U55") (pin "1") (pinfunction "DATA_1") (pintype "unspecified"))
    )
    (net (code "209") (name "SDA_Up") (class "Default")
      (node (ref "U52") (pin "15") (pinfunction "SDA_15") (pintype "unspecified"))
      (node (ref "U53") (pin "15") (pinfunction "SDA_15") (pintype "unspecified"))
    )
    (net (code "210") (name "SDA_uP") (class "Default")
      (node (ref "R69") (pin "1") (pinfunction "1_1") (pintype "input"))
      (node (ref "U50") (pin "15") (pinfunction "SDA_15") (pintype "unspecified"))
      (node (ref "U51") (pin "15") (pinfunction "SDA_15") (pintype "unspecified"))
      (node (ref "U69") (pin "D2") (pinfunction "D2_D2") (pintype "unspecified"))
    )
    (net (code "211") (name "Spare_I2C_reset_L") (class "Default")
      (node (ref "CN9") (pin "5") (pinfunction "5_5") (pintype "unspecified"))
      (node (ref "R58") (pin "2") (pinfunction "2_2") (pintype "input"))
    )
    (net (code "212") (name "Temp_I2C_reset_L") (class "Default")
      (node (ref "CN10") (pin "5") (pinfunction "5_5") (pintype "unspecified"))
      (node (ref "R50") (pin "2") (pinfunction "2_2") (pintype "input"))
    )
    (net (code "213") (name "UP_LED_ON_H") (class "Default")
      (node (ref "R103") (pin "1") (pinfunction "1_1") (pintype "input"))
      (node (ref "R118") (pin "1") (pinfunction "1_1") (pintype "input"))
      (node (ref "U58") (pin "1") (pinfunction "1A_1") (pintype "unspecified"))
      (node (ref "U66") (pin "1") (pinfunction "1A_1") (pintype "unspecified"))
      (node (ref "U69") (pin "D10") (pinfunction "D10_D10") (pintype "unspecified"))
    )
    (net (code "214") (name "VA_measure") (class "Default")
      (node (ref "C70") (pin "2") (pinfunction "2_2") (pintype "unspecified"))
      (node (ref "R22") (pin "1") (pinfunction "1_1") (pintype "input"))
      (node (ref "R25") (pin "2") (pinfunction "2_2") (pintype "input"))
      (node (ref "U68") (pin "10") (pinfunction "AIN1_10") (pintype "unspecified"))
    )
    (net (code "215") (name "VB_measure") (class "Default")
      (node (ref "C68") (pin "2") (pinfunction "2_2") (pintype "unspecified"))
      (node (ref "R31") (pin "1") (pinfunction "1_1") (pintype "input"))
      (node (ref "R32") (pin "2") (pinfunction "2_2") (pintype "input"))
      (node (ref "U68") (pin "6") (pinfunction "AIN3_6") (pintype "unspecified"))
    )
    (net (code "216") (name "VBatt_measure") (class "Default")
      (node (ref "C69") (pin "2") (pinfunction "2_2") (pintype "unspecified"))
      (node (ref "R21") (pin "1") (pinfunction "1_1") (pintype "input"))
      (node (ref "R24") (pin "2") (pinfunction "2_2") (pintype "input"))
      (node (ref "U68") (pin "7") (pinfunction "AIN2_7") (pintype "unspecified"))
    )
    (net (code "217") (name "V_Batt") (class "Default")
      (node (ref "Q1") (pin "2") (pinfunction "S_2") (pintype "unspecified"))
      (node (ref "R19") (pin "2") (pinfunction "2_2") (pintype "input"))
      (node (ref "R36") (pin "2") (pinfunction "2_2") (pintype "unspecified"))
      (node (ref "U39") (pin "5") (pinfunction "D_5") (pintype "unspecified"))
      (node (ref "U43") (pin "6") (pinfunction "DRAIN_6") (pintype "unspecified"))
      (node (ref "U44") (pin "1") (pinfunction "S_1") (pintype "unspecified"))
      (node (ref "U44") (pin "2") (pinfunction "S_2") (pintype "unspecified"))
      (node (ref "U44") (pin "3") (pinfunction "S_3") (pintype "unspecified"))
      (node (ref "U74") (pin "2") (pinfunction "2_2") (pintype "bidirectional"))
    )
    (net (code "218") (name "V_Sense_H") (class "Default")
      (node (ref "Q3") (pin "1") (pinfunction "G_1") (pintype "unspecified"))
      (node (ref "Q4") (pin "1") (pinfunction "G_1") (pintype "unspecified"))
      (node (ref "Q8") (pin "1") (pinfunction "G_1") (pintype "unspecified"))
      (node (ref "R120") (pin "2") (pinfunction "2_2") (pintype "input"))
      (node (ref "U69") (pin "D7") (pinfunction "D7_D7") (pintype "unspecified"))
    )
    (net (code "219") (name "unconnected-(CN11-Pad3)") (class "Default")
      (node (ref "CN11") (pin "3") (pinfunction "3_3") (pintype "unspecified+no_connect"))
    )
    (net (code "220") (name "unconnected-(CN12-Pad3)") (class "Default")
      (node (ref "CN12") (pin "3") (pinfunction "3_3") (pintype "unspecified+no_connect"))
    )
    (net (code "221") (name "unconnected-(CN13-Pad3)") (class "Default")
      (node (ref "CN13") (pin "3") (pinfunction "3_3") (pintype "unspecified+no_connect"))
    )
    (net (code "222") (name "unconnected-(CN14-Pad3)") (class "Default")
      (node (ref "CN14") (pin "3") (pinfunction "3_3") (pintype "unspecified+no_connect"))
    )
    (net (code "223") (name "unconnected-(CN15-Pad3)") (class "Default")
      (node (ref "CN15") (pin "3") (pinfunction "3_3") (pintype "unspecified+no_connect"))
    )
    (net (code "224") (name "unconnected-(CN16-Pad3)") (class "Default")
      (node (ref "CN16") (pin "3") (pinfunction "3_3") (pintype "unspecified+no_connect"))
    )
    (net (code "225") (name "unconnected-(CN17-Pad3)") (class "Default")
      (node (ref "CN17") (pin "3") (pinfunction "3_3") (pintype "unspecified+no_connect"))
    )
    (net (code "226") (name "unconnected-(CN18-Pad3)") (class "Default")
      (node (ref "CN18") (pin "3") (pinfunction "3_3") (pintype "unspecified+no_connect"))
    )
    (net (code "227") (name "unconnected-(H1-Pad3)") (class "Default")
      (node (ref "H1") (pin "3") (pinfunction "3_3") (pintype "unspecified+no_connect"))
    )
    (net (code "228") (name "unconnected-(R63-Pad2)") (class "Default")
      (node (ref "R63") (pin "2") (pinfunction "2_2") (pintype "input+no_connect"))
    )
    (net (code "229") (name "unconnected-(R66-Pad2)") (class "Default")
      (node (ref "R66") (pin "2") (pinfunction "2_2") (pintype "input+no_connect"))
    )
    (net (code "230") (name "unconnected-(U1-DISC-Pad10)") (class "Default")
      (node (ref "U1") (pin "10") (pinfunction "DISC_10") (pintype "unspecified+no_connect"))
    )
    (net (code "231") (name "unconnected-(U1-NC-Pad4)") (class "Default")
      (node (ref "U1") (pin "4") (pinfunction "NC_4") (pintype "unspecified+no_connect"))
    )
    (net (code "232") (name "unconnected-(U2-DISC-Pad10)") (class "Default")
      (node (ref "U2") (pin "10") (pinfunction "DISC_10") (pintype "unspecified+no_connect"))
    )
    (net (code "233") (name "unconnected-(U2-NC-Pad4)") (class "Default")
      (node (ref "U2") (pin "4") (pinfunction "NC_4") (pintype "unspecified+no_connect"))
    )
    (net (code "234") (name "unconnected-(U3-DISC-Pad10)") (class "Default")
      (node (ref "U3") (pin "10") (pinfunction "DISC_10") (pintype "unspecified+no_connect"))
    )
    (net (code "235") (name "unconnected-(U3-NC-Pad4)") (class "Default")
      (node (ref "U3") (pin "4") (pinfunction "NC_4") (pintype "unspecified+no_connect"))
    )
    (net (code "236") (name "unconnected-(U4-DISC-Pad10)") (class "Default")
      (node (ref "U4") (pin "10") (pinfunction "DISC_10") (pintype "unspecified+no_connect"))
    )
    (net (code "237") (name "unconnected-(U4-NC-Pad4)") (class "Default")
      (node (ref "U4") (pin "4") (pinfunction "NC_4") (pintype "unspecified+no_connect"))
    )
    (net (code "238") (name "unconnected-(U14-DISC-Pad10)") (class "Default")
      (node (ref "U14") (pin "10") (pinfunction "DISC_10") (pintype "unspecified+no_connect"))
    )
    (net (code "239") (name "unconnected-(U14-NC-Pad4)") (class "Default")
      (node (ref "U14") (pin "4") (pinfunction "NC_4") (pintype "unspecified+no_connect"))
    )
    (net (code "240") (name "unconnected-(U15-DISC-Pad10)") (class "Default")
      (node (ref "U15") (pin "10") (pinfunction "DISC_10") (pintype "unspecified+no_connect"))
    )
    (net (code "241") (name "unconnected-(U15-NC-Pad4)") (class "Default")
      (node (ref "U15") (pin "4") (pinfunction "NC_4") (pintype "unspecified+no_connect"))
    )
    (net (code "242") (name "unconnected-(U16-DISC-Pad10)") (class "Default")
      (node (ref "U16") (pin "10") (pinfunction "DISC_10") (pintype "unspecified+no_connect"))
    )
    (net (code "243") (name "unconnected-(U16-NC-Pad4)") (class "Default")
      (node (ref "U16") (pin "4") (pinfunction "NC_4") (pintype "unspecified+no_connect"))
    )
    (net (code "244") (name "unconnected-(U17-DISC-Pad10)") (class "Default")
      (node (ref "U17") (pin "10") (pinfunction "DISC_10") (pintype "unspecified+no_connect"))
    )
    (net (code "245") (name "unconnected-(U17-NC-Pad4)") (class "Default")
      (node (ref "U17") (pin "4") (pinfunction "NC_4") (pintype "unspecified+no_connect"))
    )
    (net (code "246") (name "unconnected-(U18-DISC-Pad10)") (class "Default")
      (node (ref "U18") (pin "10") (pinfunction "DISC_10") (pintype "unspecified+no_connect"))
    )
    (net (code "247") (name "unconnected-(U18-NC-Pad4)") (class "Default")
      (node (ref "U18") (pin "4") (pinfunction "NC_4") (pintype "unspecified+no_connect"))
    )
    (net (code "248") (name "unconnected-(U19-DISC-Pad10)") (class "Default")
      (node (ref "U19") (pin "10") (pinfunction "DISC_10") (pintype "unspecified+no_connect"))
    )
    (net (code "249") (name "unconnected-(U19-NC-Pad4)") (class "Default")
      (node (ref "U19") (pin "4") (pinfunction "NC_4") (pintype "unspecified+no_connect"))
    )
    (net (code "250") (name "unconnected-(U20-DISC-Pad10)") (class "Default")
      (node (ref "U20") (pin "10") (pinfunction "DISC_10") (pintype "unspecified+no_connect"))
    )
    (net (code "251") (name "unconnected-(U20-NC-Pad4)") (class "Default")
      (node (ref "U20") (pin "4") (pinfunction "NC_4") (pintype "unspecified+no_connect"))
    )
    (net (code "252") (name "unconnected-(U21-DISC-Pad10)") (class "Default")
      (node (ref "U21") (pin "10") (pinfunction "DISC_10") (pintype "unspecified+no_connect"))
    )
    (net (code "253") (name "unconnected-(U21-NC-Pad4)") (class "Default")
      (node (ref "U21") (pin "4") (pinfunction "NC_4") (pintype "unspecified+no_connect"))
    )
    (net (code "254") (name "unconnected-(U22-DISC-Pad10)") (class "Default")
      (node (ref "U22") (pin "10") (pinfunction "DISC_10") (pintype "unspecified+no_connect"))
    )
    (net (code "255") (name "unconnected-(U22-NC-Pad4)") (class "Default")
      (node (ref "U22") (pin "4") (pinfunction "NC_4") (pintype "unspecified+no_connect"))
    )
    (net (code "256") (name "unconnected-(U23-DISC-Pad10)") (class "Default")
      (node (ref "U23") (pin "10") (pinfunction "DISC_10") (pintype "unspecified+no_connect"))
    )
    (net (code "257") (name "unconnected-(U23-NC-Pad4)") (class "Default")
      (node (ref "U23") (pin "4") (pinfunction "NC_4") (pintype "unspecified+no_connect"))
    )
    (net (code "258") (name "unconnected-(U24-DISC-Pad10)") (class "Default")
      (node (ref "U24") (pin "10") (pinfunction "DISC_10") (pintype "unspecified+no_connect"))
    )
    (net (code "259") (name "unconnected-(U24-NC-Pad4)") (class "Default")
      (node (ref "U24") (pin "4") (pinfunction "NC_4") (pintype "unspecified+no_connect"))
    )
    (net (code "260") (name "unconnected-(U25-DISC-Pad10)") (class "Default")
      (node (ref "U25") (pin "10") (pinfunction "DISC_10") (pintype "unspecified+no_connect"))
    )
    (net (code "261") (name "unconnected-(U25-NC-Pad4)") (class "Default")
      (node (ref "U25") (pin "4") (pinfunction "NC_4") (pintype "unspecified+no_connect"))
    )
    (net (code "262") (name "unconnected-(U26-PG-Pad8)") (class "Default")
      (node (ref "U26") (pin "8") (pinfunction "PG_8") (pintype "unspecified+no_connect"))
    )
    (net (code "263") (name "unconnected-(U27-Trim-Pad6)") (class "Default")
      (node (ref "U27") (pin "6") (pinfunction "Trim_6") (pintype "input+no_connect"))
    )
    (net (code "264") (name "unconnected-(U32-NC-Pad1)") (class "Default")
      (node (ref "U32") (pin "1") (pinfunction "NC_1") (pintype "unspecified+no_connect"))
    )
    (net (code "265") (name "unconnected-(U32-NC-Pad5)") (class "Default")
      (node (ref "U32") (pin "5") (pinfunction "NC_5") (pintype "unspecified+no_connect"))
    )
    (net (code "266") (name "unconnected-(U37-NC-Pad1)") (class "Default")
      (node (ref "U37") (pin "1") (pinfunction "NC_1") (pintype "unspecified+no_connect"))
    )
    (net (code "267") (name "unconnected-(U37-NC-Pad5)") (class "Default")
      (node (ref "U37") (pin "5") (pinfunction "NC_5") (pintype "unspecified+no_connect"))
    )
    (net (code "268") (name "unconnected-(U43-NC-Pad1)") (class "Default")
      (node (ref "U43") (pin "1") (pinfunction "NC_1") (pintype "unspecified+no_connect"))
    )
    (net (code "269") (name "unconnected-(U43-NC-Pad5)") (class "Default")
      (node (ref "U43") (pin "5") (pinfunction "NC_5") (pintype "unspecified+no_connect"))
    )
    (net (code "270") (name "unconnected-(U53-SC3-Pad12)") (class "Default")
      (node (ref "U53") (pin "12") (pinfunction "SC3_12") (pintype "unspecified+no_connect"))
    )
    (net (code "271") (name "unconnected-(U53-SD3-Pad11)") (class "Default")
      (node (ref "U53") (pin "11") (pinfunction "SD3_11") (pintype "unspecified+no_connect"))
    )
    (net (code "272") (name "unconnected-(U54-DAV-Pad11)") (class "Default")
      (node (ref "U54") (pin "11") (pinfunction "DAV_11") (pintype "unspecified+no_connect"))
    )
    (net (code "273") (name "unconnected-(U54-DNC-Pad5)") (class "Default")
      (node (ref "U54") (pin "5") (pinfunction "DNC_5") (pintype "unspecified+no_connect"))
    )
    (net (code "274") (name "unconnected-(U54-DNC-Pad6)") (class "Default")
      (node (ref "U54") (pin "6") (pinfunction "DNC_6") (pintype "unspecified+no_connect"))
    )
    (net (code "275") (name "unconnected-(U54-DNC-Pad7)") (class "Default")
      (node (ref "U54") (pin "7") (pinfunction "DNC_7") (pintype "unspecified+no_connect"))
    )
    (net (code "276") (name "unconnected-(U54-SCK-Pad4)") (class "Default")
      (node (ref "U54") (pin "4") (pinfunction "SCK_4") (pintype "unspecified+no_connect"))
    )
    (net (code "277") (name "unconnected-(U55-INT-Pad3)") (class "Default")
      (node (ref "U55") (pin "3") (pinfunction "INT_3") (pintype "unspecified+no_connect"))
    )
    (net (code "278") (name "unconnected-(U56-DAV-Pad11)") (class "Default")
      (node (ref "U56") (pin "11") (pinfunction "DAV_11") (pintype "unspecified+no_connect"))
    )
    (net (code "279") (name "unconnected-(U56-DNC-Pad5)") (class "Default")
      (node (ref "U56") (pin "5") (pinfunction "DNC_5") (pintype "unspecified+no_connect"))
    )
    (net (code "280") (name "unconnected-(U56-DNC-Pad6)") (class "Default")
      (node (ref "U56") (pin "6") (pinfunction "DNC_6") (pintype "unspecified+no_connect"))
    )
    (net (code "281") (name "unconnected-(U56-DNC-Pad7)") (class "Default")
      (node (ref "U56") (pin "7") (pinfunction "DNC_7") (pintype "unspecified+no_connect"))
    )
    (net (code "282") (name "unconnected-(U56-SCK-Pad4)") (class "Default")
      (node (ref "U56") (pin "4") (pinfunction "SCK_4") (pintype "unspecified+no_connect"))
    )
    (net (code "283") (name "unconnected-(U57-DAV-Pad11)") (class "Default")
      (node (ref "U57") (pin "11") (pinfunction "DAV_11") (pintype "unspecified+no_connect"))
    )
    (net (code "284") (name "unconnected-(U57-DNC-Pad5)") (class "Default")
      (node (ref "U57") (pin "5") (pinfunction "DNC_5") (pintype "unspecified+no_connect"))
    )
    (net (code "285") (name "unconnected-(U57-DNC-Pad6)") (class "Default")
      (node (ref "U57") (pin "6") (pinfunction "DNC_6") (pintype "unspecified+no_connect"))
    )
    (net (code "286") (name "unconnected-(U57-DNC-Pad7)") (class "Default")
      (node (ref "U57") (pin "7") (pinfunction "DNC_7") (pintype "unspecified+no_connect"))
    )
    (net (code "287") (name "unconnected-(U57-SCK-Pad4)") (class "Default")
      (node (ref "U57") (pin "4") (pinfunction "SCK_4") (pintype "unspecified+no_connect"))
    )
    (net (code "288") (name "unconnected-(U58-2Y-Pad4)") (class "Default")
      (node (ref "U58") (pin "4") (pinfunction "2Y_4") (pintype "unspecified+no_connect"))
    )
    (net (code "289") (name "unconnected-(U66-2Y-Pad4)") (class "Default")
      (node (ref "U66") (pin "4") (pinfunction "2Y_4") (pintype "unspecified+no_connect"))
    )
    (net (code "290") (name "unconnected-(U68-REFN-Pad8)") (class "Default")
      (node (ref "U68") (pin "8") (pinfunction "REFN_8") (pintype "unspecified+no_connect"))
    )
    (net (code "291") (name "unconnected-(U68-REFP-Pad9)") (class "Default")
      (node (ref "U68") (pin "9") (pinfunction "REFP_9") (pintype "unspecified+no_connect"))
    )
    (net (code "292") (name "unconnected-(U69-PadRX1)") (class "Default")
      (node (ref "U69") (pin "RX1") (pinfunction "RX1_RX1") (pintype "unspecified+no_connect"))
    )
    (net (code "293") (name "unconnected-(U69-PadTX0)") (class "Default")
      (node (ref "U69") (pin "TX0") (pinfunction "TX0_TX0") (pintype "unspecified+no_connect"))
    )
    (net (code "294") (name "unconnected-(U69-PadVCC)") (class "Default")
      (node (ref "U69") (pin "VCC") (pinfunction "VCC_VCC") (pintype "unspecified+no_connect"))
    )
    (net (code "295") (name "unconnected-(U70-PF-Pad1)") (class "Default")
      (node (ref "U70") (pin "1") (pinfunction "PF_1") (pintype "unspecified+no_connect"))
    )
    (net (code "296") (name "up_Reset_L") (class "Default")
      (node (ref "U46") (pin "1") (pinfunction "RESETB_1") (pintype "unspecified"))
      (node (ref "U69") (pin "RST") (pinfunction "RST_RST") (pintype "unspecified"))
    )
  )
)
